# UCirKitBreadboardTop-0824.net
KiCad netlist of a schematic drawn in EAGLE
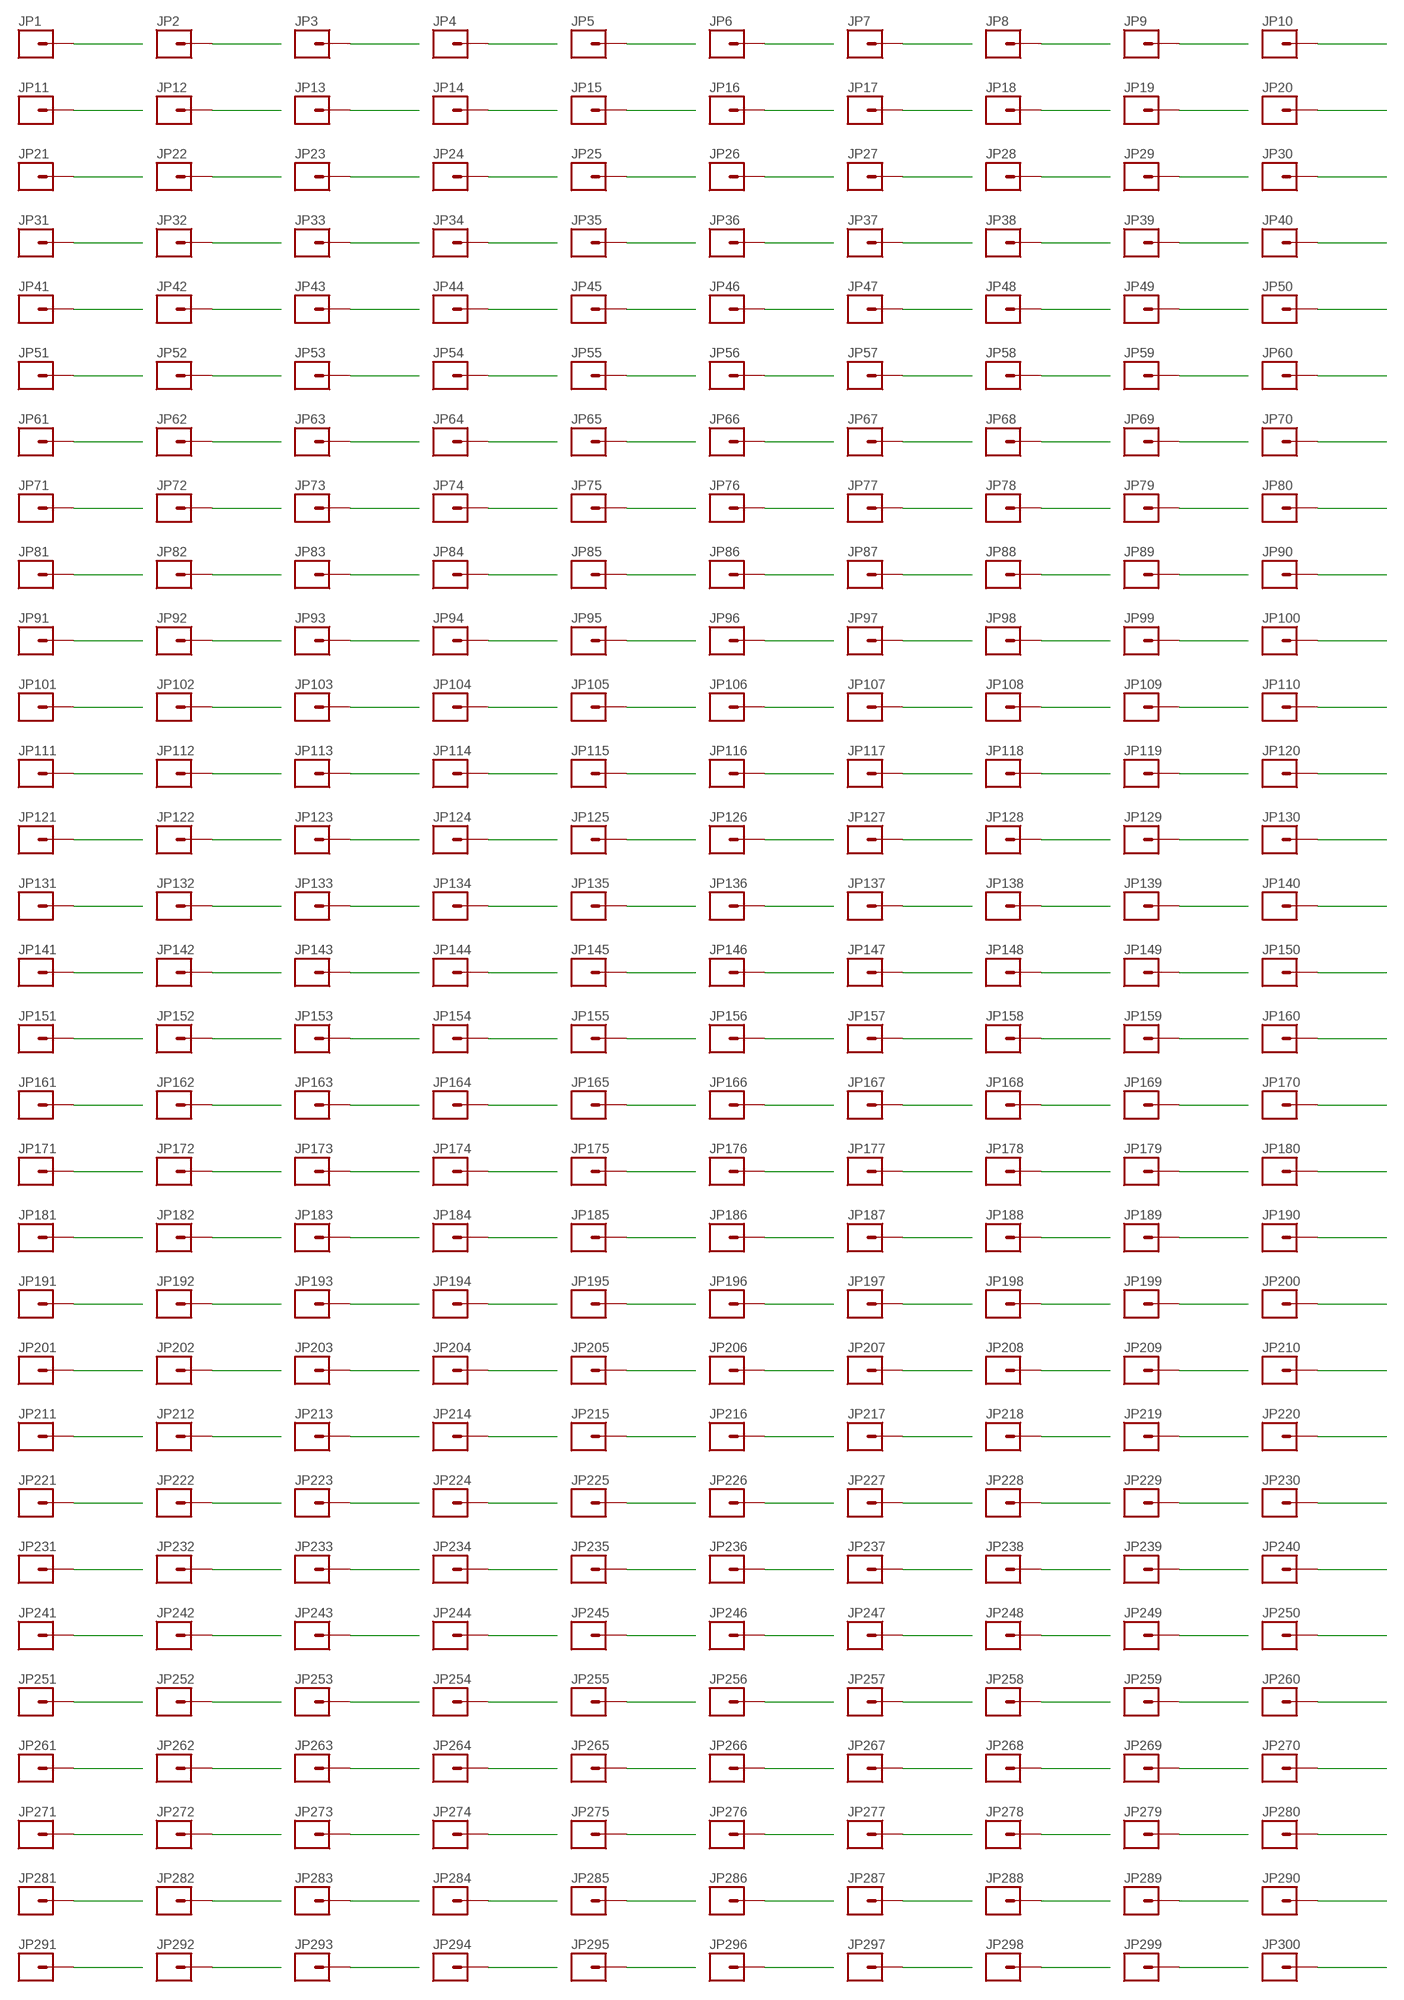
[diagram p0: schematic, sheet 1, part 1 of 2]
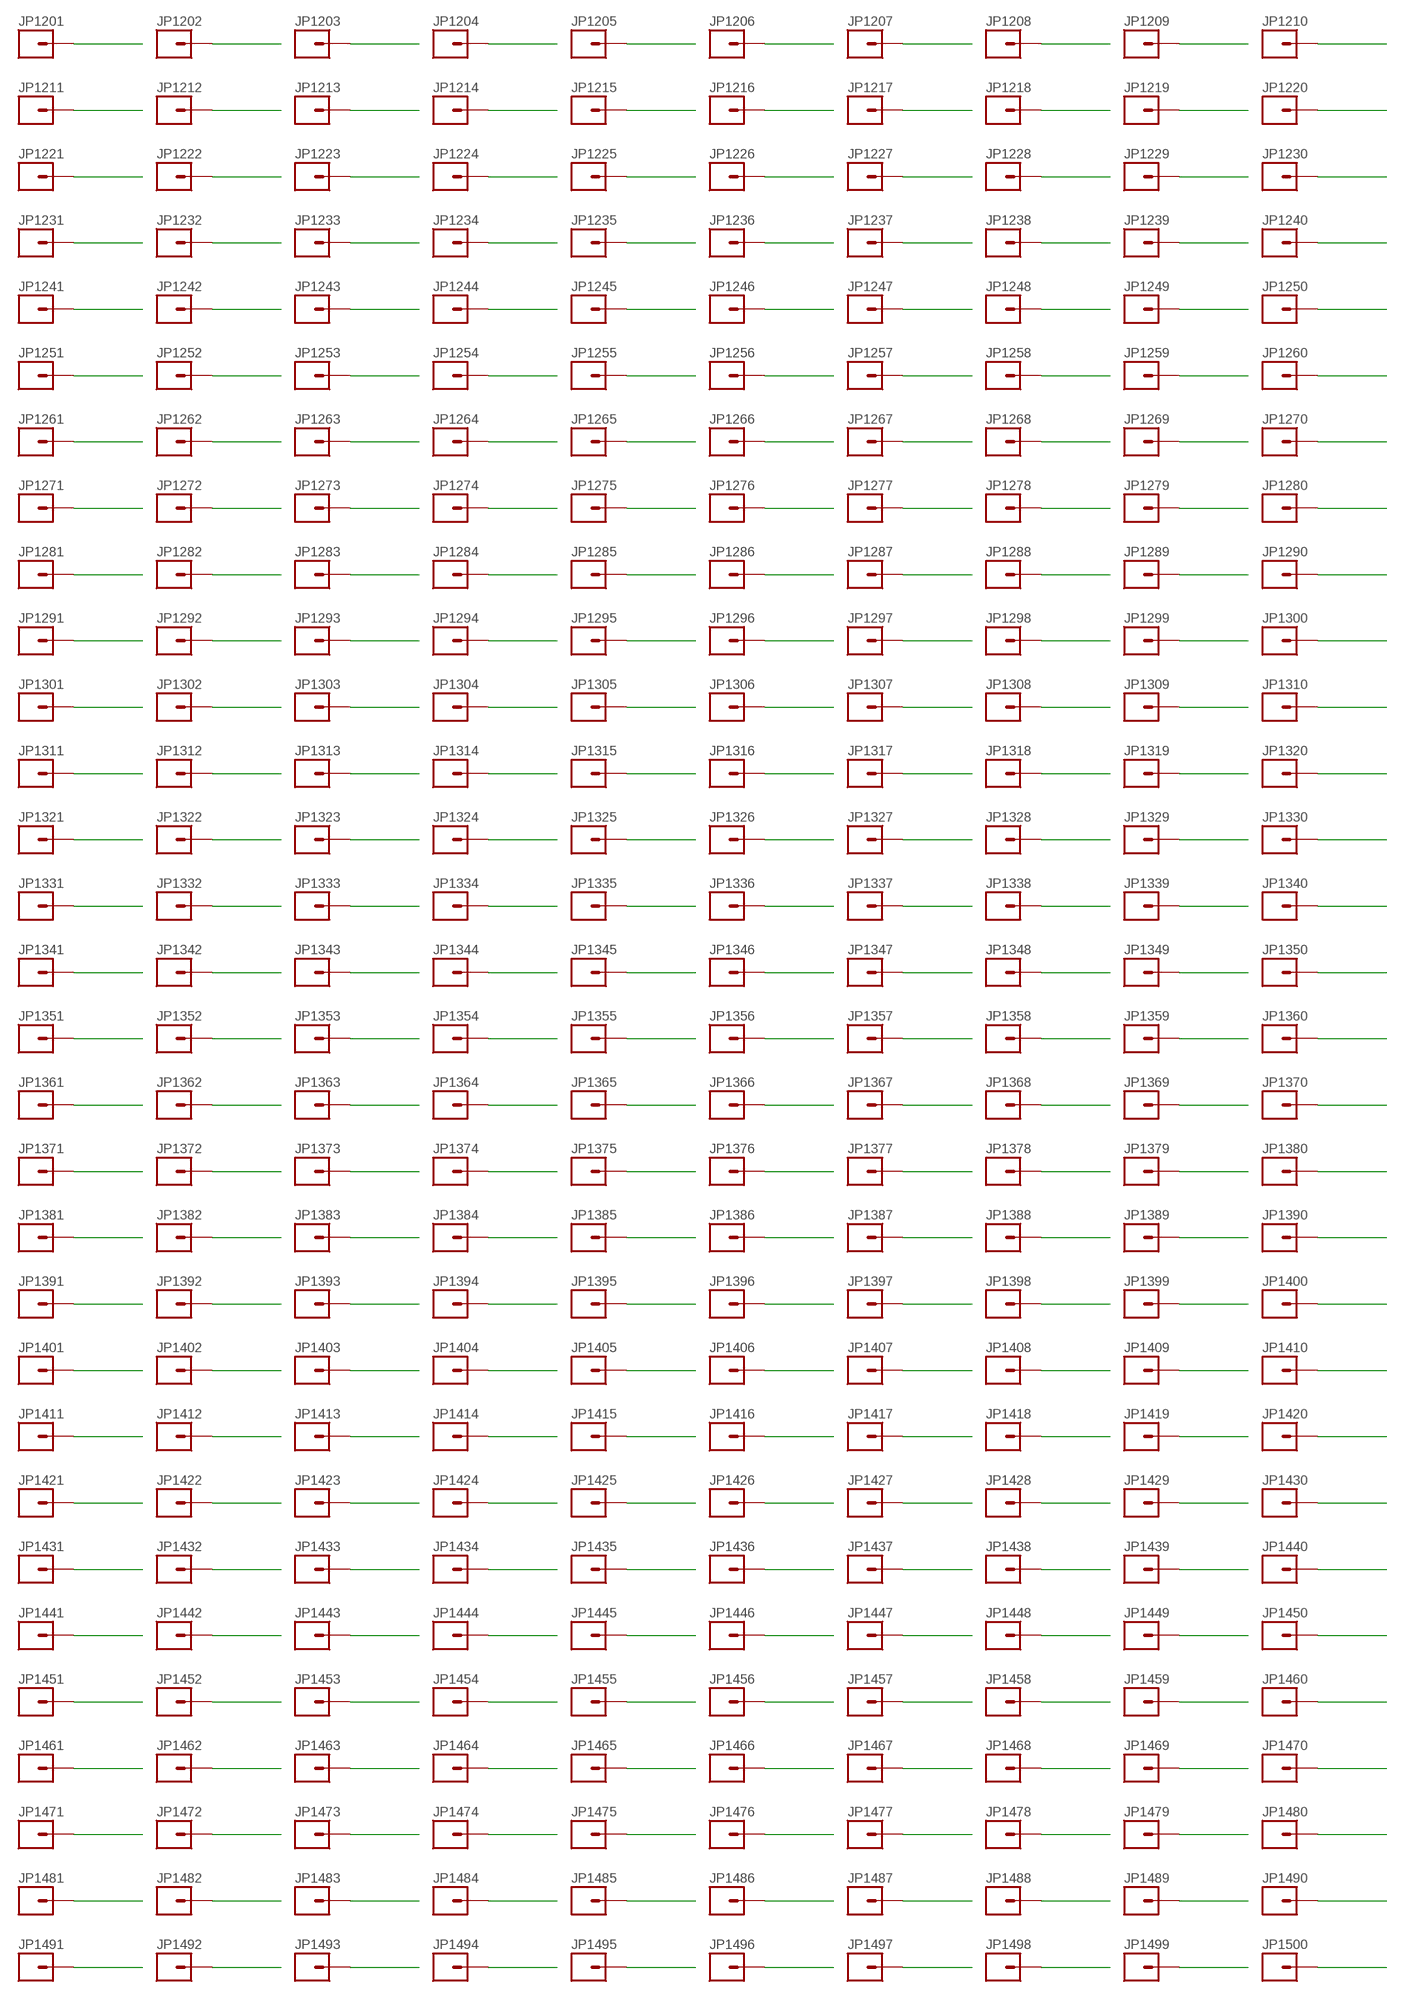
[diagram p1: schematic, sheet 1, part 2 of 2]

(export (version "E")
  (design (tool "Eeschema 10.0.6"))
  (components
    (comp (ref "JP1")
      (value "M01PTH_WITHOUT_TEXT")
      (footprint "eagle-import:1X01_WITHOUT_TEXT")
      (libsource (lib "eagle-import") (part "M01PTH_WITHOUT_TEXT"))
    )
    (comp (ref "JP2")
      (value "M01PTH_WITHOUT_TEXT")
      (footprint "eagle-import:1X01_WITHOUT_TEXT")
      (libsource (lib "eagle-import") (part "M01PTH_WITHOUT_TEXT"))
    )
    (comp (ref "JP3")
      (value "M01PTH_WITHOUT_TEXT")
      (footprint "eagle-import:1X01_WITHOUT_TEXT")
      (libsource (lib "eagle-import") (part "M01PTH_WITHOUT_TEXT"))
    )
    (comp (ref "JP4")
      (value "M01PTH_WITHOUT_TEXT")
      (footprint "eagle-import:1X01_WITHOUT_TEXT")
      (libsource (lib "eagle-import") (part "M01PTH_WITHOUT_TEXT"))
    )
    (comp (ref "JP5")
      (value "M01PTH_WITHOUT_TEXT")
      (footprint "eagle-import:1X01_WITHOUT_TEXT")
      (libsource (lib "eagle-import") (part "M01PTH_WITHOUT_TEXT"))
    )
    (comp (ref "JP6")
      (value "M01PTH_WITHOUT_TEXT")
      (footprint "eagle-import:1X01_WITHOUT_TEXT")
      (libsource (lib "eagle-import") (part "M01PTH_WITHOUT_TEXT"))
    )
    (comp (ref "JP7")
      (value "M01PTH_WITHOUT_TEXT")
      (footprint "eagle-import:1X01_WITHOUT_TEXT")
      (libsource (lib "eagle-import") (part "M01PTH_WITHOUT_TEXT"))
    )
    (comp (ref "JP8")
      (value "M01PTH_WITHOUT_TEXT")
      (footprint "eagle-import:1X01_WITHOUT_TEXT")
      (libsource (lib "eagle-import") (part "M01PTH_WITHOUT_TEXT"))
    )
    (comp (ref "JP9")
      (value "M01PTH_WITHOUT_TEXT")
      (footprint "eagle-import:1X01_WITHOUT_TEXT")
      (libsource (lib "eagle-import") (part "M01PTH_WITHOUT_TEXT"))
    )
    (comp (ref "JP10")
      (value "M01PTH_WITHOUT_TEXT")
      (footprint "eagle-import:1X01_WITHOUT_TEXT")
      (libsource (lib "eagle-import") (part "M01PTH_WITHOUT_TEXT"))
    )
    (comp (ref "JP11")
      (value "M01PTH_WITHOUT_TEXT")
      (footprint "eagle-import:1X01_WITHOUT_TEXT")
      (libsource (lib "eagle-import") (part "M01PTH_WITHOUT_TEXT"))
    )
    (comp (ref "JP12")
      (value "M01PTH_WITHOUT_TEXT")
      (footprint "eagle-import:1X01_WITHOUT_TEXT")
      (libsource (lib "eagle-import") (part "M01PTH_WITHOUT_TEXT"))
    )
    (comp (ref "JP13")
      (value "M01PTH_WITHOUT_TEXT")
      (footprint "eagle-import:1X01_WITHOUT_TEXT")
      (libsource (lib "eagle-import") (part "M01PTH_WITHOUT_TEXT"))
    )
    (comp (ref "JP14")
      (value "M01PTH_WITHOUT_TEXT")
      (footprint "eagle-import:1X01_WITHOUT_TEXT")
      (libsource (lib "eagle-import") (part "M01PTH_WITHOUT_TEXT"))
    )
    (comp (ref "JP15")
      (value "M01PTH_WITHOUT_TEXT")
      (footprint "eagle-import:1X01_WITHOUT_TEXT")
      (libsource (lib "eagle-import") (part "M01PTH_WITHOUT_TEXT"))
    )
    (comp (ref "JP16")
      (value "M01PTH_WITHOUT_TEXT")
      (footprint "eagle-import:1X01_WITHOUT_TEXT")
      (libsource (lib "eagle-import") (part "M01PTH_WITHOUT_TEXT"))
    )
    (comp (ref "JP17")
      (value "M01PTH_WITHOUT_TEXT")
      (footprint "eagle-import:1X01_WITHOUT_TEXT")
      (libsource (lib "eagle-import") (part "M01PTH_WITHOUT_TEXT"))
    )
    (comp (ref "JP18")
      (value "M01PTH_WITHOUT_TEXT")
      (footprint "eagle-import:1X01_WITHOUT_TEXT")
      (libsource (lib "eagle-import") (part "M01PTH_WITHOUT_TEXT"))
    )
    (comp (ref "JP19")
      (value "M01PTH_WITHOUT_TEXT")
      (footprint "eagle-import:1X01_WITHOUT_TEXT")
      (libsource (lib "eagle-import") (part "M01PTH_WITHOUT_TEXT"))
    )
    (comp (ref "JP20")
      (value "M01PTH_WITHOUT_TEXT")
      (footprint "eagle-import:1X01_WITHOUT_TEXT")
      (libsource (lib "eagle-import") (part "M01PTH_WITHOUT_TEXT"))
    )
    (comp (ref "JP21")
      (value "M01PTH_WITHOUT_TEXT")
      (footprint "eagle-import:1X01_WITHOUT_TEXT")
      (libsource (lib "eagle-import") (part "M01PTH_WITHOUT_TEXT"))
    )
    (comp (ref "JP22")
      (value "M01PTH_WITHOUT_TEXT")
      (footprint "eagle-import:1X01_WITHOUT_TEXT")
      (libsource (lib "eagle-import") (part "M01PTH_WITHOUT_TEXT"))
    )
    (comp (ref "JP23")
      (value "M01PTH_WITHOUT_TEXT")
      (footprint "eagle-import:1X01_WITHOUT_TEXT")
      (libsource (lib "eagle-import") (part "M01PTH_WITHOUT_TEXT"))
    )
    (comp (ref "JP24")
      (value "M01PTH_WITHOUT_TEXT")
      (footprint "eagle-import:1X01_WITHOUT_TEXT")
      (libsource (lib "eagle-import") (part "M01PTH_WITHOUT_TEXT"))
    )
    (comp (ref "JP25")
      (value "M01PTH_WITHOUT_TEXT")
      (footprint "eagle-import:1X01_WITHOUT_TEXT")
      (libsource (lib "eagle-import") (part "M01PTH_WITHOUT_TEXT"))
    )
    (comp (ref "JP26")
      (value "M01PTH_WITHOUT_TEXT")
      (footprint "eagle-import:1X01_WITHOUT_TEXT")
      (libsource (lib "eagle-import") (part "M01PTH_WITHOUT_TEXT"))
    )
    (comp (ref "JP27")
      (value "M01PTH_WITHOUT_TEXT")
      (footprint "eagle-import:1X01_WITHOUT_TEXT")
      (libsource (lib "eagle-import") (part "M01PTH_WITHOUT_TEXT"))
    )
    (comp (ref "JP28")
      (value "M01PTH_WITHOUT_TEXT")
      (footprint "eagle-import:1X01_WITHOUT_TEXT")
      (libsource (lib "eagle-import") (part "M01PTH_WITHOUT_TEXT"))
    )
    (comp (ref "JP29")
      (value "M01PTH_WITHOUT_TEXT")
      (footprint "eagle-import:1X01_WITHOUT_TEXT")
      (libsource (lib "eagle-import") (part "M01PTH_WITHOUT_TEXT"))
    )
    (comp (ref "JP30")
      (value "M01PTH_WITHOUT_TEXT")
      (footprint "eagle-import:1X01_WITHOUT_TEXT")
      (libsource (lib "eagle-import") (part "M01PTH_WITHOUT_TEXT"))
    )
    (comp (ref "JP31")
      (value "M01PTH_WITHOUT_TEXT")
      (footprint "eagle-import:1X01_WITHOUT_TEXT")
      (libsource (lib "eagle-import") (part "M01PTH_WITHOUT_TEXT"))
    )
    (comp (ref "JP32")
      (value "M01PTH_WITHOUT_TEXT")
      (footprint "eagle-import:1X01_WITHOUT_TEXT")
      (libsource (lib "eagle-import") (part "M01PTH_WITHOUT_TEXT"))
    )
    (comp (ref "JP33")
      (value "M01PTH_WITHOUT_TEXT")
      (footprint "eagle-import:1X01_WITHOUT_TEXT")
      (libsource (lib "eagle-import") (part "M01PTH_WITHOUT_TEXT"))
    )
    (comp (ref "JP34")
      (value "M01PTH_WITHOUT_TEXT")
      (footprint "eagle-import:1X01_WITHOUT_TEXT")
      (libsource (lib "eagle-import") (part "M01PTH_WITHOUT_TEXT"))
    )
    (comp (ref "JP35")
      (value "M01PTH_WITHOUT_TEXT")
      (footprint "eagle-import:1X01_WITHOUT_TEXT")
      (libsource (lib "eagle-import") (part "M01PTH_WITHOUT_TEXT"))
    )
    (comp (ref "JP36")
      (value "M01PTH_WITHOUT_TEXT")
      (footprint "eagle-import:1X01_WITHOUT_TEXT")
      (libsource (lib "eagle-import") (part "M01PTH_WITHOUT_TEXT"))
    )
    (comp (ref "JP37")
      (value "M01PTH_WITHOUT_TEXT")
      (footprint "eagle-import:1X01_WITHOUT_TEXT")
      (libsource (lib "eagle-import") (part "M01PTH_WITHOUT_TEXT"))
    )
    (comp (ref "JP38")
      (value "M01PTH_WITHOUT_TEXT")
      (footprint "eagle-import:1X01_WITHOUT_TEXT")
      (libsource (lib "eagle-import") (part "M01PTH_WITHOUT_TEXT"))
    )
    (comp (ref "JP39")
      (value "M01PTH_WITHOUT_TEXT")
      (footprint "eagle-import:1X01_WITHOUT_TEXT")
      (libsource (lib "eagle-import") (part "M01PTH_WITHOUT_TEXT"))
    )
    (comp (ref "JP40")
      (value "M01PTH_WITHOUT_TEXT")
      (footprint "eagle-import:1X01_WITHOUT_TEXT")
      (libsource (lib "eagle-import") (part "M01PTH_WITHOUT_TEXT"))
    )
    (comp (ref "JP41")
      (value "M01PTH_WITHOUT_TEXT")
      (footprint "eagle-import:1X01_WITHOUT_TEXT")
      (libsource (lib "eagle-import") (part "M01PTH_WITHOUT_TEXT"))
    )
    (comp (ref "JP42")
      (value "M01PTH_WITHOUT_TEXT")
      (footprint "eagle-import:1X01_WITHOUT_TEXT")
      (libsource (lib "eagle-import") (part "M01PTH_WITHOUT_TEXT"))
    )
    (comp (ref "JP43")
      (value "M01PTH_WITHOUT_TEXT")
      (footprint "eagle-import:1X01_WITHOUT_TEXT")
      (libsource (lib "eagle-import") (part "M01PTH_WITHOUT_TEXT"))
    )
    (comp (ref "JP44")
      (value "M01PTH_WITHOUT_TEXT")
      (footprint "eagle-import:1X01_WITHOUT_TEXT")
      (libsource (lib "eagle-import") (part "M01PTH_WITHOUT_TEXT"))
    )
    (comp (ref "JP45")
      (value "M01PTH_WITHOUT_TEXT")
      (footprint "eagle-import:1X01_WITHOUT_TEXT")
      (libsource (lib "eagle-import") (part "M01PTH_WITHOUT_TEXT"))
    )
    (comp (ref "JP46")
      (value "M01PTH_WITHOUT_TEXT")
      (footprint "eagle-import:1X01_WITHOUT_TEXT")
      (libsource (lib "eagle-import") (part "M01PTH_WITHOUT_TEXT"))
    )
    (comp (ref "JP47")
      (value "M01PTH_WITHOUT_TEXT")
      (footprint "eagle-import:1X01_WITHOUT_TEXT")
      (libsource (lib "eagle-import") (part "M01PTH_WITHOUT_TEXT"))
    )
    (comp (ref "JP48")
      (value "M01PTH_WITHOUT_TEXT")
      (footprint "eagle-import:1X01_WITHOUT_TEXT")
      (libsource (lib "eagle-import") (part "M01PTH_WITHOUT_TEXT"))
    )
    (comp (ref "JP49")
      (value "M01PTH_WITHOUT_TEXT")
      (footprint "eagle-import:1X01_WITHOUT_TEXT")
      (libsource (lib "eagle-import") (part "M01PTH_WITHOUT_TEXT"))
    )
    (comp (ref "JP50")
      (value "M01PTH_WITHOUT_TEXT")
      (footprint "eagle-import:1X01_WITHOUT_TEXT")
      (libsource (lib "eagle-import") (part "M01PTH_WITHOUT_TEXT"))
    )
    (comp (ref "JP51")
      (value "M01PTH_WITHOUT_TEXT")
      (footprint "eagle-import:1X01_WITHOUT_TEXT")
      (libsource (lib "eagle-import") (part "M01PTH_WITHOUT_TEXT"))
    )
    (comp (ref "JP52")
      (value "M01PTH_WITHOUT_TEXT")
      (footprint "eagle-import:1X01_WITHOUT_TEXT")
      (libsource (lib "eagle-import") (part "M01PTH_WITHOUT_TEXT"))
    )
    (comp (ref "JP53")
      (value "M01PTH_WITHOUT_TEXT")
      (footprint "eagle-import:1X01_WITHOUT_TEXT")
      (libsource (lib "eagle-import") (part "M01PTH_WITHOUT_TEXT"))
    )
    (comp (ref "JP54")
      (value "M01PTH_WITHOUT_TEXT")
      (footprint "eagle-import:1X01_WITHOUT_TEXT")
      (libsource (lib "eagle-import") (part "M01PTH_WITHOUT_TEXT"))
    )
    (comp (ref "JP55")
      (value "M01PTH_WITHOUT_TEXT")
      (footprint "eagle-import:1X01_WITHOUT_TEXT")
      (libsource (lib "eagle-import") (part "M01PTH_WITHOUT_TEXT"))
    )
    (comp (ref "JP56")
      (value "M01PTH_WITHOUT_TEXT")
      (footprint "eagle-import:1X01_WITHOUT_TEXT")
      (libsource (lib "eagle-import") (part "M01PTH_WITHOUT_TEXT"))
    )
    (comp (ref "JP57")
      (value "M01PTH_WITHOUT_TEXT")
      (footprint "eagle-import:1X01_WITHOUT_TEXT")
      (libsource (lib "eagle-import") (part "M01PTH_WITHOUT_TEXT"))
    )
    (comp (ref "JP58")
      (value "M01PTH_WITHOUT_TEXT")
      (footprint "eagle-import:1X01_WITHOUT_TEXT")
      (libsource (lib "eagle-import") (part "M01PTH_WITHOUT_TEXT"))
    )
    (comp (ref "JP59")
      (value "M01PTH_WITHOUT_TEXT")
      (footprint "eagle-import:1X01_WITHOUT_TEXT")
      (libsource (lib "eagle-import") (part "M01PTH_WITHOUT_TEXT"))
    )
    (comp (ref "JP60")
      (value "M01PTH_WITHOUT_TEXT")
      (footprint "eagle-import:1X01_WITHOUT_TEXT")
      (libsource (lib "eagle-import") (part "M01PTH_WITHOUT_TEXT"))
    )
    (comp (ref "JP61")
      (value "M01PTH_WITHOUT_TEXT")
      (footprint "eagle-import:1X01_WITHOUT_TEXT")
      (libsource (lib "eagle-import") (part "M01PTH_WITHOUT_TEXT"))
    )
    (comp (ref "JP62")
      (value "M01PTH_WITHOUT_TEXT")
      (footprint "eagle-import:1X01_WITHOUT_TEXT")
      (libsource (lib "eagle-import") (part "M01PTH_WITHOUT_TEXT"))
    )
    (comp (ref "JP63")
      (value "M01PTH_WITHOUT_TEXT")
      (footprint "eagle-import:1X01_WITHOUT_TEXT")
      (libsource (lib "eagle-import") (part "M01PTH_WITHOUT_TEXT"))
    )
    (comp (ref "JP64")
      (value "M01PTH_WITHOUT_TEXT")
      (footprint "eagle-import:1X01_WITHOUT_TEXT")
      (libsource (lib "eagle-import") (part "M01PTH_WITHOUT_TEXT"))
    )
    (comp (ref "JP65")
      (value "M01PTH_WITHOUT_TEXT")
      (footprint "eagle-import:1X01_WITHOUT_TEXT")
      (libsource (lib "eagle-import") (part "M01PTH_WITHOUT_TEXT"))
    )
    (comp (ref "JP66")
      (value "M01PTH_WITHOUT_TEXT")
      (footprint "eagle-import:1X01_WITHOUT_TEXT")
      (libsource (lib "eagle-import") (part "M01PTH_WITHOUT_TEXT"))
    )
    (comp (ref "JP67")
      (value "M01PTH_WITHOUT_TEXT")
      (footprint "eagle-import:1X01_WITHOUT_TEXT")
      (libsource (lib "eagle-import") (part "M01PTH_WITHOUT_TEXT"))
    )
    (comp (ref "JP68")
      (value "M01PTH_WITHOUT_TEXT")
      (footprint "eagle-import:1X01_WITHOUT_TEXT")
      (libsource (lib "eagle-import") (part "M01PTH_WITHOUT_TEXT"))
    )
    (comp (ref "JP69")
      (value "M01PTH_WITHOUT_TEXT")
      (footprint "eagle-import:1X01_WITHOUT_TEXT")
      (libsource (lib "eagle-import") (part "M01PTH_WITHOUT_TEXT"))
    )
    (comp (ref "JP70")
      (value "M01PTH_WITHOUT_TEXT")
      (footprint "eagle-import:1X01_WITHOUT_TEXT")
      (libsource (lib "eagle-import") (part "M01PTH_WITHOUT_TEXT"))
    )
    (comp (ref "JP71")
      (value "M01PTH_WITHOUT_TEXT")
      (footprint "eagle-import:1X01_WITHOUT_TEXT")
      (libsource (lib "eagle-import") (part "M01PTH_WITHOUT_TEXT"))
    )
    (comp (ref "JP72")
      (value "M01PTH_WITHOUT_TEXT")
      (footprint "eagle-import:1X01_WITHOUT_TEXT")
      (libsource (lib "eagle-import") (part "M01PTH_WITHOUT_TEXT"))
    )
    (comp (ref "JP73")
      (value "M01PTH_WITHOUT_TEXT")
      (footprint "eagle-import:1X01_WITHOUT_TEXT")
      (libsource (lib "eagle-import") (part "M01PTH_WITHOUT_TEXT"))
    )
    (comp (ref "JP74")
      (value "M01PTH_WITHOUT_TEXT")
      (footprint "eagle-import:1X01_WITHOUT_TEXT")
      (libsource (lib "eagle-import") (part "M01PTH_WITHOUT_TEXT"))
    )
    (comp (ref "JP75")
      (value "M01PTH_WITHOUT_TEXT")
      (footprint "eagle-import:1X01_WITHOUT_TEXT")
      (libsource (lib "eagle-import") (part "M01PTH_WITHOUT_TEXT"))
    )
    (comp (ref "JP76")
      (value "M01PTH_WITHOUT_TEXT")
      (footprint "eagle-import:1X01_WITHOUT_TEXT")
      (libsource (lib "eagle-import") (part "M01PTH_WITHOUT_TEXT"))
    )
    (comp (ref "JP77")
      (value "M01PTH_WITHOUT_TEXT")
      (footprint "eagle-import:1X01_WITHOUT_TEXT")
      (libsource (lib "eagle-import") (part "M01PTH_WITHOUT_TEXT"))
    )
    (comp (ref "JP78")
      (value "M01PTH_WITHOUT_TEXT")
      (footprint "eagle-import:1X01_WITHOUT_TEXT")
      (libsource (lib "eagle-import") (part "M01PTH_WITHOUT_TEXT"))
    )
    (comp (ref "JP79")
      (value "M01PTH_WITHOUT_TEXT")
      (footprint "eagle-import:1X01_WITHOUT_TEXT")
      (libsource (lib "eagle-import") (part "M01PTH_WITHOUT_TEXT"))
    )
    (comp (ref "JP80")
      (value "M01PTH_WITHOUT_TEXT")
      (footprint "eagle-import:1X01_WITHOUT_TEXT")
      (libsource (lib "eagle-import") (part "M01PTH_WITHOUT_TEXT"))
    )
    (comp (ref "JP81")
      (value "M01PTH_WITHOUT_TEXT")
      (footprint "eagle-import:1X01_WITHOUT_TEXT")
      (libsource (lib "eagle-import") (part "M01PTH_WITHOUT_TEXT"))
    )
    (comp (ref "JP82")
      (value "M01PTH_WITHOUT_TEXT")
      (footprint "eagle-import:1X01_WITHOUT_TEXT")
      (libsource (lib "eagle-import") (part "M01PTH_WITHOUT_TEXT"))
    )
    (comp (ref "JP83")
      (value "M01PTH_WITHOUT_TEXT")
      (footprint "eagle-import:1X01_WITHOUT_TEXT")
      (libsource (lib "eagle-import") (part "M01PTH_WITHOUT_TEXT"))
    )
    (comp (ref "JP84")
      (value "M01PTH_WITHOUT_TEXT")
      (footprint "eagle-import:1X01_WITHOUT_TEXT")
      (libsource (lib "eagle-import") (part "M01PTH_WITHOUT_TEXT"))
    )
    (comp (ref "JP85")
      (value "M01PTH_WITHOUT_TEXT")
      (footprint "eagle-import:1X01_WITHOUT_TEXT")
      (libsource (lib "eagle-import") (part "M01PTH_WITHOUT_TEXT"))
    )
    (comp (ref "JP86")
      (value "M01PTH_WITHOUT_TEXT")
      (footprint "eagle-import:1X01_WITHOUT_TEXT")
      (libsource (lib "eagle-import") (part "M01PTH_WITHOUT_TEXT"))
    )
    (comp (ref "JP87")
      (value "M01PTH_WITHOUT_TEXT")
      (footprint "eagle-import:1X01_WITHOUT_TEXT")
      (libsource (lib "eagle-import") (part "M01PTH_WITHOUT_TEXT"))
    )
    (comp (ref "JP88")
      (value "M01PTH_WITHOUT_TEXT")
      (footprint "eagle-import:1X01_WITHOUT_TEXT")
      (libsource (lib "eagle-import") (part "M01PTH_WITHOUT_TEXT"))
    )
    (comp (ref "JP89")
      (value "M01PTH_WITHOUT_TEXT")
      (footprint "eagle-import:1X01_WITHOUT_TEXT")
      (libsource (lib "eagle-import") (part "M01PTH_WITHOUT_TEXT"))
    )
    (comp (ref "JP90")
      (value "M01PTH_WITHOUT_TEXT")
      (footprint "eagle-import:1X01_WITHOUT_TEXT")
      (libsource (lib "eagle-import") (part "M01PTH_WITHOUT_TEXT"))
    )
    (comp (ref "JP91")
      (value "M01PTH_WITHOUT_TEXT")
      (footprint "eagle-import:1X01_WITHOUT_TEXT")
      (libsource (lib "eagle-import") (part "M01PTH_WITHOUT_TEXT"))
    )
    (comp (ref "JP92")
      (value "M01PTH_WITHOUT_TEXT")
      (footprint "eagle-import:1X01_WITHOUT_TEXT")
      (libsource (lib "eagle-import") (part "M01PTH_WITHOUT_TEXT"))
    )
    (comp (ref "JP93")
      (value "M01PTH_WITHOUT_TEXT")
      (footprint "eagle-import:1X01_WITHOUT_TEXT")
      (libsource (lib "eagle-import") (part "M01PTH_WITHOUT_TEXT"))
    )
    (comp (ref "JP94")
      (value "M01PTH_WITHOUT_TEXT")
      (footprint "eagle-import:1X01_WITHOUT_TEXT")
      (libsource (lib "eagle-import") (part "M01PTH_WITHOUT_TEXT"))
    )
    (comp (ref "JP95")
      (value "M01PTH_WITHOUT_TEXT")
      (footprint "eagle-import:1X01_WITHOUT_TEXT")
      (libsource (lib "eagle-import") (part "M01PTH_WITHOUT_TEXT"))
    )
    (comp (ref "JP96")
      (value "M01PTH_WITHOUT_TEXT")
      (footprint "eagle-import:1X01_WITHOUT_TEXT")
      (libsource (lib "eagle-import") (part "M01PTH_WITHOUT_TEXT"))
    )
    (comp (ref "JP97")
      (value "M01PTH_WITHOUT_TEXT")
      (footprint "eagle-import:1X01_WITHOUT_TEXT")
      (libsource (lib "eagle-import") (part "M01PTH_WITHOUT_TEXT"))
    )
    (comp (ref "JP98")
      (value "M01PTH_WITHOUT_TEXT")
      (footprint "eagle-import:1X01_WITHOUT_TEXT")
      (libsource (lib "eagle-import") (part "M01PTH_WITHOUT_TEXT"))
    )
    (comp (ref "JP99")
      (value "M01PTH_WITHOUT_TEXT")
      (footprint "eagle-import:1X01_WITHOUT_TEXT")
      (libsource (lib "eagle-import") (part "M01PTH_WITHOUT_TEXT"))
    )
    (comp (ref "JP100")
      (value "M01PTH_WITHOUT_TEXT")
      (footprint "eagle-import:1X01_WITHOUT_TEXT")
      (libsource (lib "eagle-import") (part "M01PTH_WITHOUT_TEXT"))
    )
    (comp (ref "JP101")
      (value "M01PTH_WITHOUT_TEXT")
      (footprint "eagle-import:1X01_WITHOUT_TEXT")
      (libsource (lib "eagle-import") (part "M01PTH_WITHOUT_TEXT"))
    )
    (comp (ref "JP102")
      (value "M01PTH_WITHOUT_TEXT")
      (footprint "eagle-import:1X01_WITHOUT_TEXT")
      (libsource (lib "eagle-import") (part "M01PTH_WITHOUT_TEXT"))
    )
    (comp (ref "JP103")
      (value "M01PTH_WITHOUT_TEXT")
      (footprint "eagle-import:1X01_WITHOUT_TEXT")
      (libsource (lib "eagle-import") (part "M01PTH_WITHOUT_TEXT"))
    )
    (comp (ref "JP104")
      (value "M01PTH_WITHOUT_TEXT")
      (footprint "eagle-import:1X01_WITHOUT_TEXT")
      (libsource (lib "eagle-import") (part "M01PTH_WITHOUT_TEXT"))
    )
    (comp (ref "JP105")
      (value "M01PTH_WITHOUT_TEXT")
      (footprint "eagle-import:1X01_WITHOUT_TEXT")
      (libsource (lib "eagle-import") (part "M01PTH_WITHOUT_TEXT"))
    )
    (comp (ref "JP106")
      (value "M01PTH_WITHOUT_TEXT")
      (footprint "eagle-import:1X01_WITHOUT_TEXT")
      (libsource (lib "eagle-import") (part "M01PTH_WITHOUT_TEXT"))
    )
    (comp (ref "JP107")
      (value "M01PTH_WITHOUT_TEXT")
      (footprint "eagle-import:1X01_WITHOUT_TEXT")
      (libsource (lib "eagle-import") (part "M01PTH_WITHOUT_TEXT"))
    )
    (comp (ref "JP108")
      (value "M01PTH_WITHOUT_TEXT")
      (footprint "eagle-import:1X01_WITHOUT_TEXT")
      (libsource (lib "eagle-import") (part "M01PTH_WITHOUT_TEXT"))
    )
    (comp (ref "JP109")
      (value "M01PTH_WITHOUT_TEXT")
      (footprint "eagle-import:1X01_WITHOUT_TEXT")
      (libsource (lib "eagle-import") (part "M01PTH_WITHOUT_TEXT"))
    )
    (comp (ref "JP110")
      (value "M01PTH_WITHOUT_TEXT")
      (footprint "eagle-import:1X01_WITHOUT_TEXT")
      (libsource (lib "eagle-import") (part "M01PTH_WITHOUT_TEXT"))
    )
    (comp (ref "JP111")
      (value "M01PTH_WITHOUT_TEXT")
      (footprint "eagle-import:1X01_WITHOUT_TEXT")
      (libsource (lib "eagle-import") (part "M01PTH_WITHOUT_TEXT"))
    )
    (comp (ref "JP112")
      (value "M01PTH_WITHOUT_TEXT")
      (footprint "eagle-import:1X01_WITHOUT_TEXT")
      (libsource (lib "eagle-import") (part "M01PTH_WITHOUT_TEXT"))
    )
    (comp (ref "JP113")
      (value "M01PTH_WITHOUT_TEXT")
      (footprint "eagle-import:1X01_WITHOUT_TEXT")
      (libsource (lib "eagle-import") (part "M01PTH_WITHOUT_TEXT"))
    )
    (comp (ref "JP114")
      (value "M01PTH_WITHOUT_TEXT")
      (footprint "eagle-import:1X01_WITHOUT_TEXT")
      (libsource (lib "eagle-import") (part "M01PTH_WITHOUT_TEXT"))
    )
    (comp (ref "JP115")
      (value "M01PTH_WITHOUT_TEXT")
      (footprint "eagle-import:1X01_WITHOUT_TEXT")
      (libsource (lib "eagle-import") (part "M01PTH_WITHOUT_TEXT"))
    )
    (comp (ref "JP116")
      (value "M01PTH_WITHOUT_TEXT")
      (footprint "eagle-import:1X01_WITHOUT_TEXT")
      (libsource (lib "eagle-import") (part "M01PTH_WITHOUT_TEXT"))
    )
    (comp (ref "JP117")
      (value "M01PTH_WITHOUT_TEXT")
      (footprint "eagle-import:1X01_WITHOUT_TEXT")
      (libsource (lib "eagle-import") (part "M01PTH_WITHOUT_TEXT"))
    )
    (comp (ref "JP118")
      (value "M01PTH_WITHOUT_TEXT")
      (footprint "eagle-import:1X01_WITHOUT_TEXT")
      (libsource (lib "eagle-import") (part "M01PTH_WITHOUT_TEXT"))
    )
    (comp (ref "JP119")
      (value "M01PTH_WITHOUT_TEXT")
      (footprint "eagle-import:1X01_WITHOUT_TEXT")
      (libsource (lib "eagle-import") (part "M01PTH_WITHOUT_TEXT"))
    )
    (comp (ref "JP120")
      (value "M01PTH_WITHOUT_TEXT")
      (footprint "eagle-import:1X01_WITHOUT_TEXT")
      (libsource (lib "eagle-import") (part "M01PTH_WITHOUT_TEXT"))
    )
    (comp (ref "JP121")
      (value "M01PTH_WITHOUT_TEXT")
      (footprint "eagle-import:1X01_WITHOUT_TEXT")
      (libsource (lib "eagle-import") (part "M01PTH_WITHOUT_TEXT"))
    )
    (comp (ref "JP122")
      (value "M01PTH_WITHOUT_TEXT")
      (footprint "eagle-import:1X01_WITHOUT_TEXT")
      (libsource (lib "eagle-import") (part "M01PTH_WITHOUT_TEXT"))
    )
    (comp (ref "JP123")
      (value "M01PTH_WITHOUT_TEXT")
      (footprint "eagle-import:1X01_WITHOUT_TEXT")
      (libsource (lib "eagle-import") (part "M01PTH_WITHOUT_TEXT"))
    )
    (comp (ref "JP124")
      (value "M01PTH_WITHOUT_TEXT")
      (footprint "eagle-import:1X01_WITHOUT_TEXT")
      (libsource (lib "eagle-import") (part "M01PTH_WITHOUT_TEXT"))
    )
    (comp (ref "JP125")
      (value "M01PTH_WITHOUT_TEXT")
      (footprint "eagle-import:1X01_WITHOUT_TEXT")
      (libsource (lib "eagle-import") (part "M01PTH_WITHOUT_TEXT"))
    )
    (comp (ref "JP126")
      (value "M01PTH_WITHOUT_TEXT")
      (footprint "eagle-import:1X01_WITHOUT_TEXT")
      (libsource (lib "eagle-import") (part "M01PTH_WITHOUT_TEXT"))
    )
    (comp (ref "JP127")
      (value "M01PTH_WITHOUT_TEXT")
      (footprint "eagle-import:1X01_WITHOUT_TEXT")
      (libsource (lib "eagle-import") (part "M01PTH_WITHOUT_TEXT"))
    )
    (comp (ref "JP128")
      (value "M01PTH_WITHOUT_TEXT")
      (footprint "eagle-import:1X01_WITHOUT_TEXT")
      (libsource (lib "eagle-import") (part "M01PTH_WITHOUT_TEXT"))
    )
    (comp (ref "JP129")
      (value "M01PTH_WITHOUT_TEXT")
      (footprint "eagle-import:1X01_WITHOUT_TEXT")
      (libsource (lib "eagle-import") (part "M01PTH_WITHOUT_TEXT"))
    )
    (comp (ref "JP130")
      (value "M01PTH_WITHOUT_TEXT")
      (footprint "eagle-import:1X01_WITHOUT_TEXT")
      (libsource (lib "eagle-import") (part "M01PTH_WITHOUT_TEXT"))
    )
    (comp (ref "JP131")
      (value "M01PTH_WITHOUT_TEXT")
      (footprint "eagle-import:1X01_WITHOUT_TEXT")
      (libsource (lib "eagle-import") (part "M01PTH_WITHOUT_TEXT"))
    )
    (comp (ref "JP132")
      (value "M01PTH_WITHOUT_TEXT")
      (footprint "eagle-import:1X01_WITHOUT_TEXT")
      (libsource (lib "eagle-import") (part "M01PTH_WITHOUT_TEXT"))
    )
    (comp (ref "JP133")
      (value "M01PTH_WITHOUT_TEXT")
      (footprint "eagle-import:1X01_WITHOUT_TEXT")
      (libsource (lib "eagle-import") (part "M01PTH_WITHOUT_TEXT"))
    )
    (comp (ref "JP134")
      (value "M01PTH_WITHOUT_TEXT")
      (footprint "eagle-import:1X01_WITHOUT_TEXT")
      (libsource (lib "eagle-import") (part "M01PTH_WITHOUT_TEXT"))
    )
    (comp (ref "JP135")
      (value "M01PTH_WITHOUT_TEXT")
      (footprint "eagle-import:1X01_WITHOUT_TEXT")
      (libsource (lib "eagle-import") (part "M01PTH_WITHOUT_TEXT"))
    )
    (comp (ref "JP136")
      (value "M01PTH_WITHOUT_TEXT")
      (footprint "eagle-import:1X01_WITHOUT_TEXT")
      (libsource (lib "eagle-import") (part "M01PTH_WITHOUT_TEXT"))
    )
    (comp (ref "JP137")
      (value "M01PTH_WITHOUT_TEXT")
      (footprint "eagle-import:1X01_WITHOUT_TEXT")
      (libsource (lib "eagle-import") (part "M01PTH_WITHOUT_TEXT"))
    )
    (comp (ref "JP138")
      (value "M01PTH_WITHOUT_TEXT")
      (footprint "eagle-import:1X01_WITHOUT_TEXT")
      (libsource (lib "eagle-import") (part "M01PTH_WITHOUT_TEXT"))
    )
    (comp (ref "JP139")
      (value "M01PTH_WITHOUT_TEXT")
      (footprint "eagle-import:1X01_WITHOUT_TEXT")
      (libsource (lib "eagle-import") (part "M01PTH_WITHOUT_TEXT"))
    )
    (comp (ref "JP140")
      (value "M01PTH_WITHOUT_TEXT")
      (footprint "eagle-import:1X01_WITHOUT_TEXT")
      (libsource (lib "eagle-import") (part "M01PTH_WITHOUT_TEXT"))
    )
    (comp (ref "JP141")
      (value "M01PTH_WITHOUT_TEXT")
      (footprint "eagle-import:1X01_WITHOUT_TEXT")
      (libsource (lib "eagle-import") (part "M01PTH_WITHOUT_TEXT"))
    )
    (comp (ref "JP142")
      (value "M01PTH_WITHOUT_TEXT")
      (footprint "eagle-import:1X01_WITHOUT_TEXT")
      (libsource (lib "eagle-import") (part "M01PTH_WITHOUT_TEXT"))
    )
    (comp (ref "JP143")
      (value "M01PTH_WITHOUT_TEXT")
      (footprint "eagle-import:1X01_WITHOUT_TEXT")
      (libsource (lib "eagle-import") (part "M01PTH_WITHOUT_TEXT"))
    )
    (comp (ref "JP144")
      (value "M01PTH_WITHOUT_TEXT")
      (footprint "eagle-import:1X01_WITHOUT_TEXT")
      (libsource (lib "eagle-import") (part "M01PTH_WITHOUT_TEXT"))
    )
    (comp (ref "JP145")
      (value "M01PTH_WITHOUT_TEXT")
      (footprint "eagle-import:1X01_WITHOUT_TEXT")
      (libsource (lib "eagle-import") (part "M01PTH_WITHOUT_TEXT"))
    )
    (comp (ref "JP146")
      (value "M01PTH_WITHOUT_TEXT")
      (footprint "eagle-import:1X01_WITHOUT_TEXT")
      (libsource (lib "eagle-import") (part "M01PTH_WITHOUT_TEXT"))
    )
    (comp (ref "JP147")
      (value "M01PTH_WITHOUT_TEXT")
      (footprint "eagle-import:1X01_WITHOUT_TEXT")
      (libsource (lib "eagle-import") (part "M01PTH_WITHOUT_TEXT"))
    )
    (comp (ref "JP148")
      (value "M01PTH_WITHOUT_TEXT")
      (footprint "eagle-import:1X01_WITHOUT_TEXT")
      (libsource (lib "eagle-import") (part "M01PTH_WITHOUT_TEXT"))
    )
    (comp (ref "JP149")
      (value "M01PTH_WITHOUT_TEXT")
      (footprint "eagle-import:1X01_WITHOUT_TEXT")
      (libsource (lib "eagle-import") (part "M01PTH_WITHOUT_TEXT"))
    )
    (comp (ref "JP150")
      (value "M01PTH_WITHOUT_TEXT")
      (footprint "eagle-import:1X01_WITHOUT_TEXT")
      (libsource (lib "eagle-import") (part "M01PTH_WITHOUT_TEXT"))
    )
    (comp (ref "JP151")
      (value "M01PTH_WITHOUT_TEXT")
      (footprint "eagle-import:1X01_WITHOUT_TEXT")
      (libsource (lib "eagle-import") (part "M01PTH_WITHOUT_TEXT"))
    )
    (comp (ref "JP152")
      (value "M01PTH_WITHOUT_TEXT")
      (footprint "eagle-import:1X01_WITHOUT_TEXT")
      (libsource (lib "eagle-import") (part "M01PTH_WITHOUT_TEXT"))
    )
    (comp (ref "JP153")
      (value "M01PTH_WITHOUT_TEXT")
      (footprint "eagle-import:1X01_WITHOUT_TEXT")
      (libsource (lib "eagle-import") (part "M01PTH_WITHOUT_TEXT"))
    )
    (comp (ref "JP154")
      (value "M01PTH_WITHOUT_TEXT")
      (footprint "eagle-import:1X01_WITHOUT_TEXT")
      (libsource (lib "eagle-import") (part "M01PTH_WITHOUT_TEXT"))
    )
    (comp (ref "JP155")
      (value "M01PTH_WITHOUT_TEXT")
      (footprint "eagle-import:1X01_WITHOUT_TEXT")
      (libsource (lib "eagle-import") (part "M01PTH_WITHOUT_TEXT"))
    )
    (comp (ref "JP156")
      (value "M01PTH_WITHOUT_TEXT")
      (footprint "eagle-import:1X01_WITHOUT_TEXT")
      (libsource (lib "eagle-import") (part "M01PTH_WITHOUT_TEXT"))
    )
    (comp (ref "JP157")
      (value "M01PTH_WITHOUT_TEXT")
      (footprint "eagle-import:1X01_WITHOUT_TEXT")
      (libsource (lib "eagle-import") (part "M01PTH_WITHOUT_TEXT"))
    )
    (comp (ref "JP158")
      (value "M01PTH_WITHOUT_TEXT")
      (footprint "eagle-import:1X01_WITHOUT_TEXT")
      (libsource (lib "eagle-import") (part "M01PTH_WITHOUT_TEXT"))
    )
    (comp (ref "JP159")
      (value "M01PTH_WITHOUT_TEXT")
      (footprint "eagle-import:1X01_WITHOUT_TEXT")
      (libsource (lib "eagle-import") (part "M01PTH_WITHOUT_TEXT"))
    )
    (comp (ref "JP160")
      (value "M01PTH_WITHOUT_TEXT")
      (footprint "eagle-import:1X01_WITHOUT_TEXT")
      (libsource (lib "eagle-import") (part "M01PTH_WITHOUT_TEXT"))
    )
    (comp (ref "JP161")
      (value "M01PTH_WITHOUT_TEXT")
      (footprint "eagle-import:1X01_WITHOUT_TEXT")
      (libsource (lib "eagle-import") (part "M01PTH_WITHOUT_TEXT"))
    )
    (comp (ref "JP162")
      (value "M01PTH_WITHOUT_TEXT")
      (footprint "eagle-import:1X01_WITHOUT_TEXT")
      (libsource (lib "eagle-import") (part "M01PTH_WITHOUT_TEXT"))
    )
    (comp (ref "JP163")
      (value "M01PTH_WITHOUT_TEXT")
      (footprint "eagle-import:1X01_WITHOUT_TEXT")
      (libsource (lib "eagle-import") (part "M01PTH_WITHOUT_TEXT"))
    )
    (comp (ref "JP164")
      (value "M01PTH_WITHOUT_TEXT")
      (footprint "eagle-import:1X01_WITHOUT_TEXT")
      (libsource (lib "eagle-import") (part "M01PTH_WITHOUT_TEXT"))
    )
    (comp (ref "JP165")
      (value "M01PTH_WITHOUT_TEXT")
      (footprint "eagle-import:1X01_WITHOUT_TEXT")
      (libsource (lib "eagle-import") (part "M01PTH_WITHOUT_TEXT"))
    )
    (comp (ref "JP166")
      (value "M01PTH_WITHOUT_TEXT")
      (footprint "eagle-import:1X01_WITHOUT_TEXT")
      (libsource (lib "eagle-import") (part "M01PTH_WITHOUT_TEXT"))
    )
    (comp (ref "JP167")
      (value "M01PTH_WITHOUT_TEXT")
      (footprint "eagle-import:1X01_WITHOUT_TEXT")
      (libsource (lib "eagle-import") (part "M01PTH_WITHOUT_TEXT"))
    )
    (comp (ref "JP168")
      (value "M01PTH_WITHOUT_TEXT")
      (footprint "eagle-import:1X01_WITHOUT_TEXT")
      (libsource (lib "eagle-import") (part "M01PTH_WITHOUT_TEXT"))
    )
    (comp (ref "JP169")
      (value "M01PTH_WITHOUT_TEXT")
      (footprint "eagle-import:1X01_WITHOUT_TEXT")
      (libsource (lib "eagle-import") (part "M01PTH_WITHOUT_TEXT"))
    )
    (comp (ref "JP170")
      (value "M01PTH_WITHOUT_TEXT")
      (footprint "eagle-import:1X01_WITHOUT_TEXT")
      (libsource (lib "eagle-import") (part "M01PTH_WITHOUT_TEXT"))
    )
    (comp (ref "JP171")
      (value "M01PTH_WITHOUT_TEXT")
      (footprint "eagle-import:1X01_WITHOUT_TEXT")
      (libsource (lib "eagle-import") (part "M01PTH_WITHOUT_TEXT"))
    )
    (comp (ref "JP172")
      (value "M01PTH_WITHOUT_TEXT")
      (footprint "eagle-import:1X01_WITHOUT_TEXT")
      (libsource (lib "eagle-import") (part "M01PTH_WITHOUT_TEXT"))
    )
    (comp (ref "JP173")
      (value "M01PTH_WITHOUT_TEXT")
      (footprint "eagle-import:1X01_WITHOUT_TEXT")
      (libsource (lib "eagle-import") (part "M01PTH_WITHOUT_TEXT"))
    )
    (comp (ref "JP174")
      (value "M01PTH_WITHOUT_TEXT")
      (footprint "eagle-import:1X01_WITHOUT_TEXT")
      (libsource (lib "eagle-import") (part "M01PTH_WITHOUT_TEXT"))
    )
    (comp (ref "JP175")
      (value "M01PTH_WITHOUT_TEXT")
      (footprint "eagle-import:1X01_WITHOUT_TEXT")
      (libsource (lib "eagle-import") (part "M01PTH_WITHOUT_TEXT"))
    )
    (comp (ref "JP176")
      (value "M01PTH_WITHOUT_TEXT")
      (footprint "eagle-import:1X01_WITHOUT_TEXT")
      (libsource (lib "eagle-import") (part "M01PTH_WITHOUT_TEXT"))
    )
    (comp (ref "JP177")
      (value "M01PTH_WITHOUT_TEXT")
      (footprint "eagle-import:1X01_WITHOUT_TEXT")
      (libsource (lib "eagle-import") (part "M01PTH_WITHOUT_TEXT"))
    )
    (comp (ref "JP178")
      (value "M01PTH_WITHOUT_TEXT")
      (footprint "eagle-import:1X01_WITHOUT_TEXT")
      (libsource (lib "eagle-import") (part "M01PTH_WITHOUT_TEXT"))
    )
    (comp (ref "JP179")
      (value "M01PTH_WITHOUT_TEXT")
      (footprint "eagle-import:1X01_WITHOUT_TEXT")
      (libsource (lib "eagle-import") (part "M01PTH_WITHOUT_TEXT"))
    )
    (comp (ref "JP180")
      (value "M01PTH_WITHOUT_TEXT")
      (footprint "eagle-import:1X01_WITHOUT_TEXT")
      (libsource (lib "eagle-import") (part "M01PTH_WITHOUT_TEXT"))
    )
    (comp (ref "JP181")
      (value "M01PTH_WITHOUT_TEXT")
      (footprint "eagle-import:1X01_WITHOUT_TEXT")
      (libsource (lib "eagle-import") (part "M01PTH_WITHOUT_TEXT"))
    )
    (comp (ref "JP182")
      (value "M01PTH_WITHOUT_TEXT")
      (footprint "eagle-import:1X01_WITHOUT_TEXT")
      (libsource (lib "eagle-import") (part "M01PTH_WITHOUT_TEXT"))
    )
    (comp (ref "JP183")
      (value "M01PTH_WITHOUT_TEXT")
      (footprint "eagle-import:1X01_WITHOUT_TEXT")
      (libsource (lib "eagle-import") (part "M01PTH_WITHOUT_TEXT"))
    )
    (comp (ref "JP184")
      (value "M01PTH_WITHOUT_TEXT")
      (footprint "eagle-import:1X01_WITHOUT_TEXT")
      (libsource (lib "eagle-import") (part "M01PTH_WITHOUT_TEXT"))
    )
    (comp (ref "JP185")
      (value "M01PTH_WITHOUT_TEXT")
      (footprint "eagle-import:1X01_WITHOUT_TEXT")
      (libsource (lib "eagle-import") (part "M01PTH_WITHOUT_TEXT"))
    )
    (comp (ref "JP186")
      (value "M01PTH_WITHOUT_TEXT")
      (footprint "eagle-import:1X01_WITHOUT_TEXT")
      (libsource (lib "eagle-import") (part "M01PTH_WITHOUT_TEXT"))
    )
    (comp (ref "JP187")
      (value "M01PTH_WITHOUT_TEXT")
      (footprint "eagle-import:1X01_WITHOUT_TEXT")
      (libsource (lib "eagle-import") (part "M01PTH_WITHOUT_TEXT"))
    )
    (comp (ref "JP188")
      (value "M01PTH_WITHOUT_TEXT")
      (footprint "eagle-import:1X01_WITHOUT_TEXT")
      (libsource (lib "eagle-import") (part "M01PTH_WITHOUT_TEXT"))
    )
    (comp (ref "JP189")
      (value "M01PTH_WITHOUT_TEXT")
      (footprint "eagle-import:1X01_WITHOUT_TEXT")
      (libsource (lib "eagle-import") (part "M01PTH_WITHOUT_TEXT"))
    )
    (comp (ref "JP190")
      (value "M01PTH_WITHOUT_TEXT")
      (footprint "eagle-import:1X01_WITHOUT_TEXT")
      (libsource (lib "eagle-import") (part "M01PTH_WITHOUT_TEXT"))
    )
    (comp (ref "JP191")
      (value "M01PTH_WITHOUT_TEXT")
      (footprint "eagle-import:1X01_WITHOUT_TEXT")
      (libsource (lib "eagle-import") (part "M01PTH_WITHOUT_TEXT"))
    )
    (comp (ref "JP192")
      (value "M01PTH_WITHOUT_TEXT")
      (footprint "eagle-import:1X01_WITHOUT_TEXT")
      (libsource (lib "eagle-import") (part "M01PTH_WITHOUT_TEXT"))
    )
    (comp (ref "JP193")
      (value "M01PTH_WITHOUT_TEXT")
      (footprint "eagle-import:1X01_WITHOUT_TEXT")
      (libsource (lib "eagle-import") (part "M01PTH_WITHOUT_TEXT"))
    )
    (comp (ref "JP194")
      (value "M01PTH_WITHOUT_TEXT")
      (footprint "eagle-import:1X01_WITHOUT_TEXT")
      (libsource (lib "eagle-import") (part "M01PTH_WITHOUT_TEXT"))
    )
    (comp (ref "JP195")
      (value "M01PTH_WITHOUT_TEXT")
      (footprint "eagle-import:1X01_WITHOUT_TEXT")
      (libsource (lib "eagle-import") (part "M01PTH_WITHOUT_TEXT"))
    )
    (comp (ref "JP196")
      (value "M01PTH_WITHOUT_TEXT")
      (footprint "eagle-import:1X01_WITHOUT_TEXT")
      (libsource (lib "eagle-import") (part "M01PTH_WITHOUT_TEXT"))
    )
    (comp (ref "JP197")
      (value "M01PTH_WITHOUT_TEXT")
      (footprint "eagle-import:1X01_WITHOUT_TEXT")
      (libsource (lib "eagle-import") (part "M01PTH_WITHOUT_TEXT"))
    )
    (comp (ref "JP198")
      (value "M01PTH_WITHOUT_TEXT")
      (footprint "eagle-import:1X01_WITHOUT_TEXT")
      (libsource (lib "eagle-import") (part "M01PTH_WITHOUT_TEXT"))
    )
    (comp (ref "JP199")
      (value "M01PTH_WITHOUT_TEXT")
      (footprint "eagle-import:1X01_WITHOUT_TEXT")
      (libsource (lib "eagle-import") (part "M01PTH_WITHOUT_TEXT"))
    )
    (comp (ref "JP200")
      (value "M01PTH_WITHOUT_TEXT")
      (footprint "eagle-import:1X01_WITHOUT_TEXT")
      (libsource (lib "eagle-import") (part "M01PTH_WITHOUT_TEXT"))
    )
    (comp (ref "JP201")
      (value "M01PTH_WITHOUT_TEXT")
      (footprint "eagle-import:1X01_WITHOUT_TEXT")
      (libsource (lib "eagle-import") (part "M01PTH_WITHOUT_TEXT"))
    )
    (comp (ref "JP202")
      (value "M01PTH_WITHOUT_TEXT")
      (footprint "eagle-import:1X01_WITHOUT_TEXT")
      (libsource (lib "eagle-import") (part "M01PTH_WITHOUT_TEXT"))
    )
    (comp (ref "JP203")
      (value "M01PTH_WITHOUT_TEXT")
      (footprint "eagle-import:1X01_WITHOUT_TEXT")
      (libsource (lib "eagle-import") (part "M01PTH_WITHOUT_TEXT"))
    )
    (comp (ref "JP204")
      (value "M01PTH_WITHOUT_TEXT")
      (footprint "eagle-import:1X01_WITHOUT_TEXT")
      (libsource (lib "eagle-import") (part "M01PTH_WITHOUT_TEXT"))
    )
    (comp (ref "JP205")
      (value "M01PTH_WITHOUT_TEXT")
      (footprint "eagle-import:1X01_WITHOUT_TEXT")
      (libsource (lib "eagle-import") (part "M01PTH_WITHOUT_TEXT"))
    )
    (comp (ref "JP206")
      (value "M01PTH_WITHOUT_TEXT")
      (footprint "eagle-import:1X01_WITHOUT_TEXT")
      (libsource (lib "eagle-import") (part "M01PTH_WITHOUT_TEXT"))
    )
    (comp (ref "JP207")
      (value "M01PTH_WITHOUT_TEXT")
      (footprint "eagle-import:1X01_WITHOUT_TEXT")
      (libsource (lib "eagle-import") (part "M01PTH_WITHOUT_TEXT"))
    )
    (comp (ref "JP208")
      (value "M01PTH_WITHOUT_TEXT")
      (footprint "eagle-import:1X01_WITHOUT_TEXT")
      (libsource (lib "eagle-import") (part "M01PTH_WITHOUT_TEXT"))
    )
    (comp (ref "JP209")
      (value "M01PTH_WITHOUT_TEXT")
      (footprint "eagle-import:1X01_WITHOUT_TEXT")
      (libsource (lib "eagle-import") (part "M01PTH_WITHOUT_TEXT"))
    )
    (comp (ref "JP210")
      (value "M01PTH_WITHOUT_TEXT")
      (footprint "eagle-import:1X01_WITHOUT_TEXT")
      (libsource (lib "eagle-import") (part "M01PTH_WITHOUT_TEXT"))
    )
    (comp (ref "JP211")
      (value "M01PTH_WITHOUT_TEXT")
      (footprint "eagle-import:1X01_WITHOUT_TEXT")
      (libsource (lib "eagle-import") (part "M01PTH_WITHOUT_TEXT"))
    )
    (comp (ref "JP212")
      (value "M01PTH_WITHOUT_TEXT")
      (footprint "eagle-import:1X01_WITHOUT_TEXT")
      (libsource (lib "eagle-import") (part "M01PTH_WITHOUT_TEXT"))
    )
    (comp (ref "JP213")
      (value "M01PTH_WITHOUT_TEXT")
      (footprint "eagle-import:1X01_WITHOUT_TEXT")
      (libsource (lib "eagle-import") (part "M01PTH_WITHOUT_TEXT"))
    )
    (comp (ref "JP214")
      (value "M01PTH_WITHOUT_TEXT")
      (footprint "eagle-import:1X01_WITHOUT_TEXT")
      (libsource (lib "eagle-import") (part "M01PTH_WITHOUT_TEXT"))
    )
    (comp (ref "JP215")
      (value "M01PTH_WITHOUT_TEXT")
      (footprint "eagle-import:1X01_WITHOUT_TEXT")
      (libsource (lib "eagle-import") (part "M01PTH_WITHOUT_TEXT"))
    )
    (comp (ref "JP216")
      (value "M01PTH_WITHOUT_TEXT")
      (footprint "eagle-import:1X01_WITHOUT_TEXT")
      (libsource (lib "eagle-import") (part "M01PTH_WITHOUT_TEXT"))
    )
    (comp (ref "JP217")
      (value "M01PTH_WITHOUT_TEXT")
      (footprint "eagle-import:1X01_WITHOUT_TEXT")
      (libsource (lib "eagle-import") (part "M01PTH_WITHOUT_TEXT"))
    )
    (comp (ref "JP218")
      (value "M01PTH_WITHOUT_TEXT")
      (footprint "eagle-import:1X01_WITHOUT_TEXT")
      (libsource (lib "eagle-import") (part "M01PTH_WITHOUT_TEXT"))
    )
    (comp (ref "JP219")
      (value "M01PTH_WITHOUT_TEXT")
      (footprint "eagle-import:1X01_WITHOUT_TEXT")
      (libsource (lib "eagle-import") (part "M01PTH_WITHOUT_TEXT"))
    )
    (comp (ref "JP220")
      (value "M01PTH_WITHOUT_TEXT")
      (footprint "eagle-import:1X01_WITHOUT_TEXT")
      (libsource (lib "eagle-import") (part "M01PTH_WITHOUT_TEXT"))
    )
    (comp (ref "JP221")
      (value "M01PTH_WITHOUT_TEXT")
      (footprint "eagle-import:1X01_WITHOUT_TEXT")
      (libsource (lib "eagle-import") (part "M01PTH_WITHOUT_TEXT"))
    )
    (comp (ref "JP222")
      (value "M01PTH_WITHOUT_TEXT")
      (footprint "eagle-import:1X01_WITHOUT_TEXT")
      (libsource (lib "eagle-import") (part "M01PTH_WITHOUT_TEXT"))
    )
    (comp (ref "JP223")
      (value "M01PTH_WITHOUT_TEXT")
      (footprint "eagle-import:1X01_WITHOUT_TEXT")
      (libsource (lib "eagle-import") (part "M01PTH_WITHOUT_TEXT"))
    )
    (comp (ref "JP224")
      (value "M01PTH_WITHOUT_TEXT")
      (footprint "eagle-import:1X01_WITHOUT_TEXT")
      (libsource (lib "eagle-import") (part "M01PTH_WITHOUT_TEXT"))
    )
    (comp (ref "JP225")
      (value "M01PTH_WITHOUT_TEXT")
      (footprint "eagle-import:1X01_WITHOUT_TEXT")
      (libsource (lib "eagle-import") (part "M01PTH_WITHOUT_TEXT"))
    )
    (comp (ref "JP226")
      (value "M01PTH_WITHOUT_TEXT")
      (footprint "eagle-import:1X01_WITHOUT_TEXT")
      (libsource (lib "eagle-import") (part "M01PTH_WITHOUT_TEXT"))
    )
    (comp (ref "JP227")
      (value "M01PTH_WITHOUT_TEXT")
      (footprint "eagle-import:1X01_WITHOUT_TEXT")
      (libsource (lib "eagle-import") (part "M01PTH_WITHOUT_TEXT"))
    )
    (comp (ref "JP228")
      (value "M01PTH_WITHOUT_TEXT")
      (footprint "eagle-import:1X01_WITHOUT_TEXT")
      (libsource (lib "eagle-import") (part "M01PTH_WITHOUT_TEXT"))
    )
    (comp (ref "JP229")
      (value "M01PTH_WITHOUT_TEXT")
      (footprint "eagle-import:1X01_WITHOUT_TEXT")
      (libsource (lib "eagle-import") (part "M01PTH_WITHOUT_TEXT"))
    )
    (comp (ref "JP230")
      (value "M01PTH_WITHOUT_TEXT")
      (footprint "eagle-import:1X01_WITHOUT_TEXT")
      (libsource (lib "eagle-import") (part "M01PTH_WITHOUT_TEXT"))
    )
    (comp (ref "JP231")
      (value "M01PTH_WITHOUT_TEXT")
      (footprint "eagle-import:1X01_WITHOUT_TEXT")
      (libsource (lib "eagle-import") (part "M01PTH_WITHOUT_TEXT"))
    )
    (comp (ref "JP232")
      (value "M01PTH_WITHOUT_TEXT")
      (footprint "eagle-import:1X01_WITHOUT_TEXT")
      (libsource (lib "eagle-import") (part "M01PTH_WITHOUT_TEXT"))
    )
    (comp (ref "JP233")
      (value "M01PTH_WITHOUT_TEXT")
      (footprint "eagle-import:1X01_WITHOUT_TEXT")
      (libsource (lib "eagle-import") (part "M01PTH_WITHOUT_TEXT"))
    )
    (comp (ref "JP234")
      (value "M01PTH_WITHOUT_TEXT")
      (footprint "eagle-import:1X01_WITHOUT_TEXT")
      (libsource (lib "eagle-import") (part "M01PTH_WITHOUT_TEXT"))
    )
    (comp (ref "JP235")
      (value "M01PTH_WITHOUT_TEXT")
      (footprint "eagle-import:1X01_WITHOUT_TEXT")
      (libsource (lib "eagle-import") (part "M01PTH_WITHOUT_TEXT"))
    )
    (comp (ref "JP236")
      (value "M01PTH_WITHOUT_TEXT")
      (footprint "eagle-import:1X01_WITHOUT_TEXT")
      (libsource (lib "eagle-import") (part "M01PTH_WITHOUT_TEXT"))
    )
    (comp (ref "JP237")
      (value "M01PTH_WITHOUT_TEXT")
      (footprint "eagle-import:1X01_WITHOUT_TEXT")
      (libsource (lib "eagle-import") (part "M01PTH_WITHOUT_TEXT"))
    )
    (comp (ref "JP238")
      (value "M01PTH_WITHOUT_TEXT")
      (footprint "eagle-import:1X01_WITHOUT_TEXT")
      (libsource (lib "eagle-import") (part "M01PTH_WITHOUT_TEXT"))
    )
    (comp (ref "JP239")
      (value "M01PTH_WITHOUT_TEXT")
      (footprint "eagle-import:1X01_WITHOUT_TEXT")
      (libsource (lib "eagle-import") (part "M01PTH_WITHOUT_TEXT"))
    )
    (comp (ref "JP240")
      (value "M01PTH_WITHOUT_TEXT")
      (footprint "eagle-import:1X01_WITHOUT_TEXT")
      (libsource (lib "eagle-import") (part "M01PTH_WITHOUT_TEXT"))
    )
    (comp (ref "JP241")
      (value "M01PTH_WITHOUT_TEXT")
      (footprint "eagle-import:1X01_WITHOUT_TEXT")
      (libsource (lib "eagle-import") (part "M01PTH_WITHOUT_TEXT"))
    )
    (comp (ref "JP242")
      (value "M01PTH_WITHOUT_TEXT")
      (footprint "eagle-import:1X01_WITHOUT_TEXT")
      (libsource (lib "eagle-import") (part "M01PTH_WITHOUT_TEXT"))
    )
    (comp (ref "JP243")
      (value "M01PTH_WITHOUT_TEXT")
      (footprint "eagle-import:1X01_WITHOUT_TEXT")
      (libsource (lib "eagle-import") (part "M01PTH_WITHOUT_TEXT"))
    )
    (comp (ref "JP244")
      (value "M01PTH_WITHOUT_TEXT")
      (footprint "eagle-import:1X01_WITHOUT_TEXT")
      (libsource (lib "eagle-import") (part "M01PTH_WITHOUT_TEXT"))
    )
    (comp (ref "JP245")
      (value "M01PTH_WITHOUT_TEXT")
      (footprint "eagle-import:1X01_WITHOUT_TEXT")
      (libsource (lib "eagle-import") (part "M01PTH_WITHOUT_TEXT"))
    )
    (comp (ref "JP246")
      (value "M01PTH_WITHOUT_TEXT")
      (footprint "eagle-import:1X01_WITHOUT_TEXT")
      (libsource (lib "eagle-import") (part "M01PTH_WITHOUT_TEXT"))
    )
    (comp (ref "JP247")
      (value "M01PTH_WITHOUT_TEXT")
      (footprint "eagle-import:1X01_WITHOUT_TEXT")
      (libsource (lib "eagle-import") (part "M01PTH_WITHOUT_TEXT"))
    )
    (comp (ref "JP248")
      (value "M01PTH_WITHOUT_TEXT")
      (footprint "eagle-import:1X01_WITHOUT_TEXT")
      (libsource (lib "eagle-import") (part "M01PTH_WITHOUT_TEXT"))
    )
    (comp (ref "JP249")
      (value "M01PTH_WITHOUT_TEXT")
      (footprint "eagle-import:1X01_WITHOUT_TEXT")
      (libsource (lib "eagle-import") (part "M01PTH_WITHOUT_TEXT"))
    )
    (comp (ref "JP250")
      (value "M01PTH_WITHOUT_TEXT")
      (footprint "eagle-import:1X01_WITHOUT_TEXT")
      (libsource (lib "eagle-import") (part "M01PTH_WITHOUT_TEXT"))
    )
    (comp (ref "JP251")
      (value "M01PTH_WITHOUT_TEXT")
      (footprint "eagle-import:1X01_WITHOUT_TEXT")
      (libsource (lib "eagle-import") (part "M01PTH_WITHOUT_TEXT"))
    )
    (comp (ref "JP252")
      (value "M01PTH_WITHOUT_TEXT")
      (footprint "eagle-import:1X01_WITHOUT_TEXT")
      (libsource (lib "eagle-import") (part "M01PTH_WITHOUT_TEXT"))
    )
    (comp (ref "JP253")
      (value "M01PTH_WITHOUT_TEXT")
      (footprint "eagle-import:1X01_WITHOUT_TEXT")
      (libsource (lib "eagle-import") (part "M01PTH_WITHOUT_TEXT"))
    )
    (comp (ref "JP254")
      (value "M01PTH_WITHOUT_TEXT")
      (footprint "eagle-import:1X01_WITHOUT_TEXT")
      (libsource (lib "eagle-import") (part "M01PTH_WITHOUT_TEXT"))
    )
    (comp (ref "JP255")
      (value "M01PTH_WITHOUT_TEXT")
      (footprint "eagle-import:1X01_WITHOUT_TEXT")
      (libsource (lib "eagle-import") (part "M01PTH_WITHOUT_TEXT"))
    )
    (comp (ref "JP256")
      (value "M01PTH_WITHOUT_TEXT")
      (footprint "eagle-import:1X01_WITHOUT_TEXT")
      (libsource (lib "eagle-import") (part "M01PTH_WITHOUT_TEXT"))
    )
    (comp (ref "JP257")
      (value "M01PTH_WITHOUT_TEXT")
      (footprint "eagle-import:1X01_WITHOUT_TEXT")
      (libsource (lib "eagle-import") (part "M01PTH_WITHOUT_TEXT"))
    )
    (comp (ref "JP258")
      (value "M01PTH_WITHOUT_TEXT")
      (footprint "eagle-import:1X01_WITHOUT_TEXT")
      (libsource (lib "eagle-import") (part "M01PTH_WITHOUT_TEXT"))
    )
    (comp (ref "JP259")
      (value "M01PTH_WITHOUT_TEXT")
      (footprint "eagle-import:1X01_WITHOUT_TEXT")
      (libsource (lib "eagle-import") (part "M01PTH_WITHOUT_TEXT"))
    )
    (comp (ref "JP260")
      (value "M01PTH_WITHOUT_TEXT")
      (footprint "eagle-import:1X01_WITHOUT_TEXT")
      (libsource (lib "eagle-import") (part "M01PTH_WITHOUT_TEXT"))
    )
    (comp (ref "JP261")
      (value "M01PTH_WITHOUT_TEXT")
      (footprint "eagle-import:1X01_WITHOUT_TEXT")
      (libsource (lib "eagle-import") (part "M01PTH_WITHOUT_TEXT"))
    )
    (comp (ref "JP262")
      (value "M01PTH_WITHOUT_TEXT")
      (footprint "eagle-import:1X01_WITHOUT_TEXT")
      (libsource (lib "eagle-import") (part "M01PTH_WITHOUT_TEXT"))
    )
    (comp (ref "JP263")
      (value "M01PTH_WITHOUT_TEXT")
      (footprint "eagle-import:1X01_WITHOUT_TEXT")
      (libsource (lib "eagle-import") (part "M01PTH_WITHOUT_TEXT"))
    )
    (comp (ref "JP264")
      (value "M01PTH_WITHOUT_TEXT")
      (footprint "eagle-import:1X01_WITHOUT_TEXT")
      (libsource (lib "eagle-import") (part "M01PTH_WITHOUT_TEXT"))
    )
    (comp (ref "JP265")
      (value "M01PTH_WITHOUT_TEXT")
      (footprint "eagle-import:1X01_WITHOUT_TEXT")
      (libsource (lib "eagle-import") (part "M01PTH_WITHOUT_TEXT"))
    )
    (comp (ref "JP266")
      (value "M01PTH_WITHOUT_TEXT")
      (footprint "eagle-import:1X01_WITHOUT_TEXT")
      (libsource (lib "eagle-import") (part "M01PTH_WITHOUT_TEXT"))
    )
    (comp (ref "JP267")
      (value "M01PTH_WITHOUT_TEXT")
      (footprint "eagle-import:1X01_WITHOUT_TEXT")
      (libsource (lib "eagle-import") (part "M01PTH_WITHOUT_TEXT"))
    )
    (comp (ref "JP268")
      (value "M01PTH_WITHOUT_TEXT")
      (footprint "eagle-import:1X01_WITHOUT_TEXT")
      (libsource (lib "eagle-import") (part "M01PTH_WITHOUT_TEXT"))
    )
    (comp (ref "JP269")
      (value "M01PTH_WITHOUT_TEXT")
      (footprint "eagle-import:1X01_WITHOUT_TEXT")
      (libsource (lib "eagle-import") (part "M01PTH_WITHOUT_TEXT"))
    )
    (comp (ref "JP270")
      (value "M01PTH_WITHOUT_TEXT")
      (footprint "eagle-import:1X01_WITHOUT_TEXT")
      (libsource (lib "eagle-import") (part "M01PTH_WITHOUT_TEXT"))
    )
    (comp (ref "JP271")
      (value "M01PTH_WITHOUT_TEXT")
      (footprint "eagle-import:1X01_WITHOUT_TEXT")
      (libsource (lib "eagle-import") (part "M01PTH_WITHOUT_TEXT"))
    )
    (comp (ref "JP272")
      (value "M01PTH_WITHOUT_TEXT")
      (footprint "eagle-import:1X01_WITHOUT_TEXT")
      (libsource (lib "eagle-import") (part "M01PTH_WITHOUT_TEXT"))
    )
    (comp (ref "JP273")
      (value "M01PTH_WITHOUT_TEXT")
      (footprint "eagle-import:1X01_WITHOUT_TEXT")
      (libsource (lib "eagle-import") (part "M01PTH_WITHOUT_TEXT"))
    )
    (comp (ref "JP274")
      (value "M01PTH_WITHOUT_TEXT")
      (footprint "eagle-import:1X01_WITHOUT_TEXT")
      (libsource (lib "eagle-import") (part "M01PTH_WITHOUT_TEXT"))
    )
    (comp (ref "JP275")
      (value "M01PTH_WITHOUT_TEXT")
      (footprint "eagle-import:1X01_WITHOUT_TEXT")
      (libsource (lib "eagle-import") (part "M01PTH_WITHOUT_TEXT"))
    )
    (comp (ref "JP276")
      (value "M01PTH_WITHOUT_TEXT")
      (footprint "eagle-import:1X01_WITHOUT_TEXT")
      (libsource (lib "eagle-import") (part "M01PTH_WITHOUT_TEXT"))
    )
    (comp (ref "JP277")
      (value "M01PTH_WITHOUT_TEXT")
      (footprint "eagle-import:1X01_WITHOUT_TEXT")
      (libsource (lib "eagle-import") (part "M01PTH_WITHOUT_TEXT"))
    )
    (comp (ref "JP278")
      (value "M01PTH_WITHOUT_TEXT")
      (footprint "eagle-import:1X01_WITHOUT_TEXT")
      (libsource (lib "eagle-import") (part "M01PTH_WITHOUT_TEXT"))
    )
    (comp (ref "JP279")
      (value "M01PTH_WITHOUT_TEXT")
      (footprint "eagle-import:1X01_WITHOUT_TEXT")
      (libsource (lib "eagle-import") (part "M01PTH_WITHOUT_TEXT"))
    )
    (comp (ref "JP280")
      (value "M01PTH_WITHOUT_TEXT")
      (footprint "eagle-import:1X01_WITHOUT_TEXT")
      (libsource (lib "eagle-import") (part "M01PTH_WITHOUT_TEXT"))
    )
    (comp (ref "JP281")
      (value "M01PTH_WITHOUT_TEXT")
      (footprint "eagle-import:1X01_WITHOUT_TEXT")
      (libsource (lib "eagle-import") (part "M01PTH_WITHOUT_TEXT"))
    )
    (comp (ref "JP282")
      (value "M01PTH_WITHOUT_TEXT")
      (footprint "eagle-import:1X01_WITHOUT_TEXT")
      (libsource (lib "eagle-import") (part "M01PTH_WITHOUT_TEXT"))
    )
    (comp (ref "JP283")
      (value "M01PTH_WITHOUT_TEXT")
      (footprint "eagle-import:1X01_WITHOUT_TEXT")
      (libsource (lib "eagle-import") (part "M01PTH_WITHOUT_TEXT"))
    )
    (comp (ref "JP284")
      (value "M01PTH_WITHOUT_TEXT")
      (footprint "eagle-import:1X01_WITHOUT_TEXT")
      (libsource (lib "eagle-import") (part "M01PTH_WITHOUT_TEXT"))
    )
    (comp (ref "JP285")
      (value "M01PTH_WITHOUT_TEXT")
      (footprint "eagle-import:1X01_WITHOUT_TEXT")
      (libsource (lib "eagle-import") (part "M01PTH_WITHOUT_TEXT"))
    )
    (comp (ref "JP286")
      (value "M01PTH_WITHOUT_TEXT")
      (footprint "eagle-import:1X01_WITHOUT_TEXT")
      (libsource (lib "eagle-import") (part "M01PTH_WITHOUT_TEXT"))
    )
    (comp (ref "JP287")
      (value "M01PTH_WITHOUT_TEXT")
      (footprint "eagle-import:1X01_WITHOUT_TEXT")
      (libsource (lib "eagle-import") (part "M01PTH_WITHOUT_TEXT"))
    )
    (comp (ref "JP288")
      (value "M01PTH_WITHOUT_TEXT")
      (footprint "eagle-import:1X01_WITHOUT_TEXT")
      (libsource (lib "eagle-import") (part "M01PTH_WITHOUT_TEXT"))
    )
    (comp (ref "JP289")
      (value "M01PTH_WITHOUT_TEXT")
      (footprint "eagle-import:1X01_WITHOUT_TEXT")
      (libsource (lib "eagle-import") (part "M01PTH_WITHOUT_TEXT"))
    )
    (comp (ref "JP290")
      (value "M01PTH_WITHOUT_TEXT")
      (footprint "eagle-import:1X01_WITHOUT_TEXT")
      (libsource (lib "eagle-import") (part "M01PTH_WITHOUT_TEXT"))
    )
    (comp (ref "JP291")
      (value "M01PTH_WITHOUT_TEXT")
      (footprint "eagle-import:1X01_WITHOUT_TEXT")
      (libsource (lib "eagle-import") (part "M01PTH_WITHOUT_TEXT"))
    )
    (comp (ref "JP292")
      (value "M01PTH_WITHOUT_TEXT")
      (footprint "eagle-import:1X01_WITHOUT_TEXT")
      (libsource (lib "eagle-import") (part "M01PTH_WITHOUT_TEXT"))
    )
    (comp (ref "JP293")
      (value "M01PTH_WITHOUT_TEXT")
      (footprint "eagle-import:1X01_WITHOUT_TEXT")
      (libsource (lib "eagle-import") (part "M01PTH_WITHOUT_TEXT"))
    )
    (comp (ref "JP294")
      (value "M01PTH_WITHOUT_TEXT")
      (footprint "eagle-import:1X01_WITHOUT_TEXT")
      (libsource (lib "eagle-import") (part "M01PTH_WITHOUT_TEXT"))
    )
    (comp (ref "JP295")
      (value "M01PTH_WITHOUT_TEXT")
      (footprint "eagle-import:1X01_WITHOUT_TEXT")
      (libsource (lib "eagle-import") (part "M01PTH_WITHOUT_TEXT"))
    )
    (comp (ref "JP296")
      (value "M01PTH_WITHOUT_TEXT")
      (footprint "eagle-import:1X01_WITHOUT_TEXT")
      (libsource (lib "eagle-import") (part "M01PTH_WITHOUT_TEXT"))
    )
    (comp (ref "JP297")
      (value "M01PTH_WITHOUT_TEXT")
      (footprint "eagle-import:1X01_WITHOUT_TEXT")
      (libsource (lib "eagle-import") (part "M01PTH_WITHOUT_TEXT"))
    )
    (comp (ref "JP298")
      (value "M01PTH_WITHOUT_TEXT")
      (footprint "eagle-import:1X01_WITHOUT_TEXT")
      (libsource (lib "eagle-import") (part "M01PTH_WITHOUT_TEXT"))
    )
    (comp (ref "JP299")
      (value "M01PTH_WITHOUT_TEXT")
      (footprint "eagle-import:1X01_WITHOUT_TEXT")
      (libsource (lib "eagle-import") (part "M01PTH_WITHOUT_TEXT"))
    )
    (comp (ref "JP300")
      (value "M01PTH_WITHOUT_TEXT")
      (footprint "eagle-import:1X01_WITHOUT_TEXT")
      (libsource (lib "eagle-import") (part "M01PTH_WITHOUT_TEXT"))
    )
    (comp (ref "JP1201")
      (value "M01PTH_SMD_3.25X0.85MM_NO_SILK")
      (footprint "eagle-import:1X01_SMD_3.25X0.85MM_NO_SILK")
      (libsource (lib "eagle-import") (part "M01PTH_SMD_3.25X0.85MM_NO_SILK"))
    )
    (comp (ref "JP1202")
      (value "M01PTH_SMD_3.25X0.85MM_NO_SILK")
      (footprint "eagle-import:1X01_SMD_3.25X0.85MM_NO_SILK")
      (libsource (lib "eagle-import") (part "M01PTH_SMD_3.25X0.85MM_NO_SILK"))
    )
    (comp (ref "JP1203")
      (value "M01PTH_SMD_3.25X0.85MM_NO_SILK")
      (footprint "eagle-import:1X01_SMD_3.25X0.85MM_NO_SILK")
      (libsource (lib "eagle-import") (part "M01PTH_SMD_3.25X0.85MM_NO_SILK"))
    )
    (comp (ref "JP1204")
      (value "M01PTH_SMD_3.25X0.85MM_NO_SILK")
      (footprint "eagle-import:1X01_SMD_3.25X0.85MM_NO_SILK")
      (libsource (lib "eagle-import") (part "M01PTH_SMD_3.25X0.85MM_NO_SILK"))
    )
    (comp (ref "JP1205")
      (value "M01PTH_SMD_3.25X0.85MM_NO_SILK")
      (footprint "eagle-import:1X01_SMD_3.25X0.85MM_NO_SILK")
      (libsource (lib "eagle-import") (part "M01PTH_SMD_3.25X0.85MM_NO_SILK"))
    )
    (comp (ref "JP1206")
      (value "M01PTH_SMD_3.25X0.85MM_NO_SILK")
      (footprint "eagle-import:1X01_SMD_3.25X0.85MM_NO_SILK")
      (libsource (lib "eagle-import") (part "M01PTH_SMD_3.25X0.85MM_NO_SILK"))
    )
    (comp (ref "JP1207")
      (value "M01PTH_SMD_3.25X0.85MM_NO_SILK")
      (footprint "eagle-import:1X01_SMD_3.25X0.85MM_NO_SILK")
      (libsource (lib "eagle-import") (part "M01PTH_SMD_3.25X0.85MM_NO_SILK"))
    )
    (comp (ref "JP1208")
      (value "M01PTH_SMD_3.25X0.85MM_NO_SILK")
      (footprint "eagle-import:1X01_SMD_3.25X0.85MM_NO_SILK")
      (libsource (lib "eagle-import") (part "M01PTH_SMD_3.25X0.85MM_NO_SILK"))
    )
    (comp (ref "JP1209")
      (value "M01PTH_SMD_3.25X0.85MM_NO_SILK")
      (footprint "eagle-import:1X01_SMD_3.25X0.85MM_NO_SILK")
      (libsource (lib "eagle-import") (part "M01PTH_SMD_3.25X0.85MM_NO_SILK"))
    )
    (comp (ref "JP1210")
      (value "M01PTH_SMD_3.25X0.85MM_NO_SILK")
      (footprint "eagle-import:1X01_SMD_3.25X0.85MM_NO_SILK")
      (libsource (lib "eagle-import") (part "M01PTH_SMD_3.25X0.85MM_NO_SILK"))
    )
    (comp (ref "JP1211")
      (value "M01PTH_SMD_3.25X0.85MM_NO_SILK")
      (footprint "eagle-import:1X01_SMD_3.25X0.85MM_NO_SILK")
      (libsource (lib "eagle-import") (part "M01PTH_SMD_3.25X0.85MM_NO_SILK"))
    )
    (comp (ref "JP1212")
      (value "M01PTH_SMD_3.25X0.85MM_NO_SILK")
      (footprint "eagle-import:1X01_SMD_3.25X0.85MM_NO_SILK")
      (libsource (lib "eagle-import") (part "M01PTH_SMD_3.25X0.85MM_NO_SILK"))
    )
    (comp (ref "JP1213")
      (value "M01PTH_SMD_3.25X0.85MM_NO_SILK")
      (footprint "eagle-import:1X01_SMD_3.25X0.85MM_NO_SILK")
      (libsource (lib "eagle-import") (part "M01PTH_SMD_3.25X0.85MM_NO_SILK"))
    )
    (comp (ref "JP1214")
      (value "M01PTH_SMD_3.25X0.85MM_NO_SILK")
      (footprint "eagle-import:1X01_SMD_3.25X0.85MM_NO_SILK")
      (libsource (lib "eagle-import") (part "M01PTH_SMD_3.25X0.85MM_NO_SILK"))
    )
    (comp (ref "JP1215")
      (value "M01PTH_SMD_3.25X0.85MM_NO_SILK")
      (footprint "eagle-import:1X01_SMD_3.25X0.85MM_NO_SILK")
      (libsource (lib "eagle-import") (part "M01PTH_SMD_3.25X0.85MM_NO_SILK"))
    )
    (comp (ref "JP1216")
      (value "M01PTH_SMD_3.25X0.85MM_NO_SILK")
      (footprint "eagle-import:1X01_SMD_3.25X0.85MM_NO_SILK")
      (libsource (lib "eagle-import") (part "M01PTH_SMD_3.25X0.85MM_NO_SILK"))
    )
    (comp (ref "JP1217")
      (value "M01PTH_SMD_3.25X0.85MM_NO_SILK")
      (footprint "eagle-import:1X01_SMD_3.25X0.85MM_NO_SILK")
      (libsource (lib "eagle-import") (part "M01PTH_SMD_3.25X0.85MM_NO_SILK"))
    )
    (comp (ref "JP1218")
      (value "M01PTH_SMD_3.25X0.85MM_NO_SILK")
      (footprint "eagle-import:1X01_SMD_3.25X0.85MM_NO_SILK")
      (libsource (lib "eagle-import") (part "M01PTH_SMD_3.25X0.85MM_NO_SILK"))
    )
    (comp (ref "JP1219")
      (value "M01PTH_SMD_3.25X0.85MM_NO_SILK")
      (footprint "eagle-import:1X01_SMD_3.25X0.85MM_NO_SILK")
      (libsource (lib "eagle-import") (part "M01PTH_SMD_3.25X0.85MM_NO_SILK"))
    )
    (comp (ref "JP1220")
      (value "M01PTH_SMD_3.25X0.85MM_NO_SILK")
      (footprint "eagle-import:1X01_SMD_3.25X0.85MM_NO_SILK")
      (libsource (lib "eagle-import") (part "M01PTH_SMD_3.25X0.85MM_NO_SILK"))
    )
    (comp (ref "JP1221")
      (value "M01PTH_SMD_3.25X0.85MM_NO_SILK")
      (footprint "eagle-import:1X01_SMD_3.25X0.85MM_NO_SILK")
      (libsource (lib "eagle-import") (part "M01PTH_SMD_3.25X0.85MM_NO_SILK"))
    )
    (comp (ref "JP1222")
      (value "M01PTH_SMD_3.25X0.85MM_NO_SILK")
      (footprint "eagle-import:1X01_SMD_3.25X0.85MM_NO_SILK")
      (libsource (lib "eagle-import") (part "M01PTH_SMD_3.25X0.85MM_NO_SILK"))
    )
    (comp (ref "JP1223")
      (value "M01PTH_SMD_3.25X0.85MM_NO_SILK")
      (footprint "eagle-import:1X01_SMD_3.25X0.85MM_NO_SILK")
      (libsource (lib "eagle-import") (part "M01PTH_SMD_3.25X0.85MM_NO_SILK"))
    )
    (comp (ref "JP1224")
      (value "M01PTH_SMD_3.25X0.85MM_NO_SILK")
      (footprint "eagle-import:1X01_SMD_3.25X0.85MM_NO_SILK")
      (libsource (lib "eagle-import") (part "M01PTH_SMD_3.25X0.85MM_NO_SILK"))
    )
    (comp (ref "JP1225")
      (value "M01PTH_SMD_3.25X0.85MM_NO_SILK")
      (footprint "eagle-import:1X01_SMD_3.25X0.85MM_NO_SILK")
      (libsource (lib "eagle-import") (part "M01PTH_SMD_3.25X0.85MM_NO_SILK"))
    )
    (comp (ref "JP1226")
      (value "M01PTH_SMD_3.25X0.85MM_NO_SILK")
      (footprint "eagle-import:1X01_SMD_3.25X0.85MM_NO_SILK")
      (libsource (lib "eagle-import") (part "M01PTH_SMD_3.25X0.85MM_NO_SILK"))
    )
    (comp (ref "JP1227")
      (value "M01PTH_SMD_3.25X0.85MM_NO_SILK")
      (footprint "eagle-import:1X01_SMD_3.25X0.85MM_NO_SILK")
      (libsource (lib "eagle-import") (part "M01PTH_SMD_3.25X0.85MM_NO_SILK"))
    )
    (comp (ref "JP1228")
      (value "M01PTH_SMD_3.25X0.85MM_NO_SILK")
      (footprint "eagle-import:1X01_SMD_3.25X0.85MM_NO_SILK")
      (libsource (lib "eagle-import") (part "M01PTH_SMD_3.25X0.85MM_NO_SILK"))
    )
    (comp (ref "JP1229")
      (value "M01PTH_SMD_3.25X0.85MM_NO_SILK")
      (footprint "eagle-import:1X01_SMD_3.25X0.85MM_NO_SILK")
      (libsource (lib "eagle-import") (part "M01PTH_SMD_3.25X0.85MM_NO_SILK"))
    )
    (comp (ref "JP1230")
      (value "M01PTH_SMD_3.25X0.85MM_NO_SILK")
      (footprint "eagle-import:1X01_SMD_3.25X0.85MM_NO_SILK")
      (libsource (lib "eagle-import") (part "M01PTH_SMD_3.25X0.85MM_NO_SILK"))
    )
    (comp (ref "JP1231")
      (value "M01PTH_SMD_3.25X0.85MM_NO_SILK")
      (footprint "eagle-import:1X01_SMD_3.25X0.85MM_NO_SILK")
      (libsource (lib "eagle-import") (part "M01PTH_SMD_3.25X0.85MM_NO_SILK"))
    )
    (comp (ref "JP1232")
      (value "M01PTH_SMD_3.25X0.85MM_NO_SILK")
      (footprint "eagle-import:1X01_SMD_3.25X0.85MM_NO_SILK")
      (libsource (lib "eagle-import") (part "M01PTH_SMD_3.25X0.85MM_NO_SILK"))
    )
    (comp (ref "JP1233")
      (value "M01PTH_SMD_3.25X0.85MM_NO_SILK")
      (footprint "eagle-import:1X01_SMD_3.25X0.85MM_NO_SILK")
      (libsource (lib "eagle-import") (part "M01PTH_SMD_3.25X0.85MM_NO_SILK"))
    )
    (comp (ref "JP1234")
      (value "M01PTH_SMD_3.25X0.85MM_NO_SILK")
      (footprint "eagle-import:1X01_SMD_3.25X0.85MM_NO_SILK")
      (libsource (lib "eagle-import") (part "M01PTH_SMD_3.25X0.85MM_NO_SILK"))
    )
    (comp (ref "JP1235")
      (value "M01PTH_SMD_3.25X0.85MM_NO_SILK")
      (footprint "eagle-import:1X01_SMD_3.25X0.85MM_NO_SILK")
      (libsource (lib "eagle-import") (part "M01PTH_SMD_3.25X0.85MM_NO_SILK"))
    )
    (comp (ref "JP1236")
      (value "M01PTH_SMD_3.25X0.85MM_NO_SILK")
      (footprint "eagle-import:1X01_SMD_3.25X0.85MM_NO_SILK")
      (libsource (lib "eagle-import") (part "M01PTH_SMD_3.25X0.85MM_NO_SILK"))
    )
    (comp (ref "JP1237")
      (value "M01PTH_SMD_3.25X0.85MM_NO_SILK")
      (footprint "eagle-import:1X01_SMD_3.25X0.85MM_NO_SILK")
      (libsource (lib "eagle-import") (part "M01PTH_SMD_3.25X0.85MM_NO_SILK"))
    )
    (comp (ref "JP1238")
      (value "M01PTH_SMD_3.25X0.85MM_NO_SILK")
      (footprint "eagle-import:1X01_SMD_3.25X0.85MM_NO_SILK")
      (libsource (lib "eagle-import") (part "M01PTH_SMD_3.25X0.85MM_NO_SILK"))
    )
    (comp (ref "JP1239")
      (value "M01PTH_SMD_3.25X0.85MM_NO_SILK")
      (footprint "eagle-import:1X01_SMD_3.25X0.85MM_NO_SILK")
      (libsource (lib "eagle-import") (part "M01PTH_SMD_3.25X0.85MM_NO_SILK"))
    )
    (comp (ref "JP1240")
      (value "M01PTH_SMD_3.25X0.85MM_NO_SILK")
      (footprint "eagle-import:1X01_SMD_3.25X0.85MM_NO_SILK")
      (libsource (lib "eagle-import") (part "M01PTH_SMD_3.25X0.85MM_NO_SILK"))
    )
    (comp (ref "JP1241")
      (value "M01PTH_SMD_3.25X0.85MM_NO_SILK")
      (footprint "eagle-import:1X01_SMD_3.25X0.85MM_NO_SILK")
      (libsource (lib "eagle-import") (part "M01PTH_SMD_3.25X0.85MM_NO_SILK"))
    )
    (comp (ref "JP1242")
      (value "M01PTH_SMD_3.25X0.85MM_NO_SILK")
      (footprint "eagle-import:1X01_SMD_3.25X0.85MM_NO_SILK")
      (libsource (lib "eagle-import") (part "M01PTH_SMD_3.25X0.85MM_NO_SILK"))
    )
    (comp (ref "JP1243")
      (value "M01PTH_SMD_3.25X0.85MM_NO_SILK")
      (footprint "eagle-import:1X01_SMD_3.25X0.85MM_NO_SILK")
      (libsource (lib "eagle-import") (part "M01PTH_SMD_3.25X0.85MM_NO_SILK"))
    )
    (comp (ref "JP1244")
      (value "M01PTH_SMD_3.25X0.85MM_NO_SILK")
      (footprint "eagle-import:1X01_SMD_3.25X0.85MM_NO_SILK")
      (libsource (lib "eagle-import") (part "M01PTH_SMD_3.25X0.85MM_NO_SILK"))
    )
    (comp (ref "JP1245")
      (value "M01PTH_SMD_3.25X0.85MM_NO_SILK")
      (footprint "eagle-import:1X01_SMD_3.25X0.85MM_NO_SILK")
      (libsource (lib "eagle-import") (part "M01PTH_SMD_3.25X0.85MM_NO_SILK"))
    )
    (comp (ref "JP1246")
      (value "M01PTH_SMD_3.25X0.85MM_NO_SILK")
      (footprint "eagle-import:1X01_SMD_3.25X0.85MM_NO_SILK")
      (libsource (lib "eagle-import") (part "M01PTH_SMD_3.25X0.85MM_NO_SILK"))
    )
    (comp (ref "JP1247")
      (value "M01PTH_SMD_3.25X0.85MM_NO_SILK")
      (footprint "eagle-import:1X01_SMD_3.25X0.85MM_NO_SILK")
      (libsource (lib "eagle-import") (part "M01PTH_SMD_3.25X0.85MM_NO_SILK"))
    )
    (comp (ref "JP1248")
      (value "M01PTH_SMD_3.25X0.85MM_NO_SILK")
      (footprint "eagle-import:1X01_SMD_3.25X0.85MM_NO_SILK")
      (libsource (lib "eagle-import") (part "M01PTH_SMD_3.25X0.85MM_NO_SILK"))
    )
    (comp (ref "JP1249")
      (value "M01PTH_SMD_3.25X0.85MM_NO_SILK")
      (footprint "eagle-import:1X01_SMD_3.25X0.85MM_NO_SILK")
      (libsource (lib "eagle-import") (part "M01PTH_SMD_3.25X0.85MM_NO_SILK"))
    )
    (comp (ref "JP1250")
      (value "M01PTH_SMD_3.25X0.85MM_NO_SILK")
      (footprint "eagle-import:1X01_SMD_3.25X0.85MM_NO_SILK")
      (libsource (lib "eagle-import") (part "M01PTH_SMD_3.25X0.85MM_NO_SILK"))
    )
    (comp (ref "JP1251")
      (value "M01PTH_SMD_3.25X0.85MM_NO_SILK")
      (footprint "eagle-import:1X01_SMD_3.25X0.85MM_NO_SILK")
      (libsource (lib "eagle-import") (part "M01PTH_SMD_3.25X0.85MM_NO_SILK"))
    )
    (comp (ref "JP1252")
      (value "M01PTH_SMD_3.25X0.85MM_NO_SILK")
      (footprint "eagle-import:1X01_SMD_3.25X0.85MM_NO_SILK")
      (libsource (lib "eagle-import") (part "M01PTH_SMD_3.25X0.85MM_NO_SILK"))
    )
    (comp (ref "JP1253")
      (value "M01PTH_SMD_3.25X0.85MM_NO_SILK")
      (footprint "eagle-import:1X01_SMD_3.25X0.85MM_NO_SILK")
      (libsource (lib "eagle-import") (part "M01PTH_SMD_3.25X0.85MM_NO_SILK"))
    )
    (comp (ref "JP1254")
      (value "M01PTH_SMD_3.25X0.85MM_NO_SILK")
      (footprint "eagle-import:1X01_SMD_3.25X0.85MM_NO_SILK")
      (libsource (lib "eagle-import") (part "M01PTH_SMD_3.25X0.85MM_NO_SILK"))
    )
    (comp (ref "JP1255")
      (value "M01PTH_SMD_3.25X0.85MM_NO_SILK")
      (footprint "eagle-import:1X01_SMD_3.25X0.85MM_NO_SILK")
      (libsource (lib "eagle-import") (part "M01PTH_SMD_3.25X0.85MM_NO_SILK"))
    )
    (comp (ref "JP1256")
      (value "M01PTH_SMD_3.25X0.85MM_NO_SILK")
      (footprint "eagle-import:1X01_SMD_3.25X0.85MM_NO_SILK")
      (libsource (lib "eagle-import") (part "M01PTH_SMD_3.25X0.85MM_NO_SILK"))
    )
    (comp (ref "JP1257")
      (value "M01PTH_SMD_3.25X0.85MM_NO_SILK")
      (footprint "eagle-import:1X01_SMD_3.25X0.85MM_NO_SILK")
      (libsource (lib "eagle-import") (part "M01PTH_SMD_3.25X0.85MM_NO_SILK"))
    )
    (comp (ref "JP1258")
      (value "M01PTH_SMD_3.25X0.85MM_NO_SILK")
      (footprint "eagle-import:1X01_SMD_3.25X0.85MM_NO_SILK")
      (libsource (lib "eagle-import") (part "M01PTH_SMD_3.25X0.85MM_NO_SILK"))
    )
    (comp (ref "JP1259")
      (value "M01PTH_SMD_3.25X0.85MM_NO_SILK")
      (footprint "eagle-import:1X01_SMD_3.25X0.85MM_NO_SILK")
      (libsource (lib "eagle-import") (part "M01PTH_SMD_3.25X0.85MM_NO_SILK"))
    )
    (comp (ref "JP1260")
      (value "M01PTH_SMD_3.25X0.85MM_NO_SILK")
      (footprint "eagle-import:1X01_SMD_3.25X0.85MM_NO_SILK")
      (libsource (lib "eagle-import") (part "M01PTH_SMD_3.25X0.85MM_NO_SILK"))
    )
    (comp (ref "JP1261")
      (value "M01PTH_SMD_3.25X0.85MM_NO_SILK")
      (footprint "eagle-import:1X01_SMD_3.25X0.85MM_NO_SILK")
      (libsource (lib "eagle-import") (part "M01PTH_SMD_3.25X0.85MM_NO_SILK"))
    )
    (comp (ref "JP1262")
      (value "M01PTH_SMD_3.25X0.85MM_NO_SILK")
      (footprint "eagle-import:1X01_SMD_3.25X0.85MM_NO_SILK")
      (libsource (lib "eagle-import") (part "M01PTH_SMD_3.25X0.85MM_NO_SILK"))
    )
    (comp (ref "JP1263")
      (value "M01PTH_SMD_3.25X0.85MM_NO_SILK")
      (footprint "eagle-import:1X01_SMD_3.25X0.85MM_NO_SILK")
      (libsource (lib "eagle-import") (part "M01PTH_SMD_3.25X0.85MM_NO_SILK"))
    )
    (comp (ref "JP1264")
      (value "M01PTH_SMD_3.25X0.85MM_NO_SILK")
      (footprint "eagle-import:1X01_SMD_3.25X0.85MM_NO_SILK")
      (libsource (lib "eagle-import") (part "M01PTH_SMD_3.25X0.85MM_NO_SILK"))
    )
    (comp (ref "JP1265")
      (value "M01PTH_SMD_3.25X0.85MM_NO_SILK")
      (footprint "eagle-import:1X01_SMD_3.25X0.85MM_NO_SILK")
      (libsource (lib "eagle-import") (part "M01PTH_SMD_3.25X0.85MM_NO_SILK"))
    )
    (comp (ref "JP1266")
      (value "M01PTH_SMD_3.25X0.85MM_NO_SILK")
      (footprint "eagle-import:1X01_SMD_3.25X0.85MM_NO_SILK")
      (libsource (lib "eagle-import") (part "M01PTH_SMD_3.25X0.85MM_NO_SILK"))
    )
    (comp (ref "JP1267")
      (value "M01PTH_SMD_3.25X0.85MM_NO_SILK")
      (footprint "eagle-import:1X01_SMD_3.25X0.85MM_NO_SILK")
      (libsource (lib "eagle-import") (part "M01PTH_SMD_3.25X0.85MM_NO_SILK"))
    )
    (comp (ref "JP1268")
      (value "M01PTH_SMD_3.25X0.85MM_NO_SILK")
      (footprint "eagle-import:1X01_SMD_3.25X0.85MM_NO_SILK")
      (libsource (lib "eagle-import") (part "M01PTH_SMD_3.25X0.85MM_NO_SILK"))
    )
    (comp (ref "JP1269")
      (value "M01PTH_SMD_3.25X0.85MM_NO_SILK")
      (footprint "eagle-import:1X01_SMD_3.25X0.85MM_NO_SILK")
      (libsource (lib "eagle-import") (part "M01PTH_SMD_3.25X0.85MM_NO_SILK"))
    )
    (comp (ref "JP1270")
      (value "M01PTH_SMD_3.25X0.85MM_NO_SILK")
      (footprint "eagle-import:1X01_SMD_3.25X0.85MM_NO_SILK")
      (libsource (lib "eagle-import") (part "M01PTH_SMD_3.25X0.85MM_NO_SILK"))
    )
    (comp (ref "JP1271")
      (value "M01PTH_SMD_3.25X0.85MM_NO_SILK")
      (footprint "eagle-import:1X01_SMD_3.25X0.85MM_NO_SILK")
      (libsource (lib "eagle-import") (part "M01PTH_SMD_3.25X0.85MM_NO_SILK"))
    )
    (comp (ref "JP1272")
      (value "M01PTH_SMD_3.25X0.85MM_NO_SILK")
      (footprint "eagle-import:1X01_SMD_3.25X0.85MM_NO_SILK")
      (libsource (lib "eagle-import") (part "M01PTH_SMD_3.25X0.85MM_NO_SILK"))
    )
    (comp (ref "JP1273")
      (value "M01PTH_SMD_3.25X0.85MM_NO_SILK")
      (footprint "eagle-import:1X01_SMD_3.25X0.85MM_NO_SILK")
      (libsource (lib "eagle-import") (part "M01PTH_SMD_3.25X0.85MM_NO_SILK"))
    )
    (comp (ref "JP1274")
      (value "M01PTH_SMD_3.25X0.85MM_NO_SILK")
      (footprint "eagle-import:1X01_SMD_3.25X0.85MM_NO_SILK")
      (libsource (lib "eagle-import") (part "M01PTH_SMD_3.25X0.85MM_NO_SILK"))
    )
    (comp (ref "JP1275")
      (value "M01PTH_SMD_3.25X0.85MM_NO_SILK")
      (footprint "eagle-import:1X01_SMD_3.25X0.85MM_NO_SILK")
      (libsource (lib "eagle-import") (part "M01PTH_SMD_3.25X0.85MM_NO_SILK"))
    )
    (comp (ref "JP1276")
      (value "M01PTH_SMD_3.25X0.85MM_NO_SILK")
      (footprint "eagle-import:1X01_SMD_3.25X0.85MM_NO_SILK")
      (libsource (lib "eagle-import") (part "M01PTH_SMD_3.25X0.85MM_NO_SILK"))
    )
    (comp (ref "JP1277")
      (value "M01PTH_SMD_3.25X0.85MM_NO_SILK")
      (footprint "eagle-import:1X01_SMD_3.25X0.85MM_NO_SILK")
      (libsource (lib "eagle-import") (part "M01PTH_SMD_3.25X0.85MM_NO_SILK"))
    )
    (comp (ref "JP1278")
      (value "M01PTH_SMD_3.25X0.85MM_NO_SILK")
      (footprint "eagle-import:1X01_SMD_3.25X0.85MM_NO_SILK")
      (libsource (lib "eagle-import") (part "M01PTH_SMD_3.25X0.85MM_NO_SILK"))
    )
    (comp (ref "JP1279")
      (value "M01PTH_SMD_3.25X0.85MM_NO_SILK")
      (footprint "eagle-import:1X01_SMD_3.25X0.85MM_NO_SILK")
      (libsource (lib "eagle-import") (part "M01PTH_SMD_3.25X0.85MM_NO_SILK"))
    )
    (comp (ref "JP1280")
      (value "M01PTH_SMD_3.25X0.85MM_NO_SILK")
      (footprint "eagle-import:1X01_SMD_3.25X0.85MM_NO_SILK")
      (libsource (lib "eagle-import") (part "M01PTH_SMD_3.25X0.85MM_NO_SILK"))
    )
    (comp (ref "JP1281")
      (value "M01PTH_SMD_3.25X0.85MM_NO_SILK")
      (footprint "eagle-import:1X01_SMD_3.25X0.85MM_NO_SILK")
      (libsource (lib "eagle-import") (part "M01PTH_SMD_3.25X0.85MM_NO_SILK"))
    )
    (comp (ref "JP1282")
      (value "M01PTH_SMD_3.25X0.85MM_NO_SILK")
      (footprint "eagle-import:1X01_SMD_3.25X0.85MM_NO_SILK")
      (libsource (lib "eagle-import") (part "M01PTH_SMD_3.25X0.85MM_NO_SILK"))
    )
    (comp (ref "JP1283")
      (value "M01PTH_SMD_3.25X0.85MM_NO_SILK")
      (footprint "eagle-import:1X01_SMD_3.25X0.85MM_NO_SILK")
      (libsource (lib "eagle-import") (part "M01PTH_SMD_3.25X0.85MM_NO_SILK"))
    )
    (comp (ref "JP1284")
      (value "M01PTH_SMD_3.25X0.85MM_NO_SILK")
      (footprint "eagle-import:1X01_SMD_3.25X0.85MM_NO_SILK")
      (libsource (lib "eagle-import") (part "M01PTH_SMD_3.25X0.85MM_NO_SILK"))
    )
    (comp (ref "JP1285")
      (value "M01PTH_SMD_3.25X0.85MM_NO_SILK")
      (footprint "eagle-import:1X01_SMD_3.25X0.85MM_NO_SILK")
      (libsource (lib "eagle-import") (part "M01PTH_SMD_3.25X0.85MM_NO_SILK"))
    )
    (comp (ref "JP1286")
      (value "M01PTH_SMD_3.25X0.85MM_NO_SILK")
      (footprint "eagle-import:1X01_SMD_3.25X0.85MM_NO_SILK")
      (libsource (lib "eagle-import") (part "M01PTH_SMD_3.25X0.85MM_NO_SILK"))
    )
    (comp (ref "JP1287")
      (value "M01PTH_SMD_3.25X0.85MM_NO_SILK")
      (footprint "eagle-import:1X01_SMD_3.25X0.85MM_NO_SILK")
      (libsource (lib "eagle-import") (part "M01PTH_SMD_3.25X0.85MM_NO_SILK"))
    )
    (comp (ref "JP1288")
      (value "M01PTH_SMD_3.25X0.85MM_NO_SILK")
      (footprint "eagle-import:1X01_SMD_3.25X0.85MM_NO_SILK")
      (libsource (lib "eagle-import") (part "M01PTH_SMD_3.25X0.85MM_NO_SILK"))
    )
    (comp (ref "JP1289")
      (value "M01PTH_SMD_3.25X0.85MM_NO_SILK")
      (footprint "eagle-import:1X01_SMD_3.25X0.85MM_NO_SILK")
      (libsource (lib "eagle-import") (part "M01PTH_SMD_3.25X0.85MM_NO_SILK"))
    )
    (comp (ref "JP1290")
      (value "M01PTH_SMD_3.25X0.85MM_NO_SILK")
      (footprint "eagle-import:1X01_SMD_3.25X0.85MM_NO_SILK")
      (libsource (lib "eagle-import") (part "M01PTH_SMD_3.25X0.85MM_NO_SILK"))
    )
    (comp (ref "JP1291")
      (value "M01PTH_SMD_3.25X0.85MM_NO_SILK")
      (footprint "eagle-import:1X01_SMD_3.25X0.85MM_NO_SILK")
      (libsource (lib "eagle-import") (part "M01PTH_SMD_3.25X0.85MM_NO_SILK"))
    )
    (comp (ref "JP1292")
      (value "M01PTH_SMD_3.25X0.85MM_NO_SILK")
      (footprint "eagle-import:1X01_SMD_3.25X0.85MM_NO_SILK")
      (libsource (lib "eagle-import") (part "M01PTH_SMD_3.25X0.85MM_NO_SILK"))
    )
    (comp (ref "JP1293")
      (value "M01PTH_SMD_3.25X0.85MM_NO_SILK")
      (footprint "eagle-import:1X01_SMD_3.25X0.85MM_NO_SILK")
      (libsource (lib "eagle-import") (part "M01PTH_SMD_3.25X0.85MM_NO_SILK"))
    )
    (comp (ref "JP1294")
      (value "M01PTH_SMD_3.25X0.85MM_NO_SILK")
      (footprint "eagle-import:1X01_SMD_3.25X0.85MM_NO_SILK")
      (libsource (lib "eagle-import") (part "M01PTH_SMD_3.25X0.85MM_NO_SILK"))
    )
    (comp (ref "JP1295")
      (value "M01PTH_SMD_3.25X0.85MM_NO_SILK")
      (footprint "eagle-import:1X01_SMD_3.25X0.85MM_NO_SILK")
      (libsource (lib "eagle-import") (part "M01PTH_SMD_3.25X0.85MM_NO_SILK"))
    )
    (comp (ref "JP1296")
      (value "M01PTH_SMD_3.25X0.85MM_NO_SILK")
      (footprint "eagle-import:1X01_SMD_3.25X0.85MM_NO_SILK")
      (libsource (lib "eagle-import") (part "M01PTH_SMD_3.25X0.85MM_NO_SILK"))
    )
    (comp (ref "JP1297")
      (value "M01PTH_SMD_3.25X0.85MM_NO_SILK")
      (footprint "eagle-import:1X01_SMD_3.25X0.85MM_NO_SILK")
      (libsource (lib "eagle-import") (part "M01PTH_SMD_3.25X0.85MM_NO_SILK"))
    )
    (comp (ref "JP1298")
      (value "M01PTH_SMD_3.25X0.85MM_NO_SILK")
      (footprint "eagle-import:1X01_SMD_3.25X0.85MM_NO_SILK")
      (libsource (lib "eagle-import") (part "M01PTH_SMD_3.25X0.85MM_NO_SILK"))
    )
    (comp (ref "JP1299")
      (value "M01PTH_SMD_3.25X0.85MM_NO_SILK")
      (footprint "eagle-import:1X01_SMD_3.25X0.85MM_NO_SILK")
      (libsource (lib "eagle-import") (part "M01PTH_SMD_3.25X0.85MM_NO_SILK"))
    )
    (comp (ref "JP1300")
      (value "M01PTH_SMD_3.25X0.85MM_NO_SILK")
      (footprint "eagle-import:1X01_SMD_3.25X0.85MM_NO_SILK")
      (libsource (lib "eagle-import") (part "M01PTH_SMD_3.25X0.85MM_NO_SILK"))
    )
    (comp (ref "JP1301")
      (value "M01PTH_SMD_3.25X0.85MM_NO_SILK")
      (footprint "eagle-import:1X01_SMD_3.25X0.85MM_NO_SILK")
      (libsource (lib "eagle-import") (part "M01PTH_SMD_3.25X0.85MM_NO_SILK"))
    )
    (comp (ref "JP1302")
      (value "M01PTH_SMD_3.25X0.85MM_NO_SILK")
      (footprint "eagle-import:1X01_SMD_3.25X0.85MM_NO_SILK")
      (libsource (lib "eagle-import") (part "M01PTH_SMD_3.25X0.85MM_NO_SILK"))
    )
    (comp (ref "JP1303")
      (value "M01PTH_SMD_3.25X0.85MM_NO_SILK")
      (footprint "eagle-import:1X01_SMD_3.25X0.85MM_NO_SILK")
      (libsource (lib "eagle-import") (part "M01PTH_SMD_3.25X0.85MM_NO_SILK"))
    )
    (comp (ref "JP1304")
      (value "M01PTH_SMD_3.25X0.85MM_NO_SILK")
      (footprint "eagle-import:1X01_SMD_3.25X0.85MM_NO_SILK")
      (libsource (lib "eagle-import") (part "M01PTH_SMD_3.25X0.85MM_NO_SILK"))
    )
    (comp (ref "JP1305")
      (value "M01PTH_SMD_3.25X0.85MM_NO_SILK")
      (footprint "eagle-import:1X01_SMD_3.25X0.85MM_NO_SILK")
      (libsource (lib "eagle-import") (part "M01PTH_SMD_3.25X0.85MM_NO_SILK"))
    )
    (comp (ref "JP1306")
      (value "M01PTH_SMD_3.25X0.85MM_NO_SILK")
      (footprint "eagle-import:1X01_SMD_3.25X0.85MM_NO_SILK")
      (libsource (lib "eagle-import") (part "M01PTH_SMD_3.25X0.85MM_NO_SILK"))
    )
    (comp (ref "JP1307")
      (value "M01PTH_SMD_3.25X0.85MM_NO_SILK")
      (footprint "eagle-import:1X01_SMD_3.25X0.85MM_NO_SILK")
      (libsource (lib "eagle-import") (part "M01PTH_SMD_3.25X0.85MM_NO_SILK"))
    )
    (comp (ref "JP1308")
      (value "M01PTH_SMD_3.25X0.85MM_NO_SILK")
      (footprint "eagle-import:1X01_SMD_3.25X0.85MM_NO_SILK")
      (libsource (lib "eagle-import") (part "M01PTH_SMD_3.25X0.85MM_NO_SILK"))
    )
    (comp (ref "JP1309")
      (value "M01PTH_SMD_3.25X0.85MM_NO_SILK")
      (footprint "eagle-import:1X01_SMD_3.25X0.85MM_NO_SILK")
      (libsource (lib "eagle-import") (part "M01PTH_SMD_3.25X0.85MM_NO_SILK"))
    )
    (comp (ref "JP1310")
      (value "M01PTH_SMD_3.25X0.85MM_NO_SILK")
      (footprint "eagle-import:1X01_SMD_3.25X0.85MM_NO_SILK")
      (libsource (lib "eagle-import") (part "M01PTH_SMD_3.25X0.85MM_NO_SILK"))
    )
    (comp (ref "JP1311")
      (value "M01PTH_SMD_3.25X0.85MM_NO_SILK")
      (footprint "eagle-import:1X01_SMD_3.25X0.85MM_NO_SILK")
      (libsource (lib "eagle-import") (part "M01PTH_SMD_3.25X0.85MM_NO_SILK"))
    )
    (comp (ref "JP1312")
      (value "M01PTH_SMD_3.25X0.85MM_NO_SILK")
      (footprint "eagle-import:1X01_SMD_3.25X0.85MM_NO_SILK")
      (libsource (lib "eagle-import") (part "M01PTH_SMD_3.25X0.85MM_NO_SILK"))
    )
    (comp (ref "JP1313")
      (value "M01PTH_SMD_3.25X0.85MM_NO_SILK")
      (footprint "eagle-import:1X01_SMD_3.25X0.85MM_NO_SILK")
      (libsource (lib "eagle-import") (part "M01PTH_SMD_3.25X0.85MM_NO_SILK"))
    )
    (comp (ref "JP1314")
      (value "M01PTH_SMD_3.25X0.85MM_NO_SILK")
      (footprint "eagle-import:1X01_SMD_3.25X0.85MM_NO_SILK")
      (libsource (lib "eagle-import") (part "M01PTH_SMD_3.25X0.85MM_NO_SILK"))
    )
    (comp (ref "JP1315")
      (value "M01PTH_SMD_3.25X0.85MM_NO_SILK")
      (footprint "eagle-import:1X01_SMD_3.25X0.85MM_NO_SILK")
      (libsource (lib "eagle-import") (part "M01PTH_SMD_3.25X0.85MM_NO_SILK"))
    )
    (comp (ref "JP1316")
      (value "M01PTH_SMD_3.25X0.85MM_NO_SILK")
      (footprint "eagle-import:1X01_SMD_3.25X0.85MM_NO_SILK")
      (libsource (lib "eagle-import") (part "M01PTH_SMD_3.25X0.85MM_NO_SILK"))
    )
    (comp (ref "JP1317")
      (value "M01PTH_SMD_3.25X0.85MM_NO_SILK")
      (footprint "eagle-import:1X01_SMD_3.25X0.85MM_NO_SILK")
      (libsource (lib "eagle-import") (part "M01PTH_SMD_3.25X0.85MM_NO_SILK"))
    )
    (comp (ref "JP1318")
      (value "M01PTH_SMD_3.25X0.85MM_NO_SILK")
      (footprint "eagle-import:1X01_SMD_3.25X0.85MM_NO_SILK")
      (libsource (lib "eagle-import") (part "M01PTH_SMD_3.25X0.85MM_NO_SILK"))
    )
    (comp (ref "JP1319")
      (value "M01PTH_SMD_3.25X0.85MM_NO_SILK")
      (footprint "eagle-import:1X01_SMD_3.25X0.85MM_NO_SILK")
      (libsource (lib "eagle-import") (part "M01PTH_SMD_3.25X0.85MM_NO_SILK"))
    )
    (comp (ref "JP1320")
      (value "M01PTH_SMD_3.25X0.85MM_NO_SILK")
      (footprint "eagle-import:1X01_SMD_3.25X0.85MM_NO_SILK")
      (libsource (lib "eagle-import") (part "M01PTH_SMD_3.25X0.85MM_NO_SILK"))
    )
    (comp (ref "JP1321")
      (value "M01PTH_SMD_3.25X0.85MM_NO_SILK")
      (footprint "eagle-import:1X01_SMD_3.25X0.85MM_NO_SILK")
      (libsource (lib "eagle-import") (part "M01PTH_SMD_3.25X0.85MM_NO_SILK"))
    )
    (comp (ref "JP1322")
      (value "M01PTH_SMD_3.25X0.85MM_NO_SILK")
      (footprint "eagle-import:1X01_SMD_3.25X0.85MM_NO_SILK")
      (libsource (lib "eagle-import") (part "M01PTH_SMD_3.25X0.85MM_NO_SILK"))
    )
    (comp (ref "JP1323")
      (value "M01PTH_SMD_3.25X0.85MM_NO_SILK")
      (footprint "eagle-import:1X01_SMD_3.25X0.85MM_NO_SILK")
      (libsource (lib "eagle-import") (part "M01PTH_SMD_3.25X0.85MM_NO_SILK"))
    )
    (comp (ref "JP1324")
      (value "M01PTH_SMD_3.25X0.85MM_NO_SILK")
      (footprint "eagle-import:1X01_SMD_3.25X0.85MM_NO_SILK")
      (libsource (lib "eagle-import") (part "M01PTH_SMD_3.25X0.85MM_NO_SILK"))
    )
    (comp (ref "JP1325")
      (value "M01PTH_SMD_3.25X0.85MM_NO_SILK")
      (footprint "eagle-import:1X01_SMD_3.25X0.85MM_NO_SILK")
      (libsource (lib "eagle-import") (part "M01PTH_SMD_3.25X0.85MM_NO_SILK"))
    )
    (comp (ref "JP1326")
      (value "M01PTH_SMD_3.25X0.85MM_NO_SILK")
      (footprint "eagle-import:1X01_SMD_3.25X0.85MM_NO_SILK")
      (libsource (lib "eagle-import") (part "M01PTH_SMD_3.25X0.85MM_NO_SILK"))
    )
    (comp (ref "JP1327")
      (value "M01PTH_SMD_3.25X0.85MM_NO_SILK")
      (footprint "eagle-import:1X01_SMD_3.25X0.85MM_NO_SILK")
      (libsource (lib "eagle-import") (part "M01PTH_SMD_3.25X0.85MM_NO_SILK"))
    )
    (comp (ref "JP1328")
      (value "M01PTH_SMD_3.25X0.85MM_NO_SILK")
      (footprint "eagle-import:1X01_SMD_3.25X0.85MM_NO_SILK")
      (libsource (lib "eagle-import") (part "M01PTH_SMD_3.25X0.85MM_NO_SILK"))
    )
    (comp (ref "JP1329")
      (value "M01PTH_SMD_3.25X0.85MM_NO_SILK")
      (footprint "eagle-import:1X01_SMD_3.25X0.85MM_NO_SILK")
      (libsource (lib "eagle-import") (part "M01PTH_SMD_3.25X0.85MM_NO_SILK"))
    )
    (comp (ref "JP1330")
      (value "M01PTH_SMD_3.25X0.85MM_NO_SILK")
      (footprint "eagle-import:1X01_SMD_3.25X0.85MM_NO_SILK")
      (libsource (lib "eagle-import") (part "M01PTH_SMD_3.25X0.85MM_NO_SILK"))
    )
    (comp (ref "JP1331")
      (value "M01PTH_SMD_3.25X0.85MM_NO_SILK")
      (footprint "eagle-import:1X01_SMD_3.25X0.85MM_NO_SILK")
      (libsource (lib "eagle-import") (part "M01PTH_SMD_3.25X0.85MM_NO_SILK"))
    )
    (comp (ref "JP1332")
      (value "M01PTH_SMD_3.25X0.85MM_NO_SILK")
      (footprint "eagle-import:1X01_SMD_3.25X0.85MM_NO_SILK")
      (libsource (lib "eagle-import") (part "M01PTH_SMD_3.25X0.85MM_NO_SILK"))
    )
    (comp (ref "JP1333")
      (value "M01PTH_SMD_3.25X0.85MM_NO_SILK")
      (footprint "eagle-import:1X01_SMD_3.25X0.85MM_NO_SILK")
      (libsource (lib "eagle-import") (part "M01PTH_SMD_3.25X0.85MM_NO_SILK"))
    )
    (comp (ref "JP1334")
      (value "M01PTH_SMD_3.25X0.85MM_NO_SILK")
      (footprint "eagle-import:1X01_SMD_3.25X0.85MM_NO_SILK")
      (libsource (lib "eagle-import") (part "M01PTH_SMD_3.25X0.85MM_NO_SILK"))
    )
    (comp (ref "JP1335")
      (value "M01PTH_SMD_3.25X0.85MM_NO_SILK")
      (footprint "eagle-import:1X01_SMD_3.25X0.85MM_NO_SILK")
      (libsource (lib "eagle-import") (part "M01PTH_SMD_3.25X0.85MM_NO_SILK"))
    )
    (comp (ref "JP1336")
      (value "M01PTH_SMD_3.25X0.85MM_NO_SILK")
      (footprint "eagle-import:1X01_SMD_3.25X0.85MM_NO_SILK")
      (libsource (lib "eagle-import") (part "M01PTH_SMD_3.25X0.85MM_NO_SILK"))
    )
    (comp (ref "JP1337")
      (value "M01PTH_SMD_3.25X0.85MM_NO_SILK")
      (footprint "eagle-import:1X01_SMD_3.25X0.85MM_NO_SILK")
      (libsource (lib "eagle-import") (part "M01PTH_SMD_3.25X0.85MM_NO_SILK"))
    )
    (comp (ref "JP1338")
      (value "M01PTH_SMD_3.25X0.85MM_NO_SILK")
      (footprint "eagle-import:1X01_SMD_3.25X0.85MM_NO_SILK")
      (libsource (lib "eagle-import") (part "M01PTH_SMD_3.25X0.85MM_NO_SILK"))
    )
    (comp (ref "JP1339")
      (value "M01PTH_SMD_3.25X0.85MM_NO_SILK")
      (footprint "eagle-import:1X01_SMD_3.25X0.85MM_NO_SILK")
      (libsource (lib "eagle-import") (part "M01PTH_SMD_3.25X0.85MM_NO_SILK"))
    )
    (comp (ref "JP1340")
      (value "M01PTH_SMD_3.25X0.85MM_NO_SILK")
      (footprint "eagle-import:1X01_SMD_3.25X0.85MM_NO_SILK")
      (libsource (lib "eagle-import") (part "M01PTH_SMD_3.25X0.85MM_NO_SILK"))
    )
    (comp (ref "JP1341")
      (value "M01PTH_SMD_3.25X0.85MM_NO_SILK")
      (footprint "eagle-import:1X01_SMD_3.25X0.85MM_NO_SILK")
      (libsource (lib "eagle-import") (part "M01PTH_SMD_3.25X0.85MM_NO_SILK"))
    )
    (comp (ref "JP1342")
      (value "M01PTH_SMD_3.25X0.85MM_NO_SILK")
      (footprint "eagle-import:1X01_SMD_3.25X0.85MM_NO_SILK")
      (libsource (lib "eagle-import") (part "M01PTH_SMD_3.25X0.85MM_NO_SILK"))
    )
    (comp (ref "JP1343")
      (value "M01PTH_SMD_3.25X0.85MM_NO_SILK")
      (footprint "eagle-import:1X01_SMD_3.25X0.85MM_NO_SILK")
      (libsource (lib "eagle-import") (part "M01PTH_SMD_3.25X0.85MM_NO_SILK"))
    )
    (comp (ref "JP1344")
      (value "M01PTH_SMD_3.25X0.85MM_NO_SILK")
      (footprint "eagle-import:1X01_SMD_3.25X0.85MM_NO_SILK")
      (libsource (lib "eagle-import") (part "M01PTH_SMD_3.25X0.85MM_NO_SILK"))
    )
    (comp (ref "JP1345")
      (value "M01PTH_SMD_3.25X0.85MM_NO_SILK")
      (footprint "eagle-import:1X01_SMD_3.25X0.85MM_NO_SILK")
      (libsource (lib "eagle-import") (part "M01PTH_SMD_3.25X0.85MM_NO_SILK"))
    )
    (comp (ref "JP1346")
      (value "M01PTH_SMD_3.25X0.85MM_NO_SILK")
      (footprint "eagle-import:1X01_SMD_3.25X0.85MM_NO_SILK")
      (libsource (lib "eagle-import") (part "M01PTH_SMD_3.25X0.85MM_NO_SILK"))
    )
    (comp (ref "JP1347")
      (value "M01PTH_SMD_3.25X0.85MM_NO_SILK")
      (footprint "eagle-import:1X01_SMD_3.25X0.85MM_NO_SILK")
      (libsource (lib "eagle-import") (part "M01PTH_SMD_3.25X0.85MM_NO_SILK"))
    )
    (comp (ref "JP1348")
      (value "M01PTH_SMD_3.25X0.85MM_NO_SILK")
      (footprint "eagle-import:1X01_SMD_3.25X0.85MM_NO_SILK")
      (libsource (lib "eagle-import") (part "M01PTH_SMD_3.25X0.85MM_NO_SILK"))
    )
    (comp (ref "JP1349")
      (value "M01PTH_SMD_3.25X0.85MM_NO_SILK")
      (footprint "eagle-import:1X01_SMD_3.25X0.85MM_NO_SILK")
      (libsource (lib "eagle-import") (part "M01PTH_SMD_3.25X0.85MM_NO_SILK"))
    )
    (comp (ref "JP1350")
      (value "M01PTH_SMD_3.25X0.85MM_NO_SILK")
      (footprint "eagle-import:1X01_SMD_3.25X0.85MM_NO_SILK")
      (libsource (lib "eagle-import") (part "M01PTH_SMD_3.25X0.85MM_NO_SILK"))
    )
    (comp (ref "JP1351")
      (value "M01PTH_SMD_3.25X0.85MM_NO_SILK")
      (footprint "eagle-import:1X01_SMD_3.25X0.85MM_NO_SILK")
      (libsource (lib "eagle-import") (part "M01PTH_SMD_3.25X0.85MM_NO_SILK"))
    )
    (comp (ref "JP1352")
      (value "M01PTH_SMD_3.25X0.85MM_NO_SILK")
      (footprint "eagle-import:1X01_SMD_3.25X0.85MM_NO_SILK")
      (libsource (lib "eagle-import") (part "M01PTH_SMD_3.25X0.85MM_NO_SILK"))
    )
    (comp (ref "JP1353")
      (value "M01PTH_SMD_3.25X0.85MM_NO_SILK")
      (footprint "eagle-import:1X01_SMD_3.25X0.85MM_NO_SILK")
      (libsource (lib "eagle-import") (part "M01PTH_SMD_3.25X0.85MM_NO_SILK"))
    )
    (comp (ref "JP1354")
      (value "M01PTH_SMD_3.25X0.85MM_NO_SILK")
      (footprint "eagle-import:1X01_SMD_3.25X0.85MM_NO_SILK")
      (libsource (lib "eagle-import") (part "M01PTH_SMD_3.25X0.85MM_NO_SILK"))
    )
    (comp (ref "JP1355")
      (value "M01PTH_SMD_3.25X0.85MM_NO_SILK")
      (footprint "eagle-import:1X01_SMD_3.25X0.85MM_NO_SILK")
      (libsource (lib "eagle-import") (part "M01PTH_SMD_3.25X0.85MM_NO_SILK"))
    )
    (comp (ref "JP1356")
      (value "M01PTH_SMD_3.25X0.85MM_NO_SILK")
      (footprint "eagle-import:1X01_SMD_3.25X0.85MM_NO_SILK")
      (libsource (lib "eagle-import") (part "M01PTH_SMD_3.25X0.85MM_NO_SILK"))
    )
    (comp (ref "JP1357")
      (value "M01PTH_SMD_3.25X0.85MM_NO_SILK")
      (footprint "eagle-import:1X01_SMD_3.25X0.85MM_NO_SILK")
      (libsource (lib "eagle-import") (part "M01PTH_SMD_3.25X0.85MM_NO_SILK"))
    )
    (comp (ref "JP1358")
      (value "M01PTH_SMD_3.25X0.85MM_NO_SILK")
      (footprint "eagle-import:1X01_SMD_3.25X0.85MM_NO_SILK")
      (libsource (lib "eagle-import") (part "M01PTH_SMD_3.25X0.85MM_NO_SILK"))
    )
    (comp (ref "JP1359")
      (value "M01PTH_SMD_3.25X0.85MM_NO_SILK")
      (footprint "eagle-import:1X01_SMD_3.25X0.85MM_NO_SILK")
      (libsource (lib "eagle-import") (part "M01PTH_SMD_3.25X0.85MM_NO_SILK"))
    )
    (comp (ref "JP1360")
      (value "M01PTH_SMD_3.25X0.85MM_NO_SILK")
      (footprint "eagle-import:1X01_SMD_3.25X0.85MM_NO_SILK")
      (libsource (lib "eagle-import") (part "M01PTH_SMD_3.25X0.85MM_NO_SILK"))
    )
    (comp (ref "JP1361")
      (value "M01PTH_SMD_3.25X0.85MM_NO_SILK")
      (footprint "eagle-import:1X01_SMD_3.25X0.85MM_NO_SILK")
      (libsource (lib "eagle-import") (part "M01PTH_SMD_3.25X0.85MM_NO_SILK"))
    )
    (comp (ref "JP1362")
      (value "M01PTH_SMD_3.25X0.85MM_NO_SILK")
      (footprint "eagle-import:1X01_SMD_3.25X0.85MM_NO_SILK")
      (libsource (lib "eagle-import") (part "M01PTH_SMD_3.25X0.85MM_NO_SILK"))
    )
    (comp (ref "JP1363")
      (value "M01PTH_SMD_3.25X0.85MM_NO_SILK")
      (footprint "eagle-import:1X01_SMD_3.25X0.85MM_NO_SILK")
      (libsource (lib "eagle-import") (part "M01PTH_SMD_3.25X0.85MM_NO_SILK"))
    )
    (comp (ref "JP1364")
      (value "M01PTH_SMD_3.25X0.85MM_NO_SILK")
      (footprint "eagle-import:1X01_SMD_3.25X0.85MM_NO_SILK")
      (libsource (lib "eagle-import") (part "M01PTH_SMD_3.25X0.85MM_NO_SILK"))
    )
    (comp (ref "JP1365")
      (value "M01PTH_SMD_3.25X0.85MM_NO_SILK")
      (footprint "eagle-import:1X01_SMD_3.25X0.85MM_NO_SILK")
      (libsource (lib "eagle-import") (part "M01PTH_SMD_3.25X0.85MM_NO_SILK"))
    )
    (comp (ref "JP1366")
      (value "M01PTH_SMD_3.25X0.85MM_NO_SILK")
      (footprint "eagle-import:1X01_SMD_3.25X0.85MM_NO_SILK")
      (libsource (lib "eagle-import") (part "M01PTH_SMD_3.25X0.85MM_NO_SILK"))
    )
    (comp (ref "JP1367")
      (value "M01PTH_SMD_3.25X0.85MM_NO_SILK")
      (footprint "eagle-import:1X01_SMD_3.25X0.85MM_NO_SILK")
      (libsource (lib "eagle-import") (part "M01PTH_SMD_3.25X0.85MM_NO_SILK"))
    )
    (comp (ref "JP1368")
      (value "M01PTH_SMD_3.25X0.85MM_NO_SILK")
      (footprint "eagle-import:1X01_SMD_3.25X0.85MM_NO_SILK")
      (libsource (lib "eagle-import") (part "M01PTH_SMD_3.25X0.85MM_NO_SILK"))
    )
    (comp (ref "JP1369")
      (value "M01PTH_SMD_3.25X0.85MM_NO_SILK")
      (footprint "eagle-import:1X01_SMD_3.25X0.85MM_NO_SILK")
      (libsource (lib "eagle-import") (part "M01PTH_SMD_3.25X0.85MM_NO_SILK"))
    )
    (comp (ref "JP1370")
      (value "M01PTH_SMD_3.25X0.85MM_NO_SILK")
      (footprint "eagle-import:1X01_SMD_3.25X0.85MM_NO_SILK")
      (libsource (lib "eagle-import") (part "M01PTH_SMD_3.25X0.85MM_NO_SILK"))
    )
    (comp (ref "JP1371")
      (value "M01PTH_SMD_3.25X0.85MM_NO_SILK")
      (footprint "eagle-import:1X01_SMD_3.25X0.85MM_NO_SILK")
      (libsource (lib "eagle-import") (part "M01PTH_SMD_3.25X0.85MM_NO_SILK"))
    )
    (comp (ref "JP1372")
      (value "M01PTH_SMD_3.25X0.85MM_NO_SILK")
      (footprint "eagle-import:1X01_SMD_3.25X0.85MM_NO_SILK")
      (libsource (lib "eagle-import") (part "M01PTH_SMD_3.25X0.85MM_NO_SILK"))
    )
    (comp (ref "JP1373")
      (value "M01PTH_SMD_3.25X0.85MM_NO_SILK")
      (footprint "eagle-import:1X01_SMD_3.25X0.85MM_NO_SILK")
      (libsource (lib "eagle-import") (part "M01PTH_SMD_3.25X0.85MM_NO_SILK"))
    )
    (comp (ref "JP1374")
      (value "M01PTH_SMD_3.25X0.85MM_NO_SILK")
      (footprint "eagle-import:1X01_SMD_3.25X0.85MM_NO_SILK")
      (libsource (lib "eagle-import") (part "M01PTH_SMD_3.25X0.85MM_NO_SILK"))
    )
    (comp (ref "JP1375")
      (value "M01PTH_SMD_3.25X0.85MM_NO_SILK")
      (footprint "eagle-import:1X01_SMD_3.25X0.85MM_NO_SILK")
      (libsource (lib "eagle-import") (part "M01PTH_SMD_3.25X0.85MM_NO_SILK"))
    )
    (comp (ref "JP1376")
      (value "M01PTH_SMD_3.25X0.85MM_NO_SILK")
      (footprint "eagle-import:1X01_SMD_3.25X0.85MM_NO_SILK")
      (libsource (lib "eagle-import") (part "M01PTH_SMD_3.25X0.85MM_NO_SILK"))
    )
    (comp (ref "JP1377")
      (value "M01PTH_SMD_3.25X0.85MM_NO_SILK")
      (footprint "eagle-import:1X01_SMD_3.25X0.85MM_NO_SILK")
      (libsource (lib "eagle-import") (part "M01PTH_SMD_3.25X0.85MM_NO_SILK"))
    )
    (comp (ref "JP1378")
      (value "M01PTH_SMD_3.25X0.85MM_NO_SILK")
      (footprint "eagle-import:1X01_SMD_3.25X0.85MM_NO_SILK")
      (libsource (lib "eagle-import") (part "M01PTH_SMD_3.25X0.85MM_NO_SILK"))
    )
    (comp (ref "JP1379")
      (value "M01PTH_SMD_3.25X0.85MM_NO_SILK")
      (footprint "eagle-import:1X01_SMD_3.25X0.85MM_NO_SILK")
      (libsource (lib "eagle-import") (part "M01PTH_SMD_3.25X0.85MM_NO_SILK"))
    )
    (comp (ref "JP1380")
      (value "M01PTH_SMD_3.25X0.85MM_NO_SILK")
      (footprint "eagle-import:1X01_SMD_3.25X0.85MM_NO_SILK")
      (libsource (lib "eagle-import") (part "M01PTH_SMD_3.25X0.85MM_NO_SILK"))
    )
    (comp (ref "JP1381")
      (value "M01PTH_SMD_3.25X0.85MM_NO_SILK")
      (footprint "eagle-import:1X01_SMD_3.25X0.85MM_NO_SILK")
      (libsource (lib "eagle-import") (part "M01PTH_SMD_3.25X0.85MM_NO_SILK"))
    )
    (comp (ref "JP1382")
      (value "M01PTH_SMD_3.25X0.85MM_NO_SILK")
      (footprint "eagle-import:1X01_SMD_3.25X0.85MM_NO_SILK")
      (libsource (lib "eagle-import") (part "M01PTH_SMD_3.25X0.85MM_NO_SILK"))
    )
    (comp (ref "JP1383")
      (value "M01PTH_SMD_3.25X0.85MM_NO_SILK")
      (footprint "eagle-import:1X01_SMD_3.25X0.85MM_NO_SILK")
      (libsource (lib "eagle-import") (part "M01PTH_SMD_3.25X0.85MM_NO_SILK"))
    )
    (comp (ref "JP1384")
      (value "M01PTH_SMD_3.25X0.85MM_NO_SILK")
      (footprint "eagle-import:1X01_SMD_3.25X0.85MM_NO_SILK")
      (libsource (lib "eagle-import") (part "M01PTH_SMD_3.25X0.85MM_NO_SILK"))
    )
    (comp (ref "JP1385")
      (value "M01PTH_SMD_3.25X0.85MM_NO_SILK")
      (footprint "eagle-import:1X01_SMD_3.25X0.85MM_NO_SILK")
      (libsource (lib "eagle-import") (part "M01PTH_SMD_3.25X0.85MM_NO_SILK"))
    )
    (comp (ref "JP1386")
      (value "M01PTH_SMD_3.25X0.85MM_NO_SILK")
      (footprint "eagle-import:1X01_SMD_3.25X0.85MM_NO_SILK")
      (libsource (lib "eagle-import") (part "M01PTH_SMD_3.25X0.85MM_NO_SILK"))
    )
    (comp (ref "JP1387")
      (value "M01PTH_SMD_3.25X0.85MM_NO_SILK")
      (footprint "eagle-import:1X01_SMD_3.25X0.85MM_NO_SILK")
      (libsource (lib "eagle-import") (part "M01PTH_SMD_3.25X0.85MM_NO_SILK"))
    )
    (comp (ref "JP1388")
      (value "M01PTH_SMD_3.25X0.85MM_NO_SILK")
      (footprint "eagle-import:1X01_SMD_3.25X0.85MM_NO_SILK")
      (libsource (lib "eagle-import") (part "M01PTH_SMD_3.25X0.85MM_NO_SILK"))
    )
    (comp (ref "JP1389")
      (value "M01PTH_SMD_3.25X0.85MM_NO_SILK")
      (footprint "eagle-import:1X01_SMD_3.25X0.85MM_NO_SILK")
      (libsource (lib "eagle-import") (part "M01PTH_SMD_3.25X0.85MM_NO_SILK"))
    )
    (comp (ref "JP1390")
      (value "M01PTH_SMD_3.25X0.85MM_NO_SILK")
      (footprint "eagle-import:1X01_SMD_3.25X0.85MM_NO_SILK")
      (libsource (lib "eagle-import") (part "M01PTH_SMD_3.25X0.85MM_NO_SILK"))
    )
    (comp (ref "JP1391")
      (value "M01PTH_SMD_3.25X0.85MM_NO_SILK")
      (footprint "eagle-import:1X01_SMD_3.25X0.85MM_NO_SILK")
      (libsource (lib "eagle-import") (part "M01PTH_SMD_3.25X0.85MM_NO_SILK"))
    )
    (comp (ref "JP1392")
      (value "M01PTH_SMD_3.25X0.85MM_NO_SILK")
      (footprint "eagle-import:1X01_SMD_3.25X0.85MM_NO_SILK")
      (libsource (lib "eagle-import") (part "M01PTH_SMD_3.25X0.85MM_NO_SILK"))
    )
    (comp (ref "JP1393")
      (value "M01PTH_SMD_3.25X0.85MM_NO_SILK")
      (footprint "eagle-import:1X01_SMD_3.25X0.85MM_NO_SILK")
      (libsource (lib "eagle-import") (part "M01PTH_SMD_3.25X0.85MM_NO_SILK"))
    )
    (comp (ref "JP1394")
      (value "M01PTH_SMD_3.25X0.85MM_NO_SILK")
      (footprint "eagle-import:1X01_SMD_3.25X0.85MM_NO_SILK")
      (libsource (lib "eagle-import") (part "M01PTH_SMD_3.25X0.85MM_NO_SILK"))
    )
    (comp (ref "JP1395")
      (value "M01PTH_SMD_3.25X0.85MM_NO_SILK")
      (footprint "eagle-import:1X01_SMD_3.25X0.85MM_NO_SILK")
      (libsource (lib "eagle-import") (part "M01PTH_SMD_3.25X0.85MM_NO_SILK"))
    )
    (comp (ref "JP1396")
      (value "M01PTH_SMD_3.25X0.85MM_NO_SILK")
      (footprint "eagle-import:1X01_SMD_3.25X0.85MM_NO_SILK")
      (libsource (lib "eagle-import") (part "M01PTH_SMD_3.25X0.85MM_NO_SILK"))
    )
    (comp (ref "JP1397")
      (value "M01PTH_SMD_3.25X0.85MM_NO_SILK")
      (footprint "eagle-import:1X01_SMD_3.25X0.85MM_NO_SILK")
      (libsource (lib "eagle-import") (part "M01PTH_SMD_3.25X0.85MM_NO_SILK"))
    )
    (comp (ref "JP1398")
      (value "M01PTH_SMD_3.25X0.85MM_NO_SILK")
      (footprint "eagle-import:1X01_SMD_3.25X0.85MM_NO_SILK")
      (libsource (lib "eagle-import") (part "M01PTH_SMD_3.25X0.85MM_NO_SILK"))
    )
    (comp (ref "JP1399")
      (value "M01PTH_SMD_3.25X0.85MM_NO_SILK")
      (footprint "eagle-import:1X01_SMD_3.25X0.85MM_NO_SILK")
      (libsource (lib "eagle-import") (part "M01PTH_SMD_3.25X0.85MM_NO_SILK"))
    )
    (comp (ref "JP1400")
      (value "M01PTH_SMD_3.25X0.85MM_NO_SILK")
      (footprint "eagle-import:1X01_SMD_3.25X0.85MM_NO_SILK")
      (libsource (lib "eagle-import") (part "M01PTH_SMD_3.25X0.85MM_NO_SILK"))
    )
    (comp (ref "JP1401")
      (value "M01PTH_SMD_3.25X0.85MM_NO_SILK")
      (footprint "eagle-import:1X01_SMD_3.25X0.85MM_NO_SILK")
      (libsource (lib "eagle-import") (part "M01PTH_SMD_3.25X0.85MM_NO_SILK"))
    )
    (comp (ref "JP1402")
      (value "M01PTH_SMD_3.25X0.85MM_NO_SILK")
      (footprint "eagle-import:1X01_SMD_3.25X0.85MM_NO_SILK")
      (libsource (lib "eagle-import") (part "M01PTH_SMD_3.25X0.85MM_NO_SILK"))
    )
    (comp (ref "JP1403")
      (value "M01PTH_SMD_3.25X0.85MM_NO_SILK")
      (footprint "eagle-import:1X01_SMD_3.25X0.85MM_NO_SILK")
      (libsource (lib "eagle-import") (part "M01PTH_SMD_3.25X0.85MM_NO_SILK"))
    )
    (comp (ref "JP1404")
      (value "M01PTH_SMD_3.25X0.85MM_NO_SILK")
      (footprint "eagle-import:1X01_SMD_3.25X0.85MM_NO_SILK")
      (libsource (lib "eagle-import") (part "M01PTH_SMD_3.25X0.85MM_NO_SILK"))
    )
    (comp (ref "JP1405")
      (value "M01PTH_SMD_3.25X0.85MM_NO_SILK")
      (footprint "eagle-import:1X01_SMD_3.25X0.85MM_NO_SILK")
      (libsource (lib "eagle-import") (part "M01PTH_SMD_3.25X0.85MM_NO_SILK"))
    )
    (comp (ref "JP1406")
      (value "M01PTH_SMD_3.25X0.85MM_NO_SILK")
      (footprint "eagle-import:1X01_SMD_3.25X0.85MM_NO_SILK")
      (libsource (lib "eagle-import") (part "M01PTH_SMD_3.25X0.85MM_NO_SILK"))
    )
    (comp (ref "JP1407")
      (value "M01PTH_SMD_3.25X0.85MM_NO_SILK")
      (footprint "eagle-import:1X01_SMD_3.25X0.85MM_NO_SILK")
      (libsource (lib "eagle-import") (part "M01PTH_SMD_3.25X0.85MM_NO_SILK"))
    )
    (comp (ref "JP1408")
      (value "M01PTH_SMD_3.25X0.85MM_NO_SILK")
      (footprint "eagle-import:1X01_SMD_3.25X0.85MM_NO_SILK")
      (libsource (lib "eagle-import") (part "M01PTH_SMD_3.25X0.85MM_NO_SILK"))
    )
    (comp (ref "JP1409")
      (value "M01PTH_SMD_3.25X0.85MM_NO_SILK")
      (footprint "eagle-import:1X01_SMD_3.25X0.85MM_NO_SILK")
      (libsource (lib "eagle-import") (part "M01PTH_SMD_3.25X0.85MM_NO_SILK"))
    )
    (comp (ref "JP1410")
      (value "M01PTH_SMD_3.25X0.85MM_NO_SILK")
      (footprint "eagle-import:1X01_SMD_3.25X0.85MM_NO_SILK")
      (libsource (lib "eagle-import") (part "M01PTH_SMD_3.25X0.85MM_NO_SILK"))
    )
    (comp (ref "JP1411")
      (value "M01PTH_SMD_3.25X0.85MM_NO_SILK")
      (footprint "eagle-import:1X01_SMD_3.25X0.85MM_NO_SILK")
      (libsource (lib "eagle-import") (part "M01PTH_SMD_3.25X0.85MM_NO_SILK"))
    )
    (comp (ref "JP1412")
      (value "M01PTH_SMD_3.25X0.85MM_NO_SILK")
      (footprint "eagle-import:1X01_SMD_3.25X0.85MM_NO_SILK")
      (libsource (lib "eagle-import") (part "M01PTH_SMD_3.25X0.85MM_NO_SILK"))
    )
    (comp (ref "JP1413")
      (value "M01PTH_SMD_3.25X0.85MM_NO_SILK")
      (footprint "eagle-import:1X01_SMD_3.25X0.85MM_NO_SILK")
      (libsource (lib "eagle-import") (part "M01PTH_SMD_3.25X0.85MM_NO_SILK"))
    )
    (comp (ref "JP1414")
      (value "M01PTH_SMD_3.25X0.85MM_NO_SILK")
      (footprint "eagle-import:1X01_SMD_3.25X0.85MM_NO_SILK")
      (libsource (lib "eagle-import") (part "M01PTH_SMD_3.25X0.85MM_NO_SILK"))
    )
    (comp (ref "JP1415")
      (value "M01PTH_SMD_3.25X0.85MM_NO_SILK")
      (footprint "eagle-import:1X01_SMD_3.25X0.85MM_NO_SILK")
      (libsource (lib "eagle-import") (part "M01PTH_SMD_3.25X0.85MM_NO_SILK"))
    )
    (comp (ref "JP1416")
      (value "M01PTH_SMD_3.25X0.85MM_NO_SILK")
      (footprint "eagle-import:1X01_SMD_3.25X0.85MM_NO_SILK")
      (libsource (lib "eagle-import") (part "M01PTH_SMD_3.25X0.85MM_NO_SILK"))
    )
    (comp (ref "JP1417")
      (value "M01PTH_SMD_3.25X0.85MM_NO_SILK")
      (footprint "eagle-import:1X01_SMD_3.25X0.85MM_NO_SILK")
      (libsource (lib "eagle-import") (part "M01PTH_SMD_3.25X0.85MM_NO_SILK"))
    )
    (comp (ref "JP1418")
      (value "M01PTH_SMD_3.25X0.85MM_NO_SILK")
      (footprint "eagle-import:1X01_SMD_3.25X0.85MM_NO_SILK")
      (libsource (lib "eagle-import") (part "M01PTH_SMD_3.25X0.85MM_NO_SILK"))
    )
    (comp (ref "JP1419")
      (value "M01PTH_SMD_3.25X0.85MM_NO_SILK")
      (footprint "eagle-import:1X01_SMD_3.25X0.85MM_NO_SILK")
      (libsource (lib "eagle-import") (part "M01PTH_SMD_3.25X0.85MM_NO_SILK"))
    )
    (comp (ref "JP1420")
      (value "M01PTH_SMD_3.25X0.85MM_NO_SILK")
      (footprint "eagle-import:1X01_SMD_3.25X0.85MM_NO_SILK")
      (libsource (lib "eagle-import") (part "M01PTH_SMD_3.25X0.85MM_NO_SILK"))
    )
    (comp (ref "JP1421")
      (value "M01PTH_SMD_3.25X0.85MM_NO_SILK")
      (footprint "eagle-import:1X01_SMD_3.25X0.85MM_NO_SILK")
      (libsource (lib "eagle-import") (part "M01PTH_SMD_3.25X0.85MM_NO_SILK"))
    )
    (comp (ref "JP1422")
      (value "M01PTH_SMD_3.25X0.85MM_NO_SILK")
      (footprint "eagle-import:1X01_SMD_3.25X0.85MM_NO_SILK")
      (libsource (lib "eagle-import") (part "M01PTH_SMD_3.25X0.85MM_NO_SILK"))
    )
    (comp (ref "JP1423")
      (value "M01PTH_SMD_3.25X0.85MM_NO_SILK")
      (footprint "eagle-import:1X01_SMD_3.25X0.85MM_NO_SILK")
      (libsource (lib "eagle-import") (part "M01PTH_SMD_3.25X0.85MM_NO_SILK"))
    )
    (comp (ref "JP1424")
      (value "M01PTH_SMD_3.25X0.85MM_NO_SILK")
      (footprint "eagle-import:1X01_SMD_3.25X0.85MM_NO_SILK")
      (libsource (lib "eagle-import") (part "M01PTH_SMD_3.25X0.85MM_NO_SILK"))
    )
    (comp (ref "JP1425")
      (value "M01PTH_SMD_3.25X0.85MM_NO_SILK")
      (footprint "eagle-import:1X01_SMD_3.25X0.85MM_NO_SILK")
      (libsource (lib "eagle-import") (part "M01PTH_SMD_3.25X0.85MM_NO_SILK"))
    )
    (comp (ref "JP1426")
      (value "M01PTH_SMD_3.25X0.85MM_NO_SILK")
      (footprint "eagle-import:1X01_SMD_3.25X0.85MM_NO_SILK")
      (libsource (lib "eagle-import") (part "M01PTH_SMD_3.25X0.85MM_NO_SILK"))
    )
    (comp (ref "JP1427")
      (value "M01PTH_SMD_3.25X0.85MM_NO_SILK")
      (footprint "eagle-import:1X01_SMD_3.25X0.85MM_NO_SILK")
      (libsource (lib "eagle-import") (part "M01PTH_SMD_3.25X0.85MM_NO_SILK"))
    )
    (comp (ref "JP1428")
      (value "M01PTH_SMD_3.25X0.85MM_NO_SILK")
      (footprint "eagle-import:1X01_SMD_3.25X0.85MM_NO_SILK")
      (libsource (lib "eagle-import") (part "M01PTH_SMD_3.25X0.85MM_NO_SILK"))
    )
    (comp (ref "JP1429")
      (value "M01PTH_SMD_3.25X0.85MM_NO_SILK")
      (footprint "eagle-import:1X01_SMD_3.25X0.85MM_NO_SILK")
      (libsource (lib "eagle-import") (part "M01PTH_SMD_3.25X0.85MM_NO_SILK"))
    )
    (comp (ref "JP1430")
      (value "M01PTH_SMD_3.25X0.85MM_NO_SILK")
      (footprint "eagle-import:1X01_SMD_3.25X0.85MM_NO_SILK")
      (libsource (lib "eagle-import") (part "M01PTH_SMD_3.25X0.85MM_NO_SILK"))
    )
    (comp (ref "JP1431")
      (value "M01PTH_SMD_3.25X0.85MM_NO_SILK")
      (footprint "eagle-import:1X01_SMD_3.25X0.85MM_NO_SILK")
      (libsource (lib "eagle-import") (part "M01PTH_SMD_3.25X0.85MM_NO_SILK"))
    )
    (comp (ref "JP1432")
      (value "M01PTH_SMD_3.25X0.85MM_NO_SILK")
      (footprint "eagle-import:1X01_SMD_3.25X0.85MM_NO_SILK")
      (libsource (lib "eagle-import") (part "M01PTH_SMD_3.25X0.85MM_NO_SILK"))
    )
    (comp (ref "JP1433")
      (value "M01PTH_SMD_3.25X0.85MM_NO_SILK")
      (footprint "eagle-import:1X01_SMD_3.25X0.85MM_NO_SILK")
      (libsource (lib "eagle-import") (part "M01PTH_SMD_3.25X0.85MM_NO_SILK"))
    )
    (comp (ref "JP1434")
      (value "M01PTH_SMD_3.25X0.85MM_NO_SILK")
      (footprint "eagle-import:1X01_SMD_3.25X0.85MM_NO_SILK")
      (libsource (lib "eagle-import") (part "M01PTH_SMD_3.25X0.85MM_NO_SILK"))
    )
    (comp (ref "JP1435")
      (value "M01PTH_SMD_3.25X0.85MM_NO_SILK")
      (footprint "eagle-import:1X01_SMD_3.25X0.85MM_NO_SILK")
      (libsource (lib "eagle-import") (part "M01PTH_SMD_3.25X0.85MM_NO_SILK"))
    )
    (comp (ref "JP1436")
      (value "M01PTH_SMD_3.25X0.85MM_NO_SILK")
      (footprint "eagle-import:1X01_SMD_3.25X0.85MM_NO_SILK")
      (libsource (lib "eagle-import") (part "M01PTH_SMD_3.25X0.85MM_NO_SILK"))
    )
    (comp (ref "JP1437")
      (value "M01PTH_SMD_3.25X0.85MM_NO_SILK")
      (footprint "eagle-import:1X01_SMD_3.25X0.85MM_NO_SILK")
      (libsource (lib "eagle-import") (part "M01PTH_SMD_3.25X0.85MM_NO_SILK"))
    )
    (comp (ref "JP1438")
      (value "M01PTH_SMD_3.25X0.85MM_NO_SILK")
      (footprint "eagle-import:1X01_SMD_3.25X0.85MM_NO_SILK")
      (libsource (lib "eagle-import") (part "M01PTH_SMD_3.25X0.85MM_NO_SILK"))
    )
    (comp (ref "JP1439")
      (value "M01PTH_SMD_3.25X0.85MM_NO_SILK")
      (footprint "eagle-import:1X01_SMD_3.25X0.85MM_NO_SILK")
      (libsource (lib "eagle-import") (part "M01PTH_SMD_3.25X0.85MM_NO_SILK"))
    )
    (comp (ref "JP1440")
      (value "M01PTH_SMD_3.25X0.85MM_NO_SILK")
      (footprint "eagle-import:1X01_SMD_3.25X0.85MM_NO_SILK")
      (libsource (lib "eagle-import") (part "M01PTH_SMD_3.25X0.85MM_NO_SILK"))
    )
    (comp (ref "JP1441")
      (value "M01PTH_SMD_3.25X0.85MM_NO_SILK")
      (footprint "eagle-import:1X01_SMD_3.25X0.85MM_NO_SILK")
      (libsource (lib "eagle-import") (part "M01PTH_SMD_3.25X0.85MM_NO_SILK"))
    )
    (comp (ref "JP1442")
      (value "M01PTH_SMD_3.25X0.85MM_NO_SILK")
      (footprint "eagle-import:1X01_SMD_3.25X0.85MM_NO_SILK")
      (libsource (lib "eagle-import") (part "M01PTH_SMD_3.25X0.85MM_NO_SILK"))
    )
    (comp (ref "JP1443")
      (value "M01PTH_SMD_3.25X0.85MM_NO_SILK")
      (footprint "eagle-import:1X01_SMD_3.25X0.85MM_NO_SILK")
      (libsource (lib "eagle-import") (part "M01PTH_SMD_3.25X0.85MM_NO_SILK"))
    )
    (comp (ref "JP1444")
      (value "M01PTH_SMD_3.25X0.85MM_NO_SILK")
      (footprint "eagle-import:1X01_SMD_3.25X0.85MM_NO_SILK")
      (libsource (lib "eagle-import") (part "M01PTH_SMD_3.25X0.85MM_NO_SILK"))
    )
    (comp (ref "JP1445")
      (value "M01PTH_SMD_3.25X0.85MM_NO_SILK")
      (footprint "eagle-import:1X01_SMD_3.25X0.85MM_NO_SILK")
      (libsource (lib "eagle-import") (part "M01PTH_SMD_3.25X0.85MM_NO_SILK"))
    )
    (comp (ref "JP1446")
      (value "M01PTH_SMD_3.25X0.85MM_NO_SILK")
      (footprint "eagle-import:1X01_SMD_3.25X0.85MM_NO_SILK")
      (libsource (lib "eagle-import") (part "M01PTH_SMD_3.25X0.85MM_NO_SILK"))
    )
    (comp (ref "JP1447")
      (value "M01PTH_SMD_3.25X0.85MM_NO_SILK")
      (footprint "eagle-import:1X01_SMD_3.25X0.85MM_NO_SILK")
      (libsource (lib "eagle-import") (part "M01PTH_SMD_3.25X0.85MM_NO_SILK"))
    )
    (comp (ref "JP1448")
      (value "M01PTH_SMD_3.25X0.85MM_NO_SILK")
      (footprint "eagle-import:1X01_SMD_3.25X0.85MM_NO_SILK")
      (libsource (lib "eagle-import") (part "M01PTH_SMD_3.25X0.85MM_NO_SILK"))
    )
    (comp (ref "JP1449")
      (value "M01PTH_SMD_3.25X0.85MM_NO_SILK")
      (footprint "eagle-import:1X01_SMD_3.25X0.85MM_NO_SILK")
      (libsource (lib "eagle-import") (part "M01PTH_SMD_3.25X0.85MM_NO_SILK"))
    )
    (comp (ref "JP1450")
      (value "M01PTH_SMD_3.25X0.85MM_NO_SILK")
      (footprint "eagle-import:1X01_SMD_3.25X0.85MM_NO_SILK")
      (libsource (lib "eagle-import") (part "M01PTH_SMD_3.25X0.85MM_NO_SILK"))
    )
    (comp (ref "JP1451")
      (value "M01PTH_SMD_3.25X0.85MM_NO_SILK")
      (footprint "eagle-import:1X01_SMD_3.25X0.85MM_NO_SILK")
      (libsource (lib "eagle-import") (part "M01PTH_SMD_3.25X0.85MM_NO_SILK"))
    )
    (comp (ref "JP1452")
      (value "M01PTH_SMD_3.25X0.85MM_NO_SILK")
      (footprint "eagle-import:1X01_SMD_3.25X0.85MM_NO_SILK")
      (libsource (lib "eagle-import") (part "M01PTH_SMD_3.25X0.85MM_NO_SILK"))
    )
    (comp (ref "JP1453")
      (value "M01PTH_SMD_3.25X0.85MM_NO_SILK")
      (footprint "eagle-import:1X01_SMD_3.25X0.85MM_NO_SILK")
      (libsource (lib "eagle-import") (part "M01PTH_SMD_3.25X0.85MM_NO_SILK"))
    )
    (comp (ref "JP1454")
      (value "M01PTH_SMD_3.25X0.85MM_NO_SILK")
      (footprint "eagle-import:1X01_SMD_3.25X0.85MM_NO_SILK")
      (libsource (lib "eagle-import") (part "M01PTH_SMD_3.25X0.85MM_NO_SILK"))
    )
    (comp (ref "JP1455")
      (value "M01PTH_SMD_3.25X0.85MM_NO_SILK")
      (footprint "eagle-import:1X01_SMD_3.25X0.85MM_NO_SILK")
      (libsource (lib "eagle-import") (part "M01PTH_SMD_3.25X0.85MM_NO_SILK"))
    )
    (comp (ref "JP1456")
      (value "M01PTH_SMD_3.25X0.85MM_NO_SILK")
      (footprint "eagle-import:1X01_SMD_3.25X0.85MM_NO_SILK")
      (libsource (lib "eagle-import") (part "M01PTH_SMD_3.25X0.85MM_NO_SILK"))
    )
    (comp (ref "JP1457")
      (value "M01PTH_SMD_3.25X0.85MM_NO_SILK")
      (footprint "eagle-import:1X01_SMD_3.25X0.85MM_NO_SILK")
      (libsource (lib "eagle-import") (part "M01PTH_SMD_3.25X0.85MM_NO_SILK"))
    )
    (comp (ref "JP1458")
      (value "M01PTH_SMD_3.25X0.85MM_NO_SILK")
      (footprint "eagle-import:1X01_SMD_3.25X0.85MM_NO_SILK")
      (libsource (lib "eagle-import") (part "M01PTH_SMD_3.25X0.85MM_NO_SILK"))
    )
    (comp (ref "JP1459")
      (value "M01PTH_SMD_3.25X0.85MM_NO_SILK")
      (footprint "eagle-import:1X01_SMD_3.25X0.85MM_NO_SILK")
      (libsource (lib "eagle-import") (part "M01PTH_SMD_3.25X0.85MM_NO_SILK"))
    )
    (comp (ref "JP1460")
      (value "M01PTH_SMD_3.25X0.85MM_NO_SILK")
      (footprint "eagle-import:1X01_SMD_3.25X0.85MM_NO_SILK")
      (libsource (lib "eagle-import") (part "M01PTH_SMD_3.25X0.85MM_NO_SILK"))
    )
    (comp (ref "JP1461")
      (value "M01PTH_SMD_3.25X0.85MM_NO_SILK")
      (footprint "eagle-import:1X01_SMD_3.25X0.85MM_NO_SILK")
      (libsource (lib "eagle-import") (part "M01PTH_SMD_3.25X0.85MM_NO_SILK"))
    )
    (comp (ref "JP1462")
      (value "M01PTH_SMD_3.25X0.85MM_NO_SILK")
      (footprint "eagle-import:1X01_SMD_3.25X0.85MM_NO_SILK")
      (libsource (lib "eagle-import") (part "M01PTH_SMD_3.25X0.85MM_NO_SILK"))
    )
    (comp (ref "JP1463")
      (value "M01PTH_SMD_3.25X0.85MM_NO_SILK")
      (footprint "eagle-import:1X01_SMD_3.25X0.85MM_NO_SILK")
      (libsource (lib "eagle-import") (part "M01PTH_SMD_3.25X0.85MM_NO_SILK"))
    )
    (comp (ref "JP1464")
      (value "M01PTH_SMD_3.25X0.85MM_NO_SILK")
      (footprint "eagle-import:1X01_SMD_3.25X0.85MM_NO_SILK")
      (libsource (lib "eagle-import") (part "M01PTH_SMD_3.25X0.85MM_NO_SILK"))
    )
    (comp (ref "JP1465")
      (value "M01PTH_SMD_3.25X0.85MM_NO_SILK")
      (footprint "eagle-import:1X01_SMD_3.25X0.85MM_NO_SILK")
      (libsource (lib "eagle-import") (part "M01PTH_SMD_3.25X0.85MM_NO_SILK"))
    )
    (comp (ref "JP1466")
      (value "M01PTH_SMD_3.25X0.85MM_NO_SILK")
      (footprint "eagle-import:1X01_SMD_3.25X0.85MM_NO_SILK")
      (libsource (lib "eagle-import") (part "M01PTH_SMD_3.25X0.85MM_NO_SILK"))
    )
    (comp (ref "JP1467")
      (value "M01PTH_SMD_3.25X0.85MM_NO_SILK")
      (footprint "eagle-import:1X01_SMD_3.25X0.85MM_NO_SILK")
      (libsource (lib "eagle-import") (part "M01PTH_SMD_3.25X0.85MM_NO_SILK"))
    )
    (comp (ref "JP1468")
      (value "M01PTH_SMD_3.25X0.85MM_NO_SILK")
      (footprint "eagle-import:1X01_SMD_3.25X0.85MM_NO_SILK")
      (libsource (lib "eagle-import") (part "M01PTH_SMD_3.25X0.85MM_NO_SILK"))
    )
    (comp (ref "JP1469")
      (value "M01PTH_SMD_3.25X0.85MM_NO_SILK")
      (footprint "eagle-import:1X01_SMD_3.25X0.85MM_NO_SILK")
      (libsource (lib "eagle-import") (part "M01PTH_SMD_3.25X0.85MM_NO_SILK"))
    )
    (comp (ref "JP1470")
      (value "M01PTH_SMD_3.25X0.85MM_NO_SILK")
      (footprint "eagle-import:1X01_SMD_3.25X0.85MM_NO_SILK")
      (libsource (lib "eagle-import") (part "M01PTH_SMD_3.25X0.85MM_NO_SILK"))
    )
    (comp (ref "JP1471")
      (value "M01PTH_SMD_3.25X0.85MM_NO_SILK")
      (footprint "eagle-import:1X01_SMD_3.25X0.85MM_NO_SILK")
      (libsource (lib "eagle-import") (part "M01PTH_SMD_3.25X0.85MM_NO_SILK"))
    )
    (comp (ref "JP1472")
      (value "M01PTH_SMD_3.25X0.85MM_NO_SILK")
      (footprint "eagle-import:1X01_SMD_3.25X0.85MM_NO_SILK")
      (libsource (lib "eagle-import") (part "M01PTH_SMD_3.25X0.85MM_NO_SILK"))
    )
    (comp (ref "JP1473")
      (value "M01PTH_SMD_3.25X0.85MM_NO_SILK")
      (footprint "eagle-import:1X01_SMD_3.25X0.85MM_NO_SILK")
      (libsource (lib "eagle-import") (part "M01PTH_SMD_3.25X0.85MM_NO_SILK"))
    )
    (comp (ref "JP1474")
      (value "M01PTH_SMD_3.25X0.85MM_NO_SILK")
      (footprint "eagle-import:1X01_SMD_3.25X0.85MM_NO_SILK")
      (libsource (lib "eagle-import") (part "M01PTH_SMD_3.25X0.85MM_NO_SILK"))
    )
    (comp (ref "JP1475")
      (value "M01PTH_SMD_3.25X0.85MM_NO_SILK")
      (footprint "eagle-import:1X01_SMD_3.25X0.85MM_NO_SILK")
      (libsource (lib "eagle-import") (part "M01PTH_SMD_3.25X0.85MM_NO_SILK"))
    )
    (comp (ref "JP1476")
      (value "M01PTH_SMD_3.25X0.85MM_NO_SILK")
      (footprint "eagle-import:1X01_SMD_3.25X0.85MM_NO_SILK")
      (libsource (lib "eagle-import") (part "M01PTH_SMD_3.25X0.85MM_NO_SILK"))
    )
    (comp (ref "JP1477")
      (value "M01PTH_SMD_3.25X0.85MM_NO_SILK")
      (footprint "eagle-import:1X01_SMD_3.25X0.85MM_NO_SILK")
      (libsource (lib "eagle-import") (part "M01PTH_SMD_3.25X0.85MM_NO_SILK"))
    )
    (comp (ref "JP1478")
      (value "M01PTH_SMD_3.25X0.85MM_NO_SILK")
      (footprint "eagle-import:1X01_SMD_3.25X0.85MM_NO_SILK")
      (libsource (lib "eagle-import") (part "M01PTH_SMD_3.25X0.85MM_NO_SILK"))
    )
    (comp (ref "JP1479")
      (value "M01PTH_SMD_3.25X0.85MM_NO_SILK")
      (footprint "eagle-import:1X01_SMD_3.25X0.85MM_NO_SILK")
      (libsource (lib "eagle-import") (part "M01PTH_SMD_3.25X0.85MM_NO_SILK"))
    )
    (comp (ref "JP1480")
      (value "M01PTH_SMD_3.25X0.85MM_NO_SILK")
      (footprint "eagle-import:1X01_SMD_3.25X0.85MM_NO_SILK")
      (libsource (lib "eagle-import") (part "M01PTH_SMD_3.25X0.85MM_NO_SILK"))
    )
    (comp (ref "JP1481")
      (value "M01PTH_SMD_3.25X0.85MM_NO_SILK")
      (footprint "eagle-import:1X01_SMD_3.25X0.85MM_NO_SILK")
      (libsource (lib "eagle-import") (part "M01PTH_SMD_3.25X0.85MM_NO_SILK"))
    )
    (comp (ref "JP1482")
      (value "M01PTH_SMD_3.25X0.85MM_NO_SILK")
      (footprint "eagle-import:1X01_SMD_3.25X0.85MM_NO_SILK")
      (libsource (lib "eagle-import") (part "M01PTH_SMD_3.25X0.85MM_NO_SILK"))
    )
    (comp (ref "JP1483")
      (value "M01PTH_SMD_3.25X0.85MM_NO_SILK")
      (footprint "eagle-import:1X01_SMD_3.25X0.85MM_NO_SILK")
      (libsource (lib "eagle-import") (part "M01PTH_SMD_3.25X0.85MM_NO_SILK"))
    )
    (comp (ref "JP1484")
      (value "M01PTH_SMD_3.25X0.85MM_NO_SILK")
      (footprint "eagle-import:1X01_SMD_3.25X0.85MM_NO_SILK")
      (libsource (lib "eagle-import") (part "M01PTH_SMD_3.25X0.85MM_NO_SILK"))
    )
    (comp (ref "JP1485")
      (value "M01PTH_SMD_3.25X0.85MM_NO_SILK")
      (footprint "eagle-import:1X01_SMD_3.25X0.85MM_NO_SILK")
      (libsource (lib "eagle-import") (part "M01PTH_SMD_3.25X0.85MM_NO_SILK"))
    )
    (comp (ref "JP1486")
      (value "M01PTH_SMD_3.25X0.85MM_NO_SILK")
      (footprint "eagle-import:1X01_SMD_3.25X0.85MM_NO_SILK")
      (libsource (lib "eagle-import") (part "M01PTH_SMD_3.25X0.85MM_NO_SILK"))
    )
    (comp (ref "JP1487")
      (value "M01PTH_SMD_3.25X0.85MM_NO_SILK")
      (footprint "eagle-import:1X01_SMD_3.25X0.85MM_NO_SILK")
      (libsource (lib "eagle-import") (part "M01PTH_SMD_3.25X0.85MM_NO_SILK"))
    )
    (comp (ref "JP1488")
      (value "M01PTH_SMD_3.25X0.85MM_NO_SILK")
      (footprint "eagle-import:1X01_SMD_3.25X0.85MM_NO_SILK")
      (libsource (lib "eagle-import") (part "M01PTH_SMD_3.25X0.85MM_NO_SILK"))
    )
    (comp (ref "JP1489")
      (value "M01PTH_SMD_3.25X0.85MM_NO_SILK")
      (footprint "eagle-import:1X01_SMD_3.25X0.85MM_NO_SILK")
      (libsource (lib "eagle-import") (part "M01PTH_SMD_3.25X0.85MM_NO_SILK"))
    )
    (comp (ref "JP1490")
      (value "M01PTH_SMD_3.25X0.85MM_NO_SILK")
      (footprint "eagle-import:1X01_SMD_3.25X0.85MM_NO_SILK")
      (libsource (lib "eagle-import") (part "M01PTH_SMD_3.25X0.85MM_NO_SILK"))
    )
    (comp (ref "JP1491")
      (value "M01PTH_SMD_3.25X0.85MM_NO_SILK")
      (footprint "eagle-import:1X01_SMD_3.25X0.85MM_NO_SILK")
      (libsource (lib "eagle-import") (part "M01PTH_SMD_3.25X0.85MM_NO_SILK"))
    )
    (comp (ref "JP1492")
      (value "M01PTH_SMD_3.25X0.85MM_NO_SILK")
      (footprint "eagle-import:1X01_SMD_3.25X0.85MM_NO_SILK")
      (libsource (lib "eagle-import") (part "M01PTH_SMD_3.25X0.85MM_NO_SILK"))
    )
    (comp (ref "JP1493")
      (value "M01PTH_SMD_3.25X0.85MM_NO_SILK")
      (footprint "eagle-import:1X01_SMD_3.25X0.85MM_NO_SILK")
      (libsource (lib "eagle-import") (part "M01PTH_SMD_3.25X0.85MM_NO_SILK"))
    )
    (comp (ref "JP1494")
      (value "M01PTH_SMD_3.25X0.85MM_NO_SILK")
      (footprint "eagle-import:1X01_SMD_3.25X0.85MM_NO_SILK")
      (libsource (lib "eagle-import") (part "M01PTH_SMD_3.25X0.85MM_NO_SILK"))
    )
    (comp (ref "JP1495")
      (value "M01PTH_SMD_3.25X0.85MM_NO_SILK")
      (footprint "eagle-import:1X01_SMD_3.25X0.85MM_NO_SILK")
      (libsource (lib "eagle-import") (part "M01PTH_SMD_3.25X0.85MM_NO_SILK"))
    )
    (comp (ref "JP1496")
      (value "M01PTH_SMD_3.25X0.85MM_NO_SILK")
      (footprint "eagle-import:1X01_SMD_3.25X0.85MM_NO_SILK")
      (libsource (lib "eagle-import") (part "M01PTH_SMD_3.25X0.85MM_NO_SILK"))
    )
    (comp (ref "JP1497")
      (value "M01PTH_SMD_3.25X0.85MM_NO_SILK")
      (footprint "eagle-import:1X01_SMD_3.25X0.85MM_NO_SILK")
      (libsource (lib "eagle-import") (part "M01PTH_SMD_3.25X0.85MM_NO_SILK"))
    )
    (comp (ref "JP1498")
      (value "M01PTH_SMD_3.25X0.85MM_NO_SILK")
      (footprint "eagle-import:1X01_SMD_3.25X0.85MM_NO_SILK")
      (libsource (lib "eagle-import") (part "M01PTH_SMD_3.25X0.85MM_NO_SILK"))
    )
    (comp (ref "JP1499")
      (value "M01PTH_SMD_3.25X0.85MM_NO_SILK")
      (footprint "eagle-import:1X01_SMD_3.25X0.85MM_NO_SILK")
      (libsource (lib "eagle-import") (part "M01PTH_SMD_3.25X0.85MM_NO_SILK"))
    )
    (comp (ref "JP1500")
      (value "M01PTH_SMD_3.25X0.85MM_NO_SILK")
      (footprint "eagle-import:1X01_SMD_3.25X0.85MM_NO_SILK")
      (libsource (lib "eagle-import") (part "M01PTH_SMD_3.25X0.85MM_NO_SILK"))
    )
  )
  (nets
    (net (code "1") (name "/0_1440392763") (class "Default")
      (node (ref "JP1") (pin "1") (pinfunction "1_1") (pintype "passive"))
      (node (ref "JP1261") (pin "P$1") (pinfunction "1_P$1") (pintype "passive"))
    )
    (net (code "2") (name "/0_1440392821") (class "Default")
      (node (ref "JP1451") (pin "P$1") (pinfunction "1_P$1") (pintype "passive"))
      (node (ref "JP5") (pin "1") (pinfunction "1_1") (pintype "passive"))
    )
    (net (code "3") (name "/0_1440392850") (class "Default")
      (node (ref "JP1459") (pin "P$1") (pinfunction "1_P$1") (pintype "passive"))
      (node (ref "JP6") (pin "1") (pinfunction "1_1") (pintype "passive"))
    )
    (net (code "4") (name "/1_1440392763") (class "Default")
      (node (ref "JP11") (pin "1") (pinfunction "1_1") (pintype "passive"))
      (node (ref "JP1263") (pin "P$1") (pinfunction "1_P$1") (pintype "passive"))
    )
    (net (code "5") (name "/1_1440392821") (class "Default")
      (node (ref "JP1452") (pin "P$1") (pinfunction "1_P$1") (pintype "passive"))
      (node (ref "JP15") (pin "1") (pinfunction "1_1") (pintype "passive"))
    )
    (net (code "6") (name "/1_1440392850") (class "Default")
      (node (ref "JP1460") (pin "P$1") (pinfunction "1_P$1") (pintype "passive"))
      (node (ref "JP16") (pin "1") (pinfunction "1_1") (pintype "passive"))
    )
    (net (code "7") (name "/2_1440392763") (class "Default")
      (node (ref "JP1265") (pin "P$1") (pinfunction "1_P$1") (pintype "passive"))
      (node (ref "JP21") (pin "1") (pinfunction "1_1") (pintype "passive"))
    )
    (net (code "8") (name "/2_1440392821") (class "Default")
      (node (ref "JP1481") (pin "P$1") (pinfunction "1_P$1") (pintype "passive"))
      (node (ref "JP295") (pin "1") (pinfunction "1_1") (pintype "passive"))
    )
    (net (code "9") (name "/2_1440392850") (class "Default")
      (node (ref "JP1489") (pin "P$1") (pinfunction "1_P$1") (pintype "passive"))
      (node (ref "JP296") (pin "1") (pinfunction "1_1") (pintype "passive"))
    )
    (net (code "10") (name "/3_1440392763") (class "Default")
      (node (ref "JP1267") (pin "P$1") (pinfunction "1_P$1") (pintype "passive"))
      (node (ref "JP31") (pin "1") (pinfunction "1_1") (pintype "passive"))
    )
    (net (code "11") (name "/3_1440392821") (class "Default")
      (node (ref "JP1482") (pin "P$1") (pinfunction "1_P$1") (pintype "passive"))
      (node (ref "JP285") (pin "1") (pinfunction "1_1") (pintype "passive"))
    )
    (net (code "12") (name "/3_1440392850") (class "Default")
      (node (ref "JP1490") (pin "P$1") (pinfunction "1_P$1") (pintype "passive"))
      (node (ref "JP286") (pin "1") (pinfunction "1_1") (pintype "passive"))
    )
    (net (code "13") (name "/4_1440392763") (class "Default")
      (node (ref "JP1269") (pin "P$1") (pinfunction "1_P$1") (pintype "passive"))
      (node (ref "JP41") (pin "1") (pinfunction "1_1") (pintype "passive"))
    )
    (net (code "14") (name "/4_1440392821") (class "Default")
      (node (ref "JP1450") (pin "P$1") (pinfunction "1_P$1") (pintype "passive"))
      (node (ref "JP25") (pin "1") (pinfunction "1_1") (pintype "passive"))
    )
    (net (code "15") (name "/4_1440392850") (class "Default")
      (node (ref "JP1458") (pin "P$1") (pinfunction "1_P$1") (pintype "passive"))
      (node (ref "JP26") (pin "1") (pinfunction "1_1") (pintype "passive"))
    )
    (net (code "16") (name "/5_1440392763") (class "Default")
      (node (ref "JP1271") (pin "P$1") (pinfunction "1_P$1") (pintype "passive"))
      (node (ref "JP51") (pin "1") (pinfunction "1_1") (pintype "passive"))
    )
    (net (code "17") (name "/5_1440392821") (class "Default")
      (node (ref "JP1453") (pin "P$1") (pinfunction "1_P$1") (pintype "passive"))
      (node (ref "JP35") (pin "1") (pinfunction "1_1") (pintype "passive"))
    )
    (net (code "18") (name "/5_1440392850") (class "Default")
      (node (ref "JP1461") (pin "P$1") (pinfunction "1_P$1") (pintype "passive"))
      (node (ref "JP36") (pin "1") (pinfunction "1_1") (pintype "passive"))
    )
    (net (code "19") (name "/6_1440392763") (class "Default")
      (node (ref "JP1273") (pin "P$1") (pinfunction "1_P$1") (pintype "passive"))
      (node (ref "JP61") (pin "1") (pinfunction "1_1") (pintype "passive"))
    )
    (net (code "20") (name "/6_1440392821") (class "Default")
      (node (ref "JP1480") (pin "P$1") (pinfunction "1_P$1") (pintype "passive"))
      (node (ref "JP275") (pin "1") (pinfunction "1_1") (pintype "passive"))
    )
    (net (code "21") (name "/6_1440392850") (class "Default")
      (node (ref "JP1488") (pin "P$1") (pinfunction "1_P$1") (pintype "passive"))
      (node (ref "JP276") (pin "1") (pinfunction "1_1") (pintype "passive"))
    )
    (net (code "22") (name "/7_1440392763") (class "Default")
      (node (ref "JP1275") (pin "P$1") (pinfunction "1_P$1") (pintype "passive"))
      (node (ref "JP71") (pin "1") (pinfunction "1_1") (pintype "passive"))
    )
    (net (code "23") (name "/7_1440392821") (class "Default")
      (node (ref "JP1483") (pin "P$1") (pinfunction "1_P$1") (pintype "passive"))
      (node (ref "JP265") (pin "1") (pinfunction "1_1") (pintype "passive"))
    )
    (net (code "24") (name "/7_1440392850") (class "Default")
      (node (ref "JP1491") (pin "P$1") (pinfunction "1_P$1") (pintype "passive"))
      (node (ref "JP266") (pin "1") (pinfunction "1_1") (pintype "passive"))
    )
    (net (code "25") (name "/8_1440392763") (class "Default")
      (node (ref "JP1277") (pin "P$1") (pinfunction "1_P$1") (pintype "passive"))
      (node (ref "JP81") (pin "1") (pinfunction "1_1") (pintype "passive"))
    )
    (net (code "26") (name "/8_1440392821") (class "Default")
      (node (ref "JP1449") (pin "P$1") (pinfunction "1_P$1") (pintype "passive"))
      (node (ref "JP45") (pin "1") (pinfunction "1_1") (pintype "passive"))
    )
    (net (code "27") (name "/8_1440392850") (class "Default")
      (node (ref "JP1457") (pin "P$1") (pinfunction "1_P$1") (pintype "passive"))
      (node (ref "JP46") (pin "1") (pinfunction "1_1") (pintype "passive"))
    )
    (net (code "28") (name "/9_1440392763") (class "Default")
      (node (ref "JP1279") (pin "P$1") (pinfunction "1_P$1") (pintype "passive"))
      (node (ref "JP91") (pin "1") (pinfunction "1_1") (pintype "passive"))
    )
    (net (code "29") (name "/9_1440392821") (class "Default")
      (node (ref "JP1454") (pin "P$1") (pinfunction "1_P$1") (pintype "passive"))
      (node (ref "JP55") (pin "1") (pinfunction "1_1") (pintype "passive"))
    )
    (net (code "30") (name "/9_1440392850") (class "Default")
      (node (ref "JP1462") (pin "P$1") (pinfunction "1_P$1") (pintype "passive"))
      (node (ref "JP56") (pin "1") (pinfunction "1_1") (pintype "passive"))
    )
    (net (code "31") (name "/10_1440392763") (class "Default")
      (node (ref "JP101") (pin "1") (pinfunction "1_1") (pintype "passive"))
      (node (ref "JP1281") (pin "P$1") (pinfunction "1_P$1") (pintype "passive"))
    )
    (net (code "32") (name "/10_1440392821") (class "Default")
      (node (ref "JP1479") (pin "P$1") (pinfunction "1_P$1") (pintype "passive"))
      (node (ref "JP255") (pin "1") (pinfunction "1_1") (pintype "passive"))
    )
    (net (code "33") (name "/10_1440392850") (class "Default")
      (node (ref "JP1487") (pin "P$1") (pinfunction "1_P$1") (pintype "passive"))
      (node (ref "JP256") (pin "1") (pinfunction "1_1") (pintype "passive"))
    )
    (net (code "34") (name "/11_1440392763") (class "Default")
      (node (ref "JP111") (pin "1") (pinfunction "1_1") (pintype "passive"))
      (node (ref "JP1283") (pin "P$1") (pinfunction "1_P$1") (pintype "passive"))
    )
    (net (code "35") (name "/11_1440392821") (class "Default")
      (node (ref "JP1484") (pin "P$1") (pinfunction "1_P$1") (pintype "passive"))
      (node (ref "JP245") (pin "1") (pinfunction "1_1") (pintype "passive"))
    )
    (net (code "36") (name "/11_1440392850") (class "Default")
      (node (ref "JP1492") (pin "P$1") (pinfunction "1_P$1") (pintype "passive"))
      (node (ref "JP246") (pin "1") (pinfunction "1_1") (pintype "passive"))
    )
    (net (code "37") (name "/12_1440392763") (class "Default")
      (node (ref "JP121") (pin "1") (pinfunction "1_1") (pintype "passive"))
      (node (ref "JP1285") (pin "P$1") (pinfunction "1_P$1") (pintype "passive"))
    )
    (net (code "38") (name "/12_1440392821") (class "Default")
      (node (ref "JP1448") (pin "P$1") (pinfunction "1_P$1") (pintype "passive"))
      (node (ref "JP65") (pin "1") (pinfunction "1_1") (pintype "passive"))
    )
    (net (code "39") (name "/12_1440392850") (class "Default")
      (node (ref "JP1456") (pin "P$1") (pinfunction "1_P$1") (pintype "passive"))
      (node (ref "JP66") (pin "1") (pinfunction "1_1") (pintype "passive"))
    )
    (net (code "40") (name "/13_1440392763") (class "Default")
      (node (ref "JP1287") (pin "P$1") (pinfunction "1_P$1") (pintype "passive"))
      (node (ref "JP131") (pin "1") (pinfunction "1_1") (pintype "passive"))
    )
    (net (code "41") (name "/13_1440392821") (class "Default")
      (node (ref "JP1455") (pin "P$1") (pinfunction "1_P$1") (pintype "passive"))
      (node (ref "JP75") (pin "1") (pinfunction "1_1") (pintype "passive"))
    )
    (net (code "42") (name "/13_1440392850") (class "Default")
      (node (ref "JP1463") (pin "P$1") (pinfunction "1_P$1") (pintype "passive"))
      (node (ref "JP76") (pin "1") (pinfunction "1_1") (pintype "passive"))
    )
    (net (code "43") (name "/14_1440392763") (class "Default")
      (node (ref "JP1289") (pin "P$1") (pinfunction "1_P$1") (pintype "passive"))
      (node (ref "JP141") (pin "1") (pinfunction "1_1") (pintype "passive"))
    )
    (net (code "44") (name "/14_1440392821") (class "Default")
      (node (ref "JP1478") (pin "P$1") (pinfunction "1_P$1") (pintype "passive"))
      (node (ref "JP235") (pin "1") (pinfunction "1_1") (pintype "passive"))
    )
    (net (code "45") (name "/14_1440392850") (class "Default")
      (node (ref "JP1464") (pin "P$1") (pinfunction "1_P$1") (pintype "passive"))
      (node (ref "JP86") (pin "1") (pinfunction "1_1") (pintype "passive"))
    )
    (net (code "46") (name "/15_1440392763") (class "Default")
      (node (ref "JP1291") (pin "P$1") (pinfunction "1_P$1") (pintype "passive"))
      (node (ref "JP151") (pin "1") (pinfunction "1_1") (pintype "passive"))
    )
    (net (code "47") (name "/15_1440392821") (class "Default")
      (node (ref "JP1485") (pin "P$1") (pinfunction "1_P$1") (pintype "passive"))
      (node (ref "JP225") (pin "1") (pinfunction "1_1") (pintype "passive"))
    )
    (net (code "48") (name "/15_1440392850") (class "Default")
      (node (ref "JP1465") (pin "P$1") (pinfunction "1_P$1") (pintype "passive"))
      (node (ref "JP96") (pin "1") (pinfunction "1_1") (pintype "passive"))
    )
    (net (code "49") (name "/16_1440392763") (class "Default")
      (node (ref "JP1293") (pin "P$1") (pinfunction "1_P$1") (pintype "passive"))
      (node (ref "JP161") (pin "1") (pinfunction "1_1") (pintype "passive"))
    )
    (net (code "50") (name "/16_1440392821") (class "Default")
      (node (ref "JP1447") (pin "P$1") (pinfunction "1_P$1") (pintype "passive"))
      (node (ref "JP85") (pin "1") (pinfunction "1_1") (pintype "passive"))
    )
    (net (code "51") (name "/16_1440392850") (class "Default")
      (node (ref "JP106") (pin "1") (pinfunction "1_1") (pintype "passive"))
      (node (ref "JP1466") (pin "P$1") (pinfunction "1_P$1") (pintype "passive"))
    )
    (net (code "52") (name "/17_1440392763") (class "Default")
      (node (ref "JP1295") (pin "P$1") (pinfunction "1_P$1") (pintype "passive"))
      (node (ref "JP171") (pin "1") (pinfunction "1_1") (pintype "passive"))
    )
    (net (code "53") (name "/17_1440392821") (class "Default")
      (node (ref "JP1477") (pin "P$1") (pinfunction "1_P$1") (pintype "passive"))
      (node (ref "JP215") (pin "1") (pinfunction "1_1") (pintype "passive"))
    )
    (net (code "54") (name "/17_1440392850") (class "Default")
      (node (ref "JP116") (pin "1") (pinfunction "1_1") (pintype "passive"))
      (node (ref "JP1467") (pin "P$1") (pinfunction "1_P$1") (pintype "passive"))
    )
    (net (code "55") (name "/18_1440392763") (class "Default")
      (node (ref "JP1297") (pin "P$1") (pinfunction "1_P$1") (pintype "passive"))
      (node (ref "JP181") (pin "1") (pinfunction "1_1") (pintype "passive"))
    )
    (net (code "56") (name "/18_1440392821") (class "Default")
      (node (ref "JP1446") (pin "P$1") (pinfunction "1_P$1") (pintype "passive"))
      (node (ref "JP95") (pin "1") (pinfunction "1_1") (pintype "passive"))
    )
    (net (code "57") (name "/18_1440392850") (class "Default")
      (node (ref "JP126") (pin "1") (pinfunction "1_1") (pintype "passive"))
      (node (ref "JP1468") (pin "P$1") (pinfunction "1_P$1") (pintype "passive"))
    )
    (net (code "58") (name "/19_1440392763") (class "Default")
      (node (ref "JP1299") (pin "P$1") (pinfunction "1_P$1") (pintype "passive"))
      (node (ref "JP191") (pin "1") (pinfunction "1_1") (pintype "passive"))
    )
    (net (code "59") (name "/19_1440392821") (class "Default")
      (node (ref "JP1476") (pin "P$1") (pinfunction "1_P$1") (pintype "passive"))
      (node (ref "JP205") (pin "1") (pinfunction "1_1") (pintype "passive"))
    )
    (net (code "60") (name "/19_1440392850") (class "Default")
      (node (ref "JP136") (pin "1") (pinfunction "1_1") (pintype "passive"))
      (node (ref "JP1469") (pin "P$1") (pinfunction "1_P$1") (pintype "passive"))
    )
    (net (code "61") (name "/20_1440392763") (class "Default")
      (node (ref "JP1301") (pin "P$1") (pinfunction "1_P$1") (pintype "passive"))
      (node (ref "JP201") (pin "1") (pinfunction "1_1") (pintype "passive"))
    )
    (net (code "62") (name "/20_1440392821") (class "Default")
      (node (ref "JP105") (pin "1") (pinfunction "1_1") (pintype "passive"))
      (node (ref "JP1445") (pin "P$1") (pinfunction "1_P$1") (pintype "passive"))
    )
    (net (code "63") (name "/20_1440392850") (class "Default")
      (node (ref "JP146") (pin "1") (pinfunction "1_1") (pintype "passive"))
      (node (ref "JP1470") (pin "P$1") (pinfunction "1_P$1") (pintype "passive"))
    )
    (net (code "64") (name "/21_1440392763") (class "Default")
      (node (ref "JP1303") (pin "P$1") (pinfunction "1_P$1") (pintype "passive"))
      (node (ref "JP211") (pin "1") (pinfunction "1_1") (pintype "passive"))
    )
    (net (code "65") (name "/21_1440392821") (class "Default")
      (node (ref "JP1475") (pin "P$1") (pinfunction "1_P$1") (pintype "passive"))
      (node (ref "JP195") (pin "1") (pinfunction "1_1") (pintype "passive"))
    )
    (net (code "66") (name "/21_1440392850") (class "Default")
      (node (ref "JP1486") (pin "P$1") (pinfunction "1_P$1") (pintype "passive"))
      (node (ref "JP236") (pin "1") (pinfunction "1_1") (pintype "passive"))
    )
    (net (code "67") (name "/22_1440392763") (class "Default")
      (node (ref "JP1305") (pin "P$1") (pinfunction "1_P$1") (pintype "passive"))
      (node (ref "JP221") (pin "1") (pinfunction "1_1") (pintype "passive"))
    )
    (net (code "68") (name "/22_1440392821") (class "Default")
      (node (ref "JP115") (pin "1") (pinfunction "1_1") (pintype "passive"))
      (node (ref "JP1444") (pin "P$1") (pinfunction "1_P$1") (pintype "passive"))
    )
    (net (code "69") (name "/22_1440392850") (class "Default")
      (node (ref "JP1493") (pin "P$1") (pinfunction "1_P$1") (pintype "passive"))
      (node (ref "JP226") (pin "1") (pinfunction "1_1") (pintype "passive"))
    )
    (net (code "70") (name "/23_1440392763") (class "Default")
      (node (ref "JP1307") (pin "P$1") (pinfunction "1_P$1") (pintype "passive"))
      (node (ref "JP231") (pin "1") (pinfunction "1_1") (pintype "passive"))
    )
    (net (code "71") (name "/23_1440392821") (class "Default")
      (node (ref "JP1474") (pin "P$1") (pinfunction "1_P$1") (pintype "passive"))
      (node (ref "JP185") (pin "1") (pinfunction "1_1") (pintype "passive"))
    )
    (net (code "72") (name "/23_1440392850") (class "Default")
      (node (ref "JP1494") (pin "P$1") (pinfunction "1_P$1") (pintype "passive"))
      (node (ref "JP216") (pin "1") (pinfunction "1_1") (pintype "passive"))
    )
    (net (code "73") (name "/24_1440392763") (class "Default")
      (node (ref "JP1309") (pin "P$1") (pinfunction "1_P$1") (pintype "passive"))
      (node (ref "JP241") (pin "1") (pinfunction "1_1") (pintype "passive"))
    )
    (net (code "74") (name "/24_1440392821") (class "Default")
      (node (ref "JP125") (pin "1") (pinfunction "1_1") (pintype "passive"))
      (node (ref "JP1443") (pin "P$1") (pinfunction "1_P$1") (pintype "passive"))
    )
    (net (code "75") (name "/24_1440392850") (class "Default")
      (node (ref "JP1495") (pin "P$1") (pinfunction "1_P$1") (pintype "passive"))
      (node (ref "JP206") (pin "1") (pinfunction "1_1") (pintype "passive"))
    )
    (net (code "76") (name "/25_1440392763") (class "Default")
      (node (ref "JP1311") (pin "P$1") (pinfunction "1_P$1") (pintype "passive"))
      (node (ref "JP251") (pin "1") (pinfunction "1_1") (pintype "passive"))
    )
    (net (code "77") (name "/25_1440392821") (class "Default")
      (node (ref "JP1473") (pin "P$1") (pinfunction "1_P$1") (pintype "passive"))
      (node (ref "JP175") (pin "1") (pinfunction "1_1") (pintype "passive"))
    )
    (net (code "78") (name "/25_1440392850") (class "Default")
      (node (ref "JP1496") (pin "P$1") (pinfunction "1_P$1") (pintype "passive"))
      (node (ref "JP196") (pin "1") (pinfunction "1_1") (pintype "passive"))
    )
    (net (code "79") (name "/26_1440392763") (class "Default")
      (node (ref "JP1313") (pin "P$1") (pinfunction "1_P$1") (pintype "passive"))
      (node (ref "JP261") (pin "1") (pinfunction "1_1") (pintype "passive"))
    )
    (net (code "80") (name "/26_1440392821") (class "Default")
      (node (ref "JP135") (pin "1") (pinfunction "1_1") (pintype "passive"))
      (node (ref "JP1442") (pin "P$1") (pinfunction "1_P$1") (pintype "passive"))
    )
    (net (code "81") (name "/26_1440392850") (class "Default")
      (node (ref "JP1497") (pin "P$1") (pinfunction "1_P$1") (pintype "passive"))
      (node (ref "JP186") (pin "1") (pinfunction "1_1") (pintype "passive"))
    )
    (net (code "82") (name "/27_1440392763") (class "Default")
      (node (ref "JP1315") (pin "P$1") (pinfunction "1_P$1") (pintype "passive"))
      (node (ref "JP271") (pin "1") (pinfunction "1_1") (pintype "passive"))
    )
    (net (code "83") (name "/27_1440392821") (class "Default")
      (node (ref "JP1472") (pin "P$1") (pinfunction "1_P$1") (pintype "passive"))
      (node (ref "JP165") (pin "1") (pinfunction "1_1") (pintype "passive"))
    )
    (net (code "84") (name "/27_1440392850") (class "Default")
      (node (ref "JP1498") (pin "P$1") (pinfunction "1_P$1") (pintype "passive"))
      (node (ref "JP176") (pin "1") (pinfunction "1_1") (pintype "passive"))
    )
    (net (code "85") (name "/28_1440392763") (class "Default")
      (node (ref "JP1317") (pin "P$1") (pinfunction "1_P$1") (pintype "passive"))
      (node (ref "JP281") (pin "1") (pinfunction "1_1") (pintype "passive"))
    )
    (net (code "86") (name "/28_1440392821") (class "Default")
      (node (ref "JP1441") (pin "P$1") (pinfunction "1_P$1") (pintype "passive"))
      (node (ref "JP145") (pin "1") (pinfunction "1_1") (pintype "passive"))
    )
    (net (code "87") (name "/28_1440392850") (class "Default")
      (node (ref "JP1499") (pin "P$1") (pinfunction "1_P$1") (pintype "passive"))
      (node (ref "JP166") (pin "1") (pinfunction "1_1") (pintype "passive"))
    )
    (net (code "88") (name "/29_1440392763") (class "Default")
      (node (ref "JP1319") (pin "P$1") (pinfunction "1_P$1") (pintype "passive"))
      (node (ref "JP291") (pin "1") (pinfunction "1_1") (pintype "passive"))
    )
    (net (code "89") (name "/29_1440392821") (class "Default")
      (node (ref "JP1471") (pin "P$1") (pinfunction "1_P$1") (pintype "passive"))
      (node (ref "JP155") (pin "1") (pinfunction "1_1") (pintype "passive"))
    )
    (net (code "90") (name "/29_1440392850") (class "Default")
      (node (ref "JP1500") (pin "P$1") (pinfunction "1_P$1") (pintype "passive"))
      (node (ref "JP156") (pin "1") (pinfunction "1_1") (pintype "passive"))
    )
    (net (code "91") (name "/30_1440392763") (class "Default")
      (node (ref "JP1320") (pin "P$1") (pinfunction "1_P$1") (pintype "passive"))
      (node (ref "JP292") (pin "1") (pinfunction "1_1") (pintype "passive"))
    )
    (net (code "92") (name "/31_1440392763") (class "Default")
      (node (ref "JP10") (pin "1") (pinfunction "1_1") (pintype "passive"))
      (node (ref "JP1321") (pin "P$1") (pinfunction "1_P$1") (pintype "passive"))
    )
    (net (code "93") (name "/32_1440392763") (class "Default")
      (node (ref "JP1323") (pin "P$1") (pinfunction "1_P$1") (pintype "passive"))
      (node (ref "JP20") (pin "1") (pinfunction "1_1") (pintype "passive"))
    )
    (net (code "94") (name "/33_1440392763") (class "Default")
      (node (ref "JP1325") (pin "P$1") (pinfunction "1_P$1") (pintype "passive"))
      (node (ref "JP30") (pin "1") (pinfunction "1_1") (pintype "passive"))
    )
    (net (code "95") (name "/34_1440392763") (class "Default")
      (node (ref "JP1327") (pin "P$1") (pinfunction "1_P$1") (pintype "passive"))
      (node (ref "JP40") (pin "1") (pinfunction "1_1") (pintype "passive"))
    )
    (net (code "96") (name "/35_1440392763") (class "Default")
      (node (ref "JP1329") (pin "P$1") (pinfunction "1_P$1") (pintype "passive"))
      (node (ref "JP50") (pin "1") (pinfunction "1_1") (pintype "passive"))
    )
    (net (code "97") (name "/36_1440392763") (class "Default")
      (node (ref "JP1331") (pin "P$1") (pinfunction "1_P$1") (pintype "passive"))
      (node (ref "JP60") (pin "1") (pinfunction "1_1") (pintype "passive"))
    )
    (net (code "98") (name "/37_1440392763") (class "Default")
      (node (ref "JP1333") (pin "P$1") (pinfunction "1_P$1") (pintype "passive"))
      (node (ref "JP70") (pin "1") (pinfunction "1_1") (pintype "passive"))
    )
    (net (code "99") (name "/38_1440392763") (class "Default")
      (node (ref "JP1335") (pin "P$1") (pinfunction "1_P$1") (pintype "passive"))
      (node (ref "JP80") (pin "1") (pinfunction "1_1") (pintype "passive"))
    )
    (net (code "100") (name "/39_1440392763") (class "Default")
      (node (ref "JP1337") (pin "P$1") (pinfunction "1_P$1") (pintype "passive"))
      (node (ref "JP90") (pin "1") (pinfunction "1_1") (pintype "passive"))
    )
    (net (code "101") (name "/40_1440392763") (class "Default")
      (node (ref "JP100") (pin "1") (pinfunction "1_1") (pintype "passive"))
      (node (ref "JP1339") (pin "P$1") (pinfunction "1_P$1") (pintype "passive"))
    )
    (net (code "102") (name "/41_1440392763") (class "Default")
      (node (ref "JP110") (pin "1") (pinfunction "1_1") (pintype "passive"))
      (node (ref "JP1341") (pin "P$1") (pinfunction "1_P$1") (pintype "passive"))
    )
    (net (code "103") (name "/42_1440392763") (class "Default")
      (node (ref "JP120") (pin "1") (pinfunction "1_1") (pintype "passive"))
      (node (ref "JP1343") (pin "P$1") (pinfunction "1_P$1") (pintype "passive"))
    )
    (net (code "104") (name "/43_1440392763") (class "Default")
      (node (ref "JP130") (pin "1") (pinfunction "1_1") (pintype "passive"))
      (node (ref "JP1345") (pin "P$1") (pinfunction "1_P$1") (pintype "passive"))
    )
    (net (code "105") (name "/44_1440392763") (class "Default")
      (node (ref "JP1347") (pin "P$1") (pinfunction "1_P$1") (pintype "passive"))
      (node (ref "JP140") (pin "1") (pinfunction "1_1") (pintype "passive"))
    )
    (net (code "106") (name "/45_1440392763") (class "Default")
      (node (ref "JP1349") (pin "P$1") (pinfunction "1_P$1") (pintype "passive"))
      (node (ref "JP150") (pin "1") (pinfunction "1_1") (pintype "passive"))
    )
    (net (code "107") (name "/46_1440392763") (class "Default")
      (node (ref "JP1351") (pin "P$1") (pinfunction "1_P$1") (pintype "passive"))
      (node (ref "JP160") (pin "1") (pinfunction "1_1") (pintype "passive"))
    )
    (net (code "108") (name "/47_1440392763") (class "Default")
      (node (ref "JP1353") (pin "P$1") (pinfunction "1_P$1") (pintype "passive"))
      (node (ref "JP170") (pin "1") (pinfunction "1_1") (pintype "passive"))
    )
    (net (code "109") (name "/48_1440392763") (class "Default")
      (node (ref "JP1355") (pin "P$1") (pinfunction "1_P$1") (pintype "passive"))
      (node (ref "JP180") (pin "1") (pinfunction "1_1") (pintype "passive"))
    )
    (net (code "110") (name "/49_1440392763") (class "Default")
      (node (ref "JP1357") (pin "P$1") (pinfunction "1_P$1") (pintype "passive"))
      (node (ref "JP190") (pin "1") (pinfunction "1_1") (pintype "passive"))
    )
    (net (code "111") (name "/50_1440392763") (class "Default")
      (node (ref "JP1359") (pin "P$1") (pinfunction "1_P$1") (pintype "passive"))
      (node (ref "JP200") (pin "1") (pinfunction "1_1") (pintype "passive"))
    )
    (net (code "112") (name "/51_1440392763") (class "Default")
      (node (ref "JP1361") (pin "P$1") (pinfunction "1_P$1") (pintype "passive"))
      (node (ref "JP210") (pin "1") (pinfunction "1_1") (pintype "passive"))
    )
    (net (code "113") (name "/52_1440392763") (class "Default")
      (node (ref "JP1363") (pin "P$1") (pinfunction "1_P$1") (pintype "passive"))
      (node (ref "JP220") (pin "1") (pinfunction "1_1") (pintype "passive"))
    )
    (net (code "114") (name "/53_1440392763") (class "Default")
      (node (ref "JP1365") (pin "P$1") (pinfunction "1_P$1") (pintype "passive"))
      (node (ref "JP230") (pin "1") (pinfunction "1_1") (pintype "passive"))
    )
    (net (code "115") (name "/54_1440392763") (class "Default")
      (node (ref "JP1367") (pin "P$1") (pinfunction "1_P$1") (pintype "passive"))
      (node (ref "JP240") (pin "1") (pinfunction "1_1") (pintype "passive"))
    )
    (net (code "116") (name "/55_1440392763") (class "Default")
      (node (ref "JP1369") (pin "P$1") (pinfunction "1_P$1") (pintype "passive"))
      (node (ref "JP250") (pin "1") (pinfunction "1_1") (pintype "passive"))
    )
    (net (code "117") (name "/56_1440392763") (class "Default")
      (node (ref "JP1371") (pin "P$1") (pinfunction "1_P$1") (pintype "passive"))
      (node (ref "JP260") (pin "1") (pinfunction "1_1") (pintype "passive"))
    )
    (net (code "118") (name "/57_1440392763") (class "Default")
      (node (ref "JP1373") (pin "P$1") (pinfunction "1_P$1") (pintype "passive"))
      (node (ref "JP270") (pin "1") (pinfunction "1_1") (pintype "passive"))
    )
    (net (code "119") (name "/58_1440392763") (class "Default")
      (node (ref "JP1375") (pin "P$1") (pinfunction "1_P$1") (pintype "passive"))
      (node (ref "JP280") (pin "1") (pinfunction "1_1") (pintype "passive"))
    )
    (net (code "120") (name "/59_1440392763") (class "Default")
      (node (ref "JP1377") (pin "P$1") (pinfunction "1_P$1") (pintype "passive"))
      (node (ref "JP290") (pin "1") (pinfunction "1_1") (pintype "passive"))
    )
    (net (code "121") (name "/60_1440392763") (class "Default")
      (node (ref "JP1379") (pin "P$1") (pinfunction "1_P$1") (pintype "passive"))
      (node (ref "JP300") (pin "1") (pinfunction "1_1") (pintype "passive"))
    )
    (net (code "122") (name "/61_1440392763") (class "Default")
      (node (ref "JP1380") (pin "P$1") (pinfunction "1_P$1") (pintype "passive"))
      (node (ref "JP299") (pin "1") (pinfunction "1_1") (pintype "passive"))
    )
    (net (code "123") (name "/62_1440392763") (class "Default")
      (node (ref "JP1262") (pin "P$1") (pinfunction "1_P$1") (pintype "passive"))
      (node (ref "JP2") (pin "1") (pinfunction "1_1") (pintype "passive"))
    )
    (net (code "124") (name "/63_1440392763") (class "Default")
      (node (ref "JP12") (pin "1") (pinfunction "1_1") (pintype "passive"))
      (node (ref "JP1264") (pin "P$1") (pinfunction "1_P$1") (pintype "passive"))
    )
    (net (code "125") (name "/64_1440392763") (class "Default")
      (node (ref "JP1266") (pin "P$1") (pinfunction "1_P$1") (pintype "passive"))
      (node (ref "JP22") (pin "1") (pinfunction "1_1") (pintype "passive"))
    )
    (net (code "126") (name "/65_1440392763") (class "Default")
      (node (ref "JP1268") (pin "P$1") (pinfunction "1_P$1") (pintype "passive"))
      (node (ref "JP32") (pin "1") (pinfunction "1_1") (pintype "passive"))
    )
    (net (code "127") (name "/66_1440392763") (class "Default")
      (node (ref "JP1270") (pin "P$1") (pinfunction "1_P$1") (pintype "passive"))
      (node (ref "JP42") (pin "1") (pinfunction "1_1") (pintype "passive"))
    )
    (net (code "128") (name "/67_1440392763") (class "Default")
      (node (ref "JP1272") (pin "P$1") (pinfunction "1_P$1") (pintype "passive"))
      (node (ref "JP52") (pin "1") (pinfunction "1_1") (pintype "passive"))
    )
    (net (code "129") (name "/68_1440392763") (class "Default")
      (node (ref "JP1274") (pin "P$1") (pinfunction "1_P$1") (pintype "passive"))
      (node (ref "JP62") (pin "1") (pinfunction "1_1") (pintype "passive"))
    )
    (net (code "130") (name "/69_1440392763") (class "Default")
      (node (ref "JP1276") (pin "P$1") (pinfunction "1_P$1") (pintype "passive"))
      (node (ref "JP72") (pin "1") (pinfunction "1_1") (pintype "passive"))
    )
    (net (code "131") (name "/70_1440392763") (class "Default")
      (node (ref "JP1278") (pin "P$1") (pinfunction "1_P$1") (pintype "passive"))
      (node (ref "JP82") (pin "1") (pinfunction "1_1") (pintype "passive"))
    )
    (net (code "132") (name "/71_1440392763") (class "Default")
      (node (ref "JP1280") (pin "P$1") (pinfunction "1_P$1") (pintype "passive"))
      (node (ref "JP92") (pin "1") (pinfunction "1_1") (pintype "passive"))
    )
    (net (code "133") (name "/72_1440392763") (class "Default")
      (node (ref "JP102") (pin "1") (pinfunction "1_1") (pintype "passive"))
      (node (ref "JP1282") (pin "P$1") (pinfunction "1_P$1") (pintype "passive"))
    )
    (net (code "134") (name "/73_1440392763") (class "Default")
      (node (ref "JP112") (pin "1") (pinfunction "1_1") (pintype "passive"))
      (node (ref "JP1284") (pin "P$1") (pinfunction "1_P$1") (pintype "passive"))
    )
    (net (code "135") (name "/74_1440392763") (class "Default")
      (node (ref "JP122") (pin "1") (pinfunction "1_1") (pintype "passive"))
      (node (ref "JP1286") (pin "P$1") (pinfunction "1_P$1") (pintype "passive"))
    )
    (net (code "136") (name "/75_1440392763") (class "Default")
      (node (ref "JP1288") (pin "P$1") (pinfunction "1_P$1") (pintype "passive"))
      (node (ref "JP132") (pin "1") (pinfunction "1_1") (pintype "passive"))
    )
    (net (code "137") (name "/76_1440392763") (class "Default")
      (node (ref "JP1290") (pin "P$1") (pinfunction "1_P$1") (pintype "passive"))
      (node (ref "JP142") (pin "1") (pinfunction "1_1") (pintype "passive"))
    )
    (net (code "138") (name "/77_1440392763") (class "Default")
      (node (ref "JP1292") (pin "P$1") (pinfunction "1_P$1") (pintype "passive"))
      (node (ref "JP152") (pin "1") (pinfunction "1_1") (pintype "passive"))
    )
    (net (code "139") (name "/78_1440392763") (class "Default")
      (node (ref "JP1294") (pin "P$1") (pinfunction "1_P$1") (pintype "passive"))
      (node (ref "JP162") (pin "1") (pinfunction "1_1") (pintype "passive"))
    )
    (net (code "140") (name "/79_1440392763") (class "Default")
      (node (ref "JP1296") (pin "P$1") (pinfunction "1_P$1") (pintype "passive"))
      (node (ref "JP172") (pin "1") (pinfunction "1_1") (pintype "passive"))
    )
    (net (code "141") (name "/80_1440392763") (class "Default")
      (node (ref "JP1298") (pin "P$1") (pinfunction "1_P$1") (pintype "passive"))
      (node (ref "JP182") (pin "1") (pinfunction "1_1") (pintype "passive"))
    )
    (net (code "142") (name "/81_1440392763") (class "Default")
      (node (ref "JP1300") (pin "P$1") (pinfunction "1_P$1") (pintype "passive"))
      (node (ref "JP192") (pin "1") (pinfunction "1_1") (pintype "passive"))
    )
    (net (code "143") (name "/82_1440392763") (class "Default")
      (node (ref "JP1302") (pin "P$1") (pinfunction "1_P$1") (pintype "passive"))
      (node (ref "JP202") (pin "1") (pinfunction "1_1") (pintype "passive"))
    )
    (net (code "144") (name "/83_1440392763") (class "Default")
      (node (ref "JP1304") (pin "P$1") (pinfunction "1_P$1") (pintype "passive"))
      (node (ref "JP212") (pin "1") (pinfunction "1_1") (pintype "passive"))
    )
    (net (code "145") (name "/84_1440392763") (class "Default")
      (node (ref "JP1306") (pin "P$1") (pinfunction "1_P$1") (pintype "passive"))
      (node (ref "JP222") (pin "1") (pinfunction "1_1") (pintype "passive"))
    )
    (net (code "146") (name "/85_1440392763") (class "Default")
      (node (ref "JP1308") (pin "P$1") (pinfunction "1_P$1") (pintype "passive"))
      (node (ref "JP232") (pin "1") (pinfunction "1_1") (pintype "passive"))
    )
    (net (code "147") (name "/86_1440392763") (class "Default")
      (node (ref "JP1310") (pin "P$1") (pinfunction "1_P$1") (pintype "passive"))
      (node (ref "JP242") (pin "1") (pinfunction "1_1") (pintype "passive"))
    )
    (net (code "148") (name "/87_1440392763") (class "Default")
      (node (ref "JP1312") (pin "P$1") (pinfunction "1_P$1") (pintype "passive"))
      (node (ref "JP252") (pin "1") (pinfunction "1_1") (pintype "passive"))
    )
    (net (code "149") (name "/88_1440392763") (class "Default")
      (node (ref "JP1314") (pin "P$1") (pinfunction "1_P$1") (pintype "passive"))
      (node (ref "JP262") (pin "1") (pinfunction "1_1") (pintype "passive"))
    )
    (net (code "150") (name "/89_1440392763") (class "Default")
      (node (ref "JP1316") (pin "P$1") (pinfunction "1_P$1") (pintype "passive"))
      (node (ref "JP272") (pin "1") (pinfunction "1_1") (pintype "passive"))
    )
    (net (code "151") (name "/90_1440392763") (class "Default")
      (node (ref "JP1318") (pin "P$1") (pinfunction "1_P$1") (pintype "passive"))
      (node (ref "JP282") (pin "1") (pinfunction "1_1") (pintype "passive"))
    )
    (net (code "152") (name "/91_1440392763") (class "Default")
      (node (ref "JP1322") (pin "P$1") (pinfunction "1_P$1") (pintype "passive"))
      (node (ref "JP9") (pin "1") (pinfunction "1_1") (pintype "passive"))
    )
    (net (code "153") (name "/92_1440392763") (class "Default")
      (node (ref "JP1324") (pin "P$1") (pinfunction "1_P$1") (pintype "passive"))
      (node (ref "JP19") (pin "1") (pinfunction "1_1") (pintype "passive"))
    )
    (net (code "154") (name "/93_1440392763") (class "Default")
      (node (ref "JP1326") (pin "P$1") (pinfunction "1_P$1") (pintype "passive"))
      (node (ref "JP29") (pin "1") (pinfunction "1_1") (pintype "passive"))
    )
    (net (code "155") (name "/94_1440392763") (class "Default")
      (node (ref "JP1328") (pin "P$1") (pinfunction "1_P$1") (pintype "passive"))
      (node (ref "JP39") (pin "1") (pinfunction "1_1") (pintype "passive"))
    )
    (net (code "156") (name "/95_1440392763") (class "Default")
      (node (ref "JP1330") (pin "P$1") (pinfunction "1_P$1") (pintype "passive"))
      (node (ref "JP49") (pin "1") (pinfunction "1_1") (pintype "passive"))
    )
    (net (code "157") (name "/96_1440392763") (class "Default")
      (node (ref "JP1332") (pin "P$1") (pinfunction "1_P$1") (pintype "passive"))
      (node (ref "JP59") (pin "1") (pinfunction "1_1") (pintype "passive"))
    )
    (net (code "158") (name "/97_1440392763") (class "Default")
      (node (ref "JP1334") (pin "P$1") (pinfunction "1_P$1") (pintype "passive"))
      (node (ref "JP69") (pin "1") (pinfunction "1_1") (pintype "passive"))
    )
    (net (code "159") (name "/98_1440392763") (class "Default")
      (node (ref "JP1336") (pin "P$1") (pinfunction "1_P$1") (pintype "passive"))
      (node (ref "JP79") (pin "1") (pinfunction "1_1") (pintype "passive"))
    )
    (net (code "160") (name "/99_1440392763") (class "Default")
      (node (ref "JP1338") (pin "P$1") (pinfunction "1_P$1") (pintype "passive"))
      (node (ref "JP89") (pin "1") (pinfunction "1_1") (pintype "passive"))
    )
    (net (code "161") (name "/100_1440392763") (class "Default")
      (node (ref "JP1340") (pin "P$1") (pinfunction "1_P$1") (pintype "passive"))
      (node (ref "JP99") (pin "1") (pinfunction "1_1") (pintype "passive"))
    )
    (net (code "162") (name "/101_1440392763") (class "Default")
      (node (ref "JP109") (pin "1") (pinfunction "1_1") (pintype "passive"))
      (node (ref "JP1342") (pin "P$1") (pinfunction "1_P$1") (pintype "passive"))
    )
    (net (code "163") (name "/102_1440392763") (class "Default")
      (node (ref "JP119") (pin "1") (pinfunction "1_1") (pintype "passive"))
      (node (ref "JP1344") (pin "P$1") (pinfunction "1_P$1") (pintype "passive"))
    )
    (net (code "164") (name "/103_1440392763") (class "Default")
      (node (ref "JP129") (pin "1") (pinfunction "1_1") (pintype "passive"))
      (node (ref "JP1346") (pin "P$1") (pinfunction "1_P$1") (pintype "passive"))
    )
    (net (code "165") (name "/104_1440392763") (class "Default")
      (node (ref "JP1348") (pin "P$1") (pinfunction "1_P$1") (pintype "passive"))
      (node (ref "JP139") (pin "1") (pinfunction "1_1") (pintype "passive"))
    )
    (net (code "166") (name "/105_1440392763") (class "Default")
      (node (ref "JP1350") (pin "P$1") (pinfunction "1_P$1") (pintype "passive"))
      (node (ref "JP149") (pin "1") (pinfunction "1_1") (pintype "passive"))
    )
    (net (code "167") (name "/106_1440392763") (class "Default")
      (node (ref "JP1352") (pin "P$1") (pinfunction "1_P$1") (pintype "passive"))
      (node (ref "JP159") (pin "1") (pinfunction "1_1") (pintype "passive"))
    )
    (net (code "168") (name "/107_1440392763") (class "Default")
      (node (ref "JP1354") (pin "P$1") (pinfunction "1_P$1") (pintype "passive"))
      (node (ref "JP169") (pin "1") (pinfunction "1_1") (pintype "passive"))
    )
    (net (code "169") (name "/108_1440392763") (class "Default")
      (node (ref "JP1356") (pin "P$1") (pinfunction "1_P$1") (pintype "passive"))
      (node (ref "JP179") (pin "1") (pinfunction "1_1") (pintype "passive"))
    )
    (net (code "170") (name "/109_1440392763") (class "Default")
      (node (ref "JP1358") (pin "P$1") (pinfunction "1_P$1") (pintype "passive"))
      (node (ref "JP189") (pin "1") (pinfunction "1_1") (pintype "passive"))
    )
    (net (code "171") (name "/110_1440392763") (class "Default")
      (node (ref "JP1360") (pin "P$1") (pinfunction "1_P$1") (pintype "passive"))
      (node (ref "JP199") (pin "1") (pinfunction "1_1") (pintype "passive"))
    )
    (net (code "172") (name "/111_1440392763") (class "Default")
      (node (ref "JP1362") (pin "P$1") (pinfunction "1_P$1") (pintype "passive"))
      (node (ref "JP209") (pin "1") (pinfunction "1_1") (pintype "passive"))
    )
    (net (code "173") (name "/112_1440392763") (class "Default")
      (node (ref "JP1364") (pin "P$1") (pinfunction "1_P$1") (pintype "passive"))
      (node (ref "JP219") (pin "1") (pinfunction "1_1") (pintype "passive"))
    )
    (net (code "174") (name "/113_1440392763") (class "Default")
      (node (ref "JP1366") (pin "P$1") (pinfunction "1_P$1") (pintype "passive"))
      (node (ref "JP229") (pin "1") (pinfunction "1_1") (pintype "passive"))
    )
    (net (code "175") (name "/114_1440392763") (class "Default")
      (node (ref "JP1368") (pin "P$1") (pinfunction "1_P$1") (pintype "passive"))
      (node (ref "JP239") (pin "1") (pinfunction "1_1") (pintype "passive"))
    )
    (net (code "176") (name "/115_1440392763") (class "Default")
      (node (ref "JP1370") (pin "P$1") (pinfunction "1_P$1") (pintype "passive"))
      (node (ref "JP249") (pin "1") (pinfunction "1_1") (pintype "passive"))
    )
    (net (code "177") (name "/116_1440392763") (class "Default")
      (node (ref "JP1372") (pin "P$1") (pinfunction "1_P$1") (pintype "passive"))
      (node (ref "JP259") (pin "1") (pinfunction "1_1") (pintype "passive"))
    )
    (net (code "178") (name "/117_1440392763") (class "Default")
      (node (ref "JP1374") (pin "P$1") (pinfunction "1_P$1") (pintype "passive"))
      (node (ref "JP269") (pin "1") (pinfunction "1_1") (pintype "passive"))
    )
    (net (code "179") (name "/118_1440392763") (class "Default")
      (node (ref "JP1376") (pin "P$1") (pinfunction "1_P$1") (pintype "passive"))
      (node (ref "JP279") (pin "1") (pinfunction "1_1") (pintype "passive"))
    )
    (net (code "180") (name "/119_1440392763") (class "Default")
      (node (ref "JP1378") (pin "P$1") (pinfunction "1_P$1") (pintype "passive"))
      (node (ref "JP289") (pin "1") (pinfunction "1_1") (pintype "passive"))
    )
    (net (code "181") (name "/120_1440392763") (class "Default")
      (node (ref "JP1381") (pin "P$1") (pinfunction "1_P$1") (pintype "passive"))
      (node (ref "JP8") (pin "1") (pinfunction "1_1") (pintype "passive"))
    )
    (net (code "182") (name "/121_1440392763") (class "Default")
      (node (ref "JP1383") (pin "P$1") (pinfunction "1_P$1") (pintype "passive"))
      (node (ref "JP18") (pin "1") (pinfunction "1_1") (pintype "passive"))
    )
    (net (code "183") (name "/122_1440392763") (class "Default")
      (node (ref "JP1385") (pin "P$1") (pinfunction "1_P$1") (pintype "passive"))
      (node (ref "JP28") (pin "1") (pinfunction "1_1") (pintype "passive"))
    )
    (net (code "184") (name "/123_1440392763") (class "Default")
      (node (ref "JP1387") (pin "P$1") (pinfunction "1_P$1") (pintype "passive"))
      (node (ref "JP38") (pin "1") (pinfunction "1_1") (pintype "passive"))
    )
    (net (code "185") (name "/124_1440392763") (class "Default")
      (node (ref "JP1389") (pin "P$1") (pinfunction "1_P$1") (pintype "passive"))
      (node (ref "JP48") (pin "1") (pinfunction "1_1") (pintype "passive"))
    )
    (net (code "186") (name "/125_1440392763") (class "Default")
      (node (ref "JP1391") (pin "P$1") (pinfunction "1_P$1") (pintype "passive"))
      (node (ref "JP58") (pin "1") (pinfunction "1_1") (pintype "passive"))
    )
    (net (code "187") (name "/126_1440392763") (class "Default")
      (node (ref "JP1393") (pin "P$1") (pinfunction "1_P$1") (pintype "passive"))
      (node (ref "JP68") (pin "1") (pinfunction "1_1") (pintype "passive"))
    )
    (net (code "188") (name "/127_1440392763") (class "Default")
      (node (ref "JP1395") (pin "P$1") (pinfunction "1_P$1") (pintype "passive"))
      (node (ref "JP78") (pin "1") (pinfunction "1_1") (pintype "passive"))
    )
    (net (code "189") (name "/128_1440392763") (class "Default")
      (node (ref "JP1397") (pin "P$1") (pinfunction "1_P$1") (pintype "passive"))
      (node (ref "JP88") (pin "1") (pinfunction "1_1") (pintype "passive"))
    )
    (net (code "190") (name "/129_1440392763") (class "Default")
      (node (ref "JP1399") (pin "P$1") (pinfunction "1_P$1") (pintype "passive"))
      (node (ref "JP98") (pin "1") (pinfunction "1_1") (pintype "passive"))
    )
    (net (code "191") (name "/130_1440392763") (class "Default")
      (node (ref "JP108") (pin "1") (pinfunction "1_1") (pintype "passive"))
      (node (ref "JP1401") (pin "P$1") (pinfunction "1_P$1") (pintype "passive"))
    )
    (net (code "192") (name "/131_1440392763") (class "Default")
      (node (ref "JP118") (pin "1") (pinfunction "1_1") (pintype "passive"))
      (node (ref "JP1403") (pin "P$1") (pinfunction "1_P$1") (pintype "passive"))
    )
    (net (code "193") (name "/132_1440392763") (class "Default")
      (node (ref "JP128") (pin "1") (pinfunction "1_1") (pintype "passive"))
      (node (ref "JP1405") (pin "P$1") (pinfunction "1_P$1") (pintype "passive"))
    )
    (net (code "194") (name "/133_1440392763") (class "Default")
      (node (ref "JP138") (pin "1") (pinfunction "1_1") (pintype "passive"))
      (node (ref "JP1407") (pin "P$1") (pinfunction "1_P$1") (pintype "passive"))
    )
    (net (code "195") (name "/134_1440392763") (class "Default")
      (node (ref "JP1409") (pin "P$1") (pinfunction "1_P$1") (pintype "passive"))
      (node (ref "JP148") (pin "1") (pinfunction "1_1") (pintype "passive"))
    )
    (net (code "196") (name "/135_1440392763") (class "Default")
      (node (ref "JP1411") (pin "P$1") (pinfunction "1_P$1") (pintype "passive"))
      (node (ref "JP158") (pin "1") (pinfunction "1_1") (pintype "passive"))
    )
    (net (code "197") (name "/136_1440392763") (class "Default")
      (node (ref "JP1413") (pin "P$1") (pinfunction "1_P$1") (pintype "passive"))
      (node (ref "JP168") (pin "1") (pinfunction "1_1") (pintype "passive"))
    )
    (net (code "198") (name "/137_1440392763") (class "Default")
      (node (ref "JP1415") (pin "P$1") (pinfunction "1_P$1") (pintype "passive"))
      (node (ref "JP178") (pin "1") (pinfunction "1_1") (pintype "passive"))
    )
    (net (code "199") (name "/138_1440392763") (class "Default")
      (node (ref "JP1417") (pin "P$1") (pinfunction "1_P$1") (pintype "passive"))
      (node (ref "JP188") (pin "1") (pinfunction "1_1") (pintype "passive"))
    )
    (net (code "200") (name "/139_1440392763") (class "Default")
      (node (ref "JP1419") (pin "P$1") (pinfunction "1_P$1") (pintype "passive"))
      (node (ref "JP198") (pin "1") (pinfunction "1_1") (pintype "passive"))
    )
    (net (code "201") (name "/140_1440392763") (class "Default")
      (node (ref "JP1421") (pin "P$1") (pinfunction "1_P$1") (pintype "passive"))
      (node (ref "JP208") (pin "1") (pinfunction "1_1") (pintype "passive"))
    )
    (net (code "202") (name "/141_1440392763") (class "Default")
      (node (ref "JP1423") (pin "P$1") (pinfunction "1_P$1") (pintype "passive"))
      (node (ref "JP218") (pin "1") (pinfunction "1_1") (pintype "passive"))
    )
    (net (code "203") (name "/142_1440392763") (class "Default")
      (node (ref "JP1425") (pin "P$1") (pinfunction "1_P$1") (pintype "passive"))
      (node (ref "JP228") (pin "1") (pinfunction "1_1") (pintype "passive"))
    )
    (net (code "204") (name "/143_1440392763") (class "Default")
      (node (ref "JP1427") (pin "P$1") (pinfunction "1_P$1") (pintype "passive"))
      (node (ref "JP238") (pin "1") (pinfunction "1_1") (pintype "passive"))
    )
    (net (code "205") (name "/144_1440392763") (class "Default")
      (node (ref "JP1429") (pin "P$1") (pinfunction "1_P$1") (pintype "passive"))
      (node (ref "JP248") (pin "1") (pinfunction "1_1") (pintype "passive"))
    )
    (net (code "206") (name "/145_1440392763") (class "Default")
      (node (ref "JP1431") (pin "P$1") (pinfunction "1_P$1") (pintype "passive"))
      (node (ref "JP258") (pin "1") (pinfunction "1_1") (pintype "passive"))
    )
    (net (code "207") (name "/146_1440392763") (class "Default")
      (node (ref "JP1433") (pin "P$1") (pinfunction "1_P$1") (pintype "passive"))
      (node (ref "JP268") (pin "1") (pinfunction "1_1") (pintype "passive"))
    )
    (net (code "208") (name "/147_1440392763") (class "Default")
      (node (ref "JP1435") (pin "P$1") (pinfunction "1_P$1") (pintype "passive"))
      (node (ref "JP278") (pin "1") (pinfunction "1_1") (pintype "passive"))
    )
    (net (code "209") (name "/148_1440392763") (class "Default")
      (node (ref "JP1437") (pin "P$1") (pinfunction "1_P$1") (pintype "passive"))
      (node (ref "JP288") (pin "1") (pinfunction "1_1") (pintype "passive"))
    )
    (net (code "210") (name "/149_1440392763") (class "Default")
      (node (ref "JP1439") (pin "P$1") (pinfunction "1_P$1") (pintype "passive"))
      (node (ref "JP298") (pin "1") (pinfunction "1_1") (pintype "passive"))
    )
    (net (code "211") (name "/150_1440392763") (class "Default")
      (node (ref "JP1440") (pin "P$1") (pinfunction "1_P$1") (pintype "passive"))
      (node (ref "JP297") (pin "1") (pinfunction "1_1") (pintype "passive"))
    )
    (net (code "212") (name "/151_1440392763") (class "Default")
      (node (ref "JP1201") (pin "P$1") (pinfunction "1_P$1") (pintype "passive"))
      (node (ref "JP3") (pin "1") (pinfunction "1_1") (pintype "passive"))
    )
    (net (code "213") (name "/152_1440392763") (class "Default")
      (node (ref "JP1203") (pin "P$1") (pinfunction "1_P$1") (pintype "passive"))
      (node (ref "JP13") (pin "1") (pinfunction "1_1") (pintype "passive"))
    )
    (net (code "214") (name "/153_1440392763") (class "Default")
      (node (ref "JP1205") (pin "P$1") (pinfunction "1_P$1") (pintype "passive"))
      (node (ref "JP23") (pin "1") (pinfunction "1_1") (pintype "passive"))
    )
    (net (code "215") (name "/154_1440392763") (class "Default")
      (node (ref "JP1207") (pin "P$1") (pinfunction "1_P$1") (pintype "passive"))
      (node (ref "JP33") (pin "1") (pinfunction "1_1") (pintype "passive"))
    )
    (net (code "216") (name "/155_1440392763") (class "Default")
      (node (ref "JP1209") (pin "P$1") (pinfunction "1_P$1") (pintype "passive"))
      (node (ref "JP43") (pin "1") (pinfunction "1_1") (pintype "passive"))
    )
    (net (code "217") (name "/156_1440392763") (class "Default")
      (node (ref "JP1211") (pin "P$1") (pinfunction "1_P$1") (pintype "passive"))
      (node (ref "JP53") (pin "1") (pinfunction "1_1") (pintype "passive"))
    )
    (net (code "218") (name "/157_1440392763") (class "Default")
      (node (ref "JP1213") (pin "P$1") (pinfunction "1_P$1") (pintype "passive"))
      (node (ref "JP63") (pin "1") (pinfunction "1_1") (pintype "passive"))
    )
    (net (code "219") (name "/158_1440392763") (class "Default")
      (node (ref "JP1215") (pin "P$1") (pinfunction "1_P$1") (pintype "passive"))
      (node (ref "JP73") (pin "1") (pinfunction "1_1") (pintype "passive"))
    )
    (net (code "220") (name "/159_1440392763") (class "Default")
      (node (ref "JP1217") (pin "P$1") (pinfunction "1_P$1") (pintype "passive"))
      (node (ref "JP83") (pin "1") (pinfunction "1_1") (pintype "passive"))
    )
    (net (code "221") (name "/160_1440392763") (class "Default")
      (node (ref "JP1219") (pin "P$1") (pinfunction "1_P$1") (pintype "passive"))
      (node (ref "JP93") (pin "1") (pinfunction "1_1") (pintype "passive"))
    )
    (net (code "222") (name "/161_1440392763") (class "Default")
      (node (ref "JP103") (pin "1") (pinfunction "1_1") (pintype "passive"))
      (node (ref "JP1221") (pin "P$1") (pinfunction "1_P$1") (pintype "passive"))
    )
    (net (code "223") (name "/162_1440392763") (class "Default")
      (node (ref "JP113") (pin "1") (pinfunction "1_1") (pintype "passive"))
      (node (ref "JP1223") (pin "P$1") (pinfunction "1_P$1") (pintype "passive"))
    )
    (net (code "224") (name "/163_1440392763") (class "Default")
      (node (ref "JP1225") (pin "P$1") (pinfunction "1_P$1") (pintype "passive"))
      (node (ref "JP123") (pin "1") (pinfunction "1_1") (pintype "passive"))
    )
    (net (code "225") (name "/164_1440392763") (class "Default")
      (node (ref "JP1227") (pin "P$1") (pinfunction "1_P$1") (pintype "passive"))
      (node (ref "JP133") (pin "1") (pinfunction "1_1") (pintype "passive"))
    )
    (net (code "226") (name "/165_1440392763") (class "Default")
      (node (ref "JP1229") (pin "P$1") (pinfunction "1_P$1") (pintype "passive"))
      (node (ref "JP143") (pin "1") (pinfunction "1_1") (pintype "passive"))
    )
    (net (code "227") (name "/166_1440392763") (class "Default")
      (node (ref "JP1231") (pin "P$1") (pinfunction "1_P$1") (pintype "passive"))
      (node (ref "JP153") (pin "1") (pinfunction "1_1") (pintype "passive"))
    )
    (net (code "228") (name "/167_1440392763") (class "Default")
      (node (ref "JP1233") (pin "P$1") (pinfunction "1_P$1") (pintype "passive"))
      (node (ref "JP163") (pin "1") (pinfunction "1_1") (pintype "passive"))
    )
    (net (code "229") (name "/168_1440392763") (class "Default")
      (node (ref "JP1235") (pin "P$1") (pinfunction "1_P$1") (pintype "passive"))
      (node (ref "JP173") (pin "1") (pinfunction "1_1") (pintype "passive"))
    )
    (net (code "230") (name "/169_1440392763") (class "Default")
      (node (ref "JP1237") (pin "P$1") (pinfunction "1_P$1") (pintype "passive"))
      (node (ref "JP183") (pin "1") (pinfunction "1_1") (pintype "passive"))
    )
    (net (code "231") (name "/170_1440392763") (class "Default")
      (node (ref "JP1239") (pin "P$1") (pinfunction "1_P$1") (pintype "passive"))
      (node (ref "JP193") (pin "1") (pinfunction "1_1") (pintype "passive"))
    )
    (net (code "232") (name "/171_1440392763") (class "Default")
      (node (ref "JP1241") (pin "P$1") (pinfunction "1_P$1") (pintype "passive"))
      (node (ref "JP203") (pin "1") (pinfunction "1_1") (pintype "passive"))
    )
    (net (code "233") (name "/172_1440392763") (class "Default")
      (node (ref "JP1243") (pin "P$1") (pinfunction "1_P$1") (pintype "passive"))
      (node (ref "JP213") (pin "1") (pinfunction "1_1") (pintype "passive"))
    )
    (net (code "234") (name "/173_1440392763") (class "Default")
      (node (ref "JP1245") (pin "P$1") (pinfunction "1_P$1") (pintype "passive"))
      (node (ref "JP223") (pin "1") (pinfunction "1_1") (pintype "passive"))
    )
    (net (code "235") (name "/174_1440392763") (class "Default")
      (node (ref "JP1247") (pin "P$1") (pinfunction "1_P$1") (pintype "passive"))
      (node (ref "JP233") (pin "1") (pinfunction "1_1") (pintype "passive"))
    )
    (net (code "236") (name "/175_1440392763") (class "Default")
      (node (ref "JP1249") (pin "P$1") (pinfunction "1_P$1") (pintype "passive"))
      (node (ref "JP243") (pin "1") (pinfunction "1_1") (pintype "passive"))
    )
    (net (code "237") (name "/176_1440392763") (class "Default")
      (node (ref "JP1251") (pin "P$1") (pinfunction "1_P$1") (pintype "passive"))
      (node (ref "JP253") (pin "1") (pinfunction "1_1") (pintype "passive"))
    )
    (net (code "238") (name "/177_1440392763") (class "Default")
      (node (ref "JP1253") (pin "P$1") (pinfunction "1_P$1") (pintype "passive"))
      (node (ref "JP263") (pin "1") (pinfunction "1_1") (pintype "passive"))
    )
    (net (code "239") (name "/178_1440392763") (class "Default")
      (node (ref "JP1255") (pin "P$1") (pinfunction "1_P$1") (pintype "passive"))
      (node (ref "JP273") (pin "1") (pinfunction "1_1") (pintype "passive"))
    )
    (net (code "240") (name "/179_1440392763") (class "Default")
      (node (ref "JP1257") (pin "P$1") (pinfunction "1_P$1") (pintype "passive"))
      (node (ref "JP283") (pin "1") (pinfunction "1_1") (pintype "passive"))
    )
    (net (code "241") (name "/180_1440392763") (class "Default")
      (node (ref "JP1259") (pin "P$1") (pinfunction "1_P$1") (pintype "passive"))
      (node (ref "JP293") (pin "1") (pinfunction "1_1") (pintype "passive"))
    )
    (net (code "242") (name "/181_1440392763") (class "Default")
      (node (ref "JP1260") (pin "P$1") (pinfunction "1_P$1") (pintype "passive"))
      (node (ref "JP294") (pin "1") (pinfunction "1_1") (pintype "passive"))
    )
    (net (code "243") (name "/182_1440392763") (class "Default")
      (node (ref "JP1382") (pin "P$1") (pinfunction "1_P$1") (pintype "passive"))
      (node (ref "JP7") (pin "1") (pinfunction "1_1") (pintype "passive"))
    )
    (net (code "244") (name "/183_1440392763") (class "Default")
      (node (ref "JP1384") (pin "P$1") (pinfunction "1_P$1") (pintype "passive"))
      (node (ref "JP17") (pin "1") (pinfunction "1_1") (pintype "passive"))
    )
    (net (code "245") (name "/184_1440392763") (class "Default")
      (node (ref "JP1386") (pin "P$1") (pinfunction "1_P$1") (pintype "passive"))
      (node (ref "JP27") (pin "1") (pinfunction "1_1") (pintype "passive"))
    )
    (net (code "246") (name "/185_1440392763") (class "Default")
      (node (ref "JP1388") (pin "P$1") (pinfunction "1_P$1") (pintype "passive"))
      (node (ref "JP37") (pin "1") (pinfunction "1_1") (pintype "passive"))
    )
    (net (code "247") (name "/186_1440392763") (class "Default")
      (node (ref "JP1390") (pin "P$1") (pinfunction "1_P$1") (pintype "passive"))
      (node (ref "JP47") (pin "1") (pinfunction "1_1") (pintype "passive"))
    )
    (net (code "248") (name "/187_1440392763") (class "Default")
      (node (ref "JP1392") (pin "P$1") (pinfunction "1_P$1") (pintype "passive"))
      (node (ref "JP57") (pin "1") (pinfunction "1_1") (pintype "passive"))
    )
    (net (code "249") (name "/188_1440392763") (class "Default")
      (node (ref "JP1394") (pin "P$1") (pinfunction "1_P$1") (pintype "passive"))
      (node (ref "JP67") (pin "1") (pinfunction "1_1") (pintype "passive"))
    )
    (net (code "250") (name "/189_1440392763") (class "Default")
      (node (ref "JP1396") (pin "P$1") (pinfunction "1_P$1") (pintype "passive"))
      (node (ref "JP77") (pin "1") (pinfunction "1_1") (pintype "passive"))
    )
    (net (code "251") (name "/190_1440392763") (class "Default")
      (node (ref "JP1398") (pin "P$1") (pinfunction "1_P$1") (pintype "passive"))
      (node (ref "JP87") (pin "1") (pinfunction "1_1") (pintype "passive"))
    )
    (net (code "252") (name "/191_1440392763") (class "Default")
      (node (ref "JP1400") (pin "P$1") (pinfunction "1_P$1") (pintype "passive"))
      (node (ref "JP97") (pin "1") (pinfunction "1_1") (pintype "passive"))
    )
    (net (code "253") (name "/192_1440392763") (class "Default")
      (node (ref "JP107") (pin "1") (pinfunction "1_1") (pintype "passive"))
      (node (ref "JP1402") (pin "P$1") (pinfunction "1_P$1") (pintype "passive"))
    )
    (net (code "254") (name "/193_1440392763") (class "Default")
      (node (ref "JP117") (pin "1") (pinfunction "1_1") (pintype "passive"))
      (node (ref "JP1404") (pin "P$1") (pinfunction "1_P$1") (pintype "passive"))
    )
    (net (code "255") (name "/194_1440392763") (class "Default")
      (node (ref "JP127") (pin "1") (pinfunction "1_1") (pintype "passive"))
      (node (ref "JP1406") (pin "P$1") (pinfunction "1_P$1") (pintype "passive"))
    )
    (net (code "256") (name "/195_1440392763") (class "Default")
      (node (ref "JP137") (pin "1") (pinfunction "1_1") (pintype "passive"))
      (node (ref "JP1408") (pin "P$1") (pinfunction "1_P$1") (pintype "passive"))
    )
    (net (code "257") (name "/196_1440392763") (class "Default")
      (node (ref "JP1410") (pin "P$1") (pinfunction "1_P$1") (pintype "passive"))
      (node (ref "JP147") (pin "1") (pinfunction "1_1") (pintype "passive"))
    )
    (net (code "258") (name "/197_1440392763") (class "Default")
      (node (ref "JP1412") (pin "P$1") (pinfunction "1_P$1") (pintype "passive"))
      (node (ref "JP157") (pin "1") (pinfunction "1_1") (pintype "passive"))
    )
    (net (code "259") (name "/198_1440392763") (class "Default")
      (node (ref "JP1414") (pin "P$1") (pinfunction "1_P$1") (pintype "passive"))
      (node (ref "JP167") (pin "1") (pinfunction "1_1") (pintype "passive"))
    )
    (net (code "260") (name "/199_1440392763") (class "Default")
      (node (ref "JP1416") (pin "P$1") (pinfunction "1_P$1") (pintype "passive"))
      (node (ref "JP177") (pin "1") (pinfunction "1_1") (pintype "passive"))
    )
    (net (code "261") (name "/200_1440392763") (class "Default")
      (node (ref "JP1418") (pin "P$1") (pinfunction "1_P$1") (pintype "passive"))
      (node (ref "JP187") (pin "1") (pinfunction "1_1") (pintype "passive"))
    )
    (net (code "262") (name "/201_1440392763") (class "Default")
      (node (ref "JP1420") (pin "P$1") (pinfunction "1_P$1") (pintype "passive"))
      (node (ref "JP197") (pin "1") (pinfunction "1_1") (pintype "passive"))
    )
    (net (code "263") (name "/202_1440392763") (class "Default")
      (node (ref "JP1422") (pin "P$1") (pinfunction "1_P$1") (pintype "passive"))
      (node (ref "JP207") (pin "1") (pinfunction "1_1") (pintype "passive"))
    )
    (net (code "264") (name "/203_1440392763") (class "Default")
      (node (ref "JP1424") (pin "P$1") (pinfunction "1_P$1") (pintype "passive"))
      (node (ref "JP217") (pin "1") (pinfunction "1_1") (pintype "passive"))
    )
    (net (code "265") (name "/204_1440392763") (class "Default")
      (node (ref "JP1426") (pin "P$1") (pinfunction "1_P$1") (pintype "passive"))
      (node (ref "JP227") (pin "1") (pinfunction "1_1") (pintype "passive"))
    )
    (net (code "266") (name "/205_1440392763") (class "Default")
      (node (ref "JP1428") (pin "P$1") (pinfunction "1_P$1") (pintype "passive"))
      (node (ref "JP237") (pin "1") (pinfunction "1_1") (pintype "passive"))
    )
    (net (code "267") (name "/206_1440392763") (class "Default")
      (node (ref "JP1430") (pin "P$1") (pinfunction "1_P$1") (pintype "passive"))
      (node (ref "JP247") (pin "1") (pinfunction "1_1") (pintype "passive"))
    )
    (net (code "268") (name "/207_1440392763") (class "Default")
      (node (ref "JP1432") (pin "P$1") (pinfunction "1_P$1") (pintype "passive"))
      (node (ref "JP257") (pin "1") (pinfunction "1_1") (pintype "passive"))
    )
    (net (code "269") (name "/208_1440392763") (class "Default")
      (node (ref "JP1434") (pin "P$1") (pinfunction "1_P$1") (pintype "passive"))
      (node (ref "JP267") (pin "1") (pinfunction "1_1") (pintype "passive"))
    )
    (net (code "270") (name "/209_1440392763") (class "Default")
      (node (ref "JP1436") (pin "P$1") (pinfunction "1_P$1") (pintype "passive"))
      (node (ref "JP277") (pin "1") (pinfunction "1_1") (pintype "passive"))
    )
    (net (code "271") (name "/210_1440392763") (class "Default")
      (node (ref "JP1438") (pin "P$1") (pinfunction "1_P$1") (pintype "passive"))
      (node (ref "JP287") (pin "1") (pinfunction "1_1") (pintype "passive"))
    )
    (net (code "272") (name "/211_1440392763") (class "Default")
      (node (ref "JP1202") (pin "P$1") (pinfunction "1_P$1") (pintype "passive"))
      (node (ref "JP4") (pin "1") (pinfunction "1_1") (pintype "passive"))
    )
    (net (code "273") (name "/212_1440392763") (class "Default")
      (node (ref "JP1204") (pin "P$1") (pinfunction "1_P$1") (pintype "passive"))
      (node (ref "JP14") (pin "1") (pinfunction "1_1") (pintype "passive"))
    )
    (net (code "274") (name "/213_1440392763") (class "Default")
      (node (ref "JP1206") (pin "P$1") (pinfunction "1_P$1") (pintype "passive"))
      (node (ref "JP24") (pin "1") (pinfunction "1_1") (pintype "passive"))
    )
    (net (code "275") (name "/214_1440392763") (class "Default")
      (node (ref "JP1208") (pin "P$1") (pinfunction "1_P$1") (pintype "passive"))
      (node (ref "JP34") (pin "1") (pinfunction "1_1") (pintype "passive"))
    )
    (net (code "276") (name "/215_1440392763") (class "Default")
      (node (ref "JP1210") (pin "P$1") (pinfunction "1_P$1") (pintype "passive"))
      (node (ref "JP44") (pin "1") (pinfunction "1_1") (pintype "passive"))
    )
    (net (code "277") (name "/216_1440392763") (class "Default")
      (node (ref "JP1212") (pin "P$1") (pinfunction "1_P$1") (pintype "passive"))
      (node (ref "JP54") (pin "1") (pinfunction "1_1") (pintype "passive"))
    )
    (net (code "278") (name "/217_1440392763") (class "Default")
      (node (ref "JP1214") (pin "P$1") (pinfunction "1_P$1") (pintype "passive"))
      (node (ref "JP64") (pin "1") (pinfunction "1_1") (pintype "passive"))
    )
    (net (code "279") (name "/218_1440392763") (class "Default")
      (node (ref "JP1216") (pin "P$1") (pinfunction "1_P$1") (pintype "passive"))
      (node (ref "JP74") (pin "1") (pinfunction "1_1") (pintype "passive"))
    )
    (net (code "280") (name "/219_1440392763") (class "Default")
      (node (ref "JP1218") (pin "P$1") (pinfunction "1_P$1") (pintype "passive"))
      (node (ref "JP84") (pin "1") (pinfunction "1_1") (pintype "passive"))
    )
    (net (code "281") (name "/220_1440392763") (class "Default")
      (node (ref "JP1220") (pin "P$1") (pinfunction "1_P$1") (pintype "passive"))
      (node (ref "JP94") (pin "1") (pinfunction "1_1") (pintype "passive"))
    )
    (net (code "282") (name "/221_1440392763") (class "Default")
      (node (ref "JP104") (pin "1") (pinfunction "1_1") (pintype "passive"))
      (node (ref "JP1222") (pin "P$1") (pinfunction "1_P$1") (pintype "passive"))
    )
    (net (code "283") (name "/222_1440392763") (class "Default")
      (node (ref "JP114") (pin "1") (pinfunction "1_1") (pintype "passive"))
      (node (ref "JP1224") (pin "P$1") (pinfunction "1_P$1") (pintype "passive"))
    )
    (net (code "284") (name "/223_1440392763") (class "Default")
      (node (ref "JP1226") (pin "P$1") (pinfunction "1_P$1") (pintype "passive"))
      (node (ref "JP124") (pin "1") (pinfunction "1_1") (pintype "passive"))
    )
    (net (code "285") (name "/224_1440392763") (class "Default")
      (node (ref "JP1228") (pin "P$1") (pinfunction "1_P$1") (pintype "passive"))
      (node (ref "JP134") (pin "1") (pinfunction "1_1") (pintype "passive"))
    )
    (net (code "286") (name "/225_1440392763") (class "Default")
      (node (ref "JP1230") (pin "P$1") (pinfunction "1_P$1") (pintype "passive"))
      (node (ref "JP144") (pin "1") (pinfunction "1_1") (pintype "passive"))
    )
    (net (code "287") (name "/226_1440392763") (class "Default")
      (node (ref "JP1232") (pin "P$1") (pinfunction "1_P$1") (pintype "passive"))
      (node (ref "JP154") (pin "1") (pinfunction "1_1") (pintype "passive"))
    )
    (net (code "288") (name "/227_1440392763") (class "Default")
      (node (ref "JP1234") (pin "P$1") (pinfunction "1_P$1") (pintype "passive"))
      (node (ref "JP164") (pin "1") (pinfunction "1_1") (pintype "passive"))
    )
    (net (code "289") (name "/228_1440392763") (class "Default")
      (node (ref "JP1236") (pin "P$1") (pinfunction "1_P$1") (pintype "passive"))
      (node (ref "JP174") (pin "1") (pinfunction "1_1") (pintype "passive"))
    )
    (net (code "290") (name "/229_1440392763") (class "Default")
      (node (ref "JP1238") (pin "P$1") (pinfunction "1_P$1") (pintype "passive"))
      (node (ref "JP184") (pin "1") (pinfunction "1_1") (pintype "passive"))
    )
    (net (code "291") (name "/230_1440392763") (class "Default")
      (node (ref "JP1240") (pin "P$1") (pinfunction "1_P$1") (pintype "passive"))
      (node (ref "JP194") (pin "1") (pinfunction "1_1") (pintype "passive"))
    )
    (net (code "292") (name "/231_1440392763") (class "Default")
      (node (ref "JP1242") (pin "P$1") (pinfunction "1_P$1") (pintype "passive"))
      (node (ref "JP204") (pin "1") (pinfunction "1_1") (pintype "passive"))
    )
    (net (code "293") (name "/232_1440392763") (class "Default")
      (node (ref "JP1244") (pin "P$1") (pinfunction "1_P$1") (pintype "passive"))
      (node (ref "JP214") (pin "1") (pinfunction "1_1") (pintype "passive"))
    )
    (net (code "294") (name "/233_1440392763") (class "Default")
      (node (ref "JP1246") (pin "P$1") (pinfunction "1_P$1") (pintype "passive"))
      (node (ref "JP224") (pin "1") (pinfunction "1_1") (pintype "passive"))
    )
    (net (code "295") (name "/234_1440392763") (class "Default")
      (node (ref "JP1248") (pin "P$1") (pinfunction "1_P$1") (pintype "passive"))
      (node (ref "JP234") (pin "1") (pinfunction "1_1") (pintype "passive"))
    )
    (net (code "296") (name "/235_1440392763") (class "Default")
      (node (ref "JP1250") (pin "P$1") (pinfunction "1_P$1") (pintype "passive"))
      (node (ref "JP244") (pin "1") (pinfunction "1_1") (pintype "passive"))
    )
    (net (code "297") (name "/236_1440392763") (class "Default")
      (node (ref "JP1252") (pin "P$1") (pinfunction "1_P$1") (pintype "passive"))
      (node (ref "JP254") (pin "1") (pinfunction "1_1") (pintype "passive"))
    )
    (net (code "298") (name "/237_1440392763") (class "Default")
      (node (ref "JP1254") (pin "P$1") (pinfunction "1_P$1") (pintype "passive"))
      (node (ref "JP264") (pin "1") (pinfunction "1_1") (pintype "passive"))
    )
    (net (code "299") (name "/238_1440392763") (class "Default")
      (node (ref "JP1256") (pin "P$1") (pinfunction "1_P$1") (pintype "passive"))
      (node (ref "JP274") (pin "1") (pinfunction "1_1") (pintype "passive"))
    )
    (net (code "300") (name "/239_1440392763") (class "Default")
      (node (ref "JP1258") (pin "P$1") (pinfunction "1_P$1") (pintype "passive"))
      (node (ref "JP284") (pin "1") (pinfunction "1_1") (pintype "passive"))
    )
  )
)
